# padaukprog.net
KiCad netlist of a schematic drawn in EAGLE
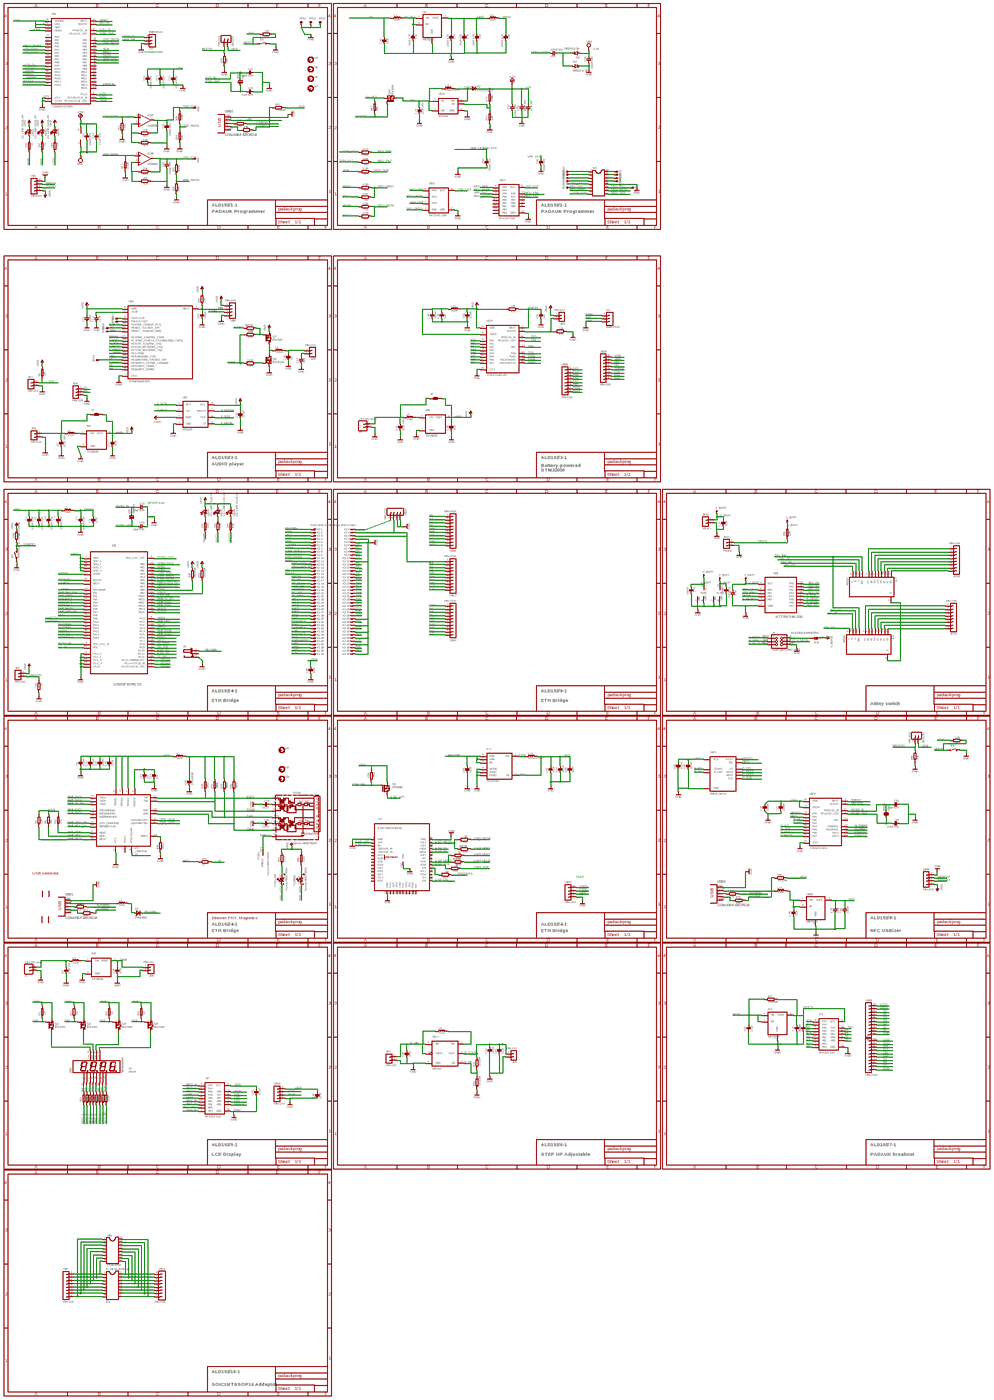
[diagram p0: schematic, sheet 1, overview]
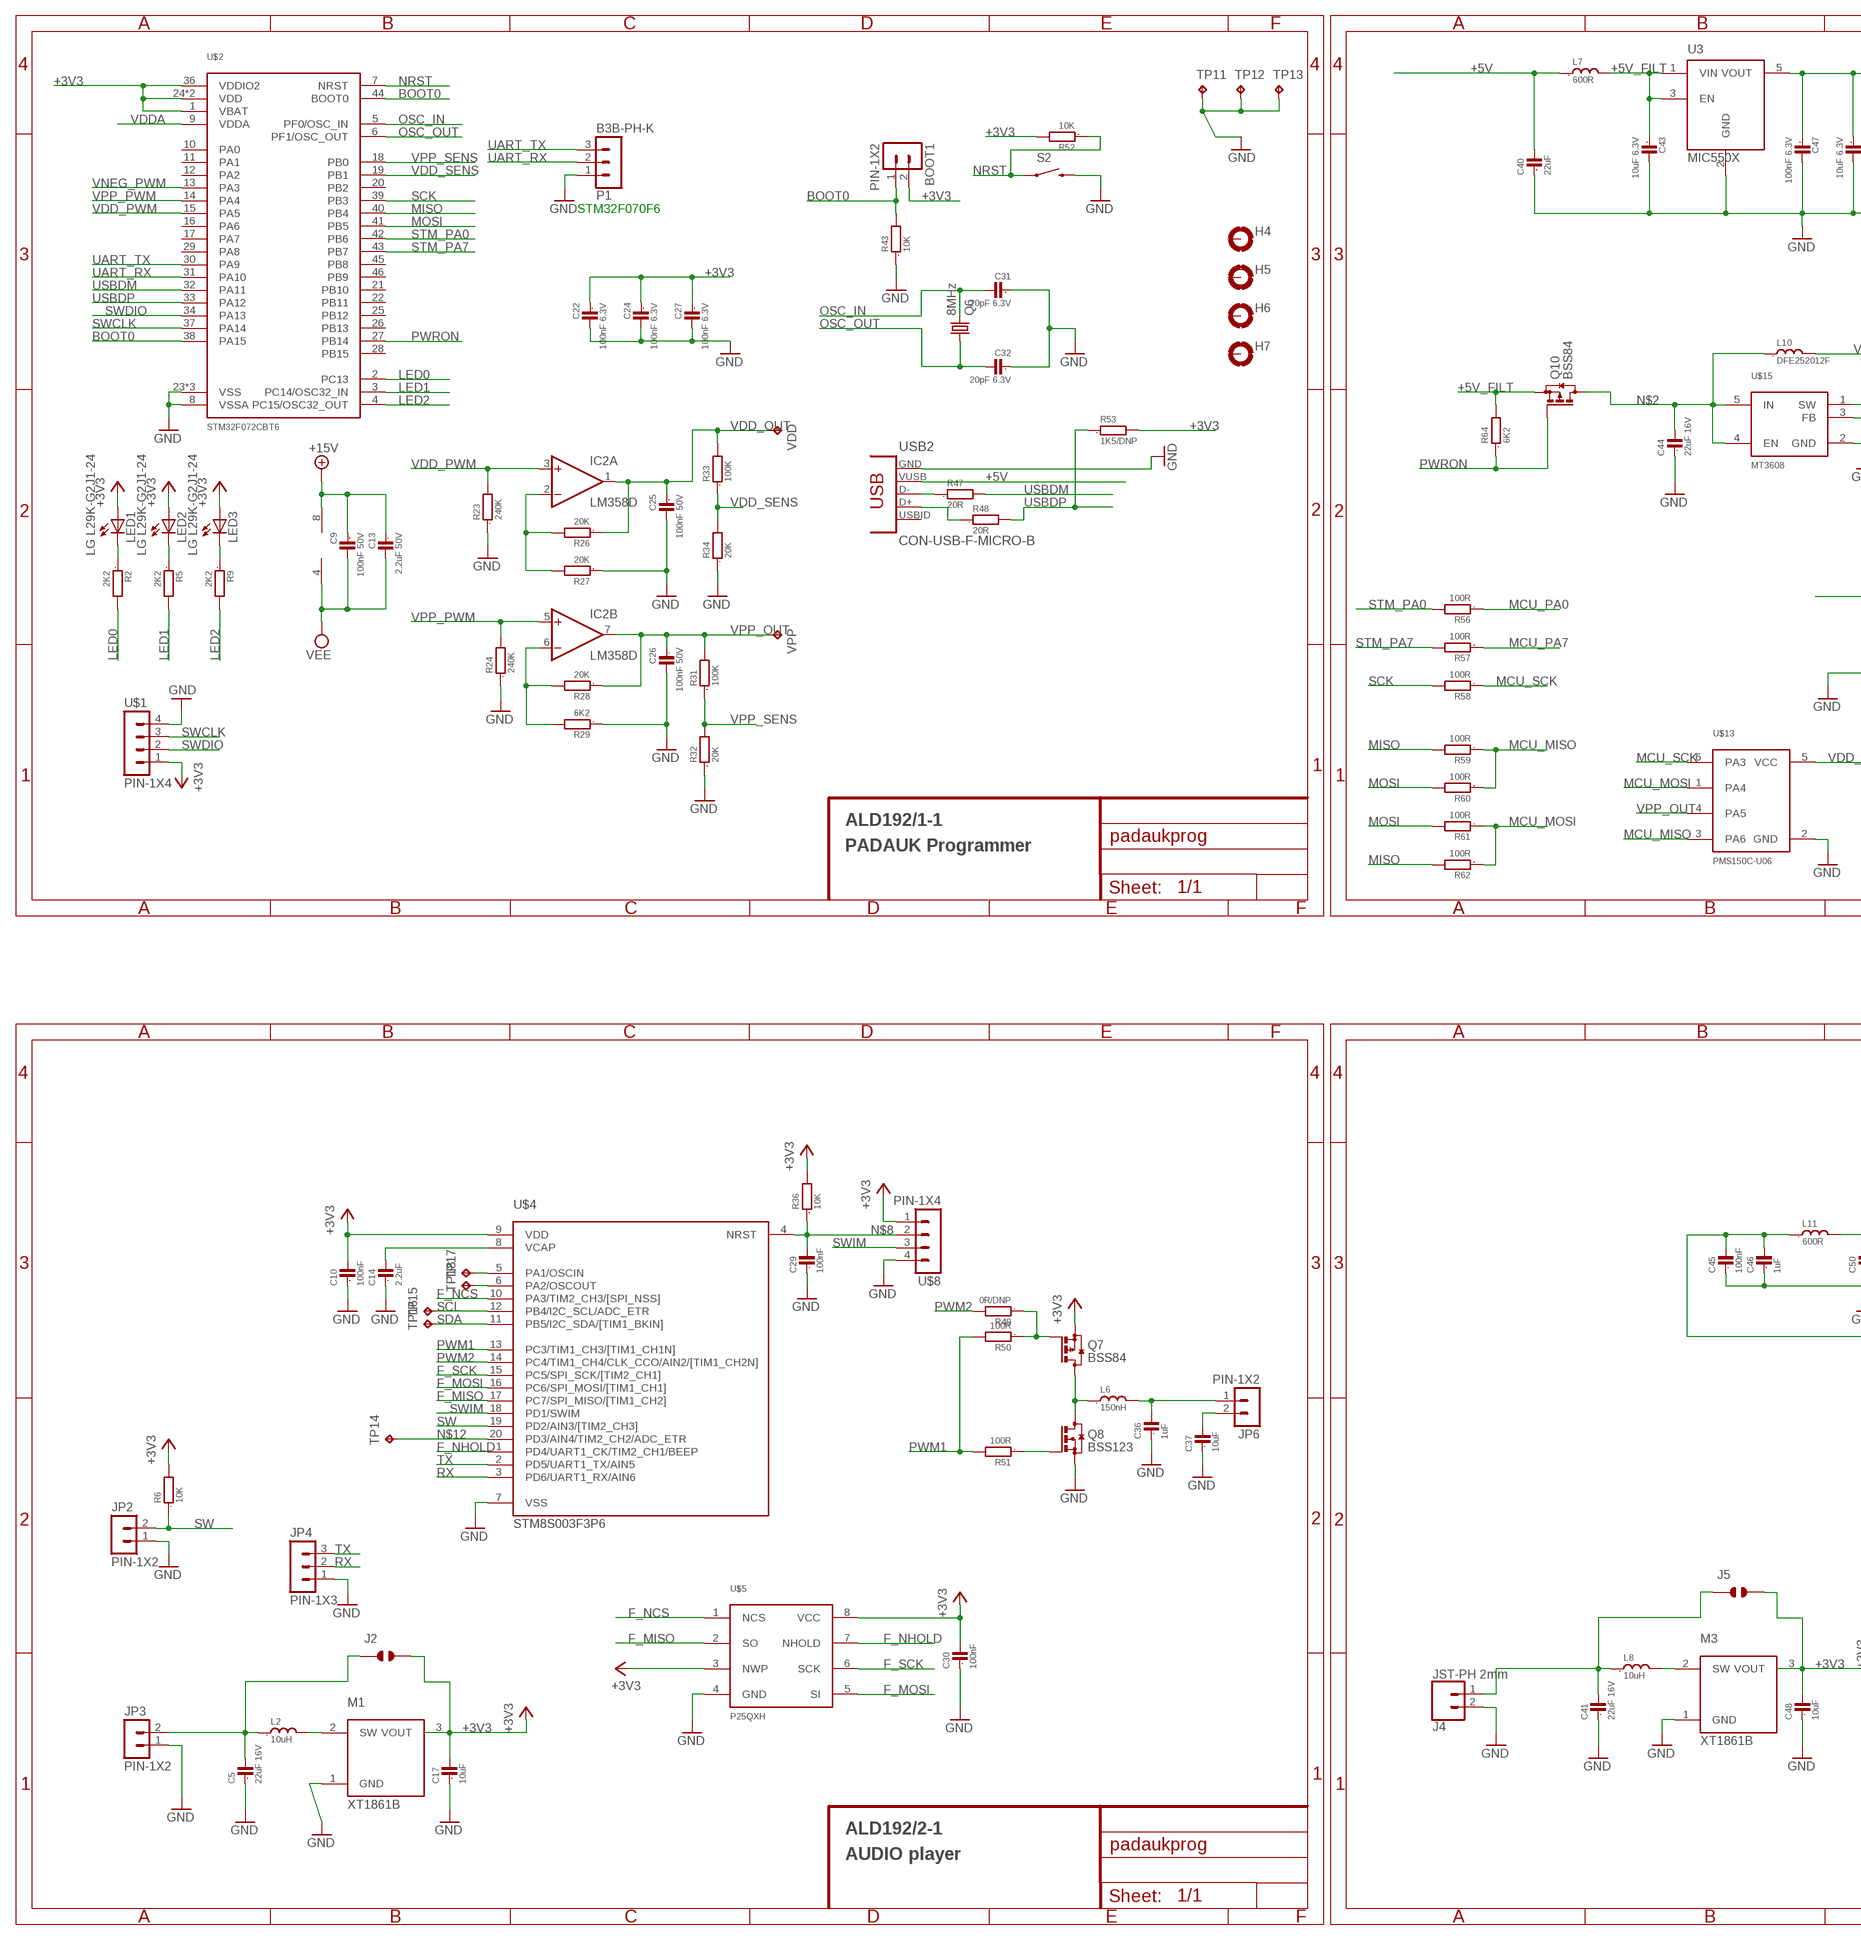
[diagram p1: schematic, sheet 1, part 1 of 7]
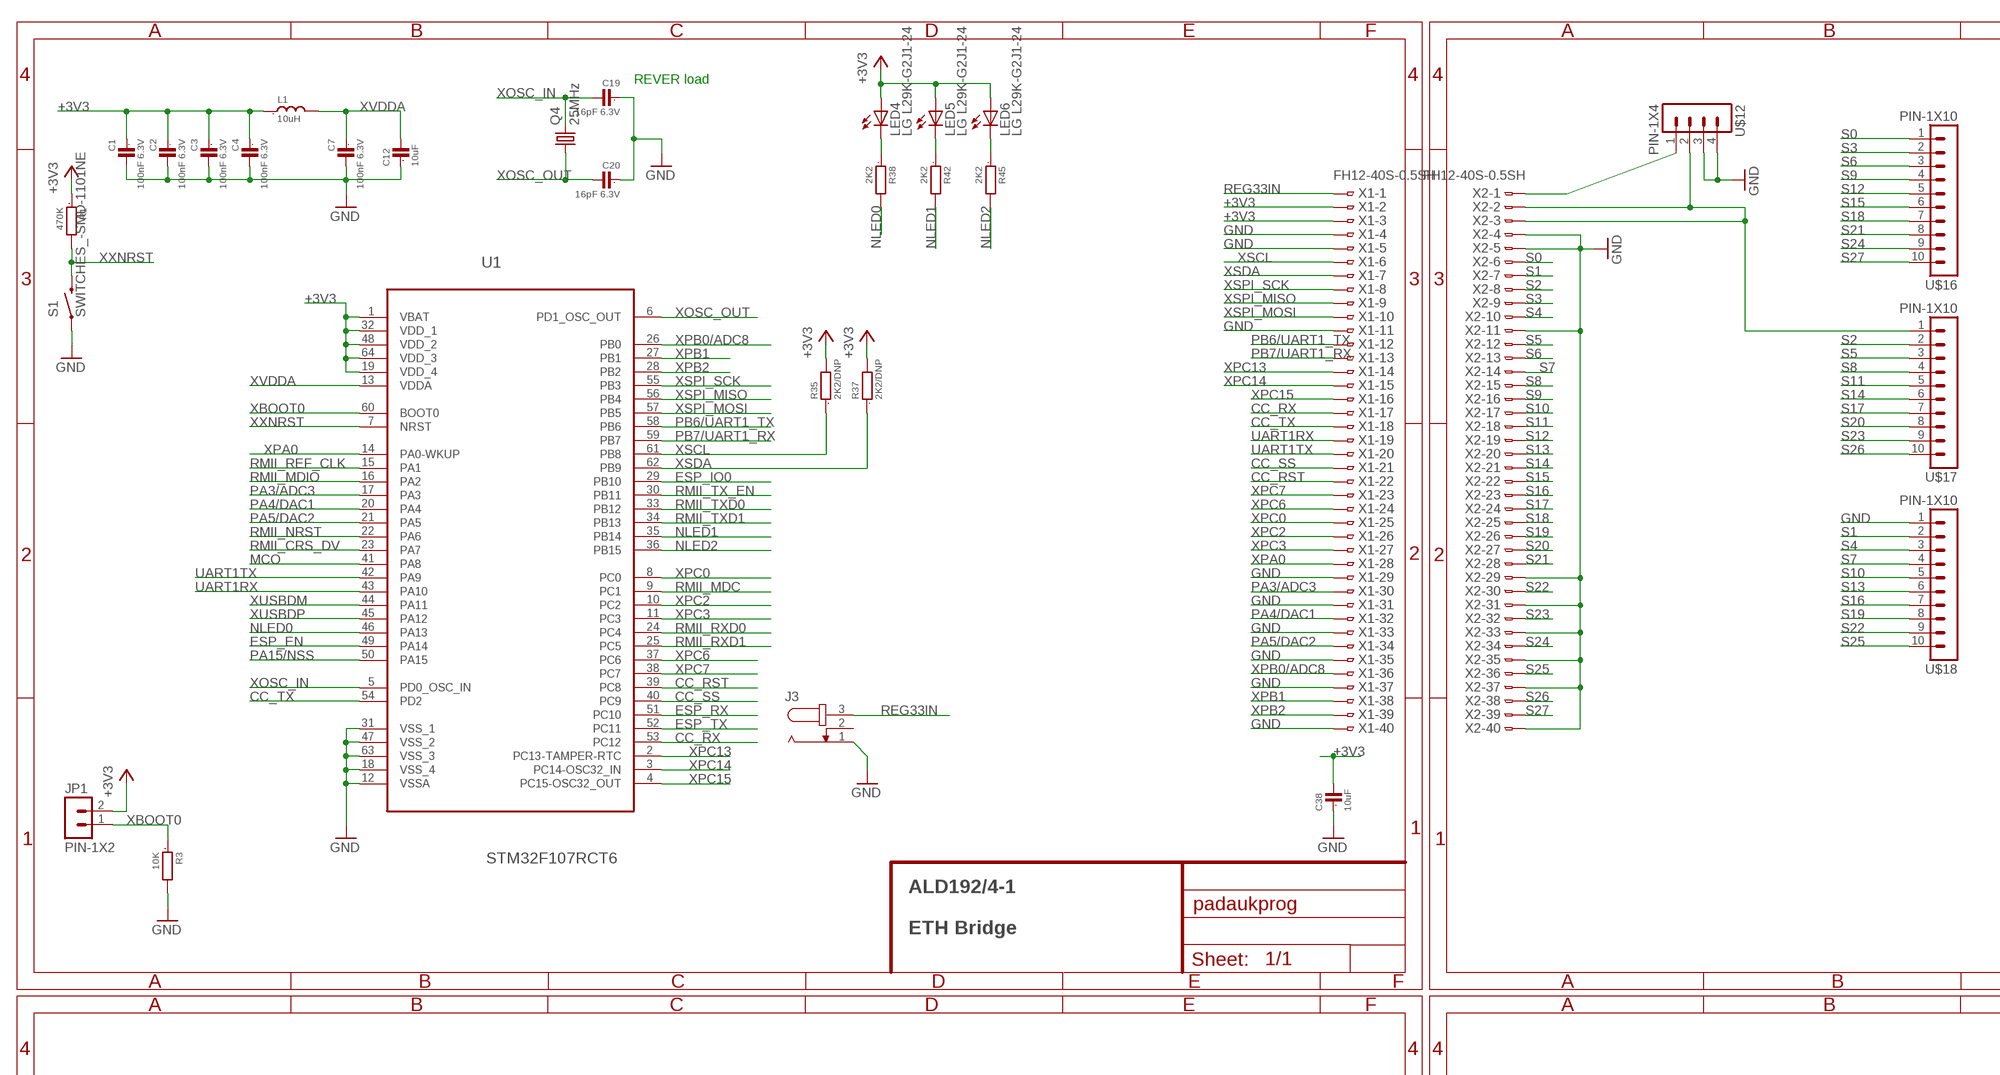
[diagram p2: schematic, sheet 1, part 2 of 7]
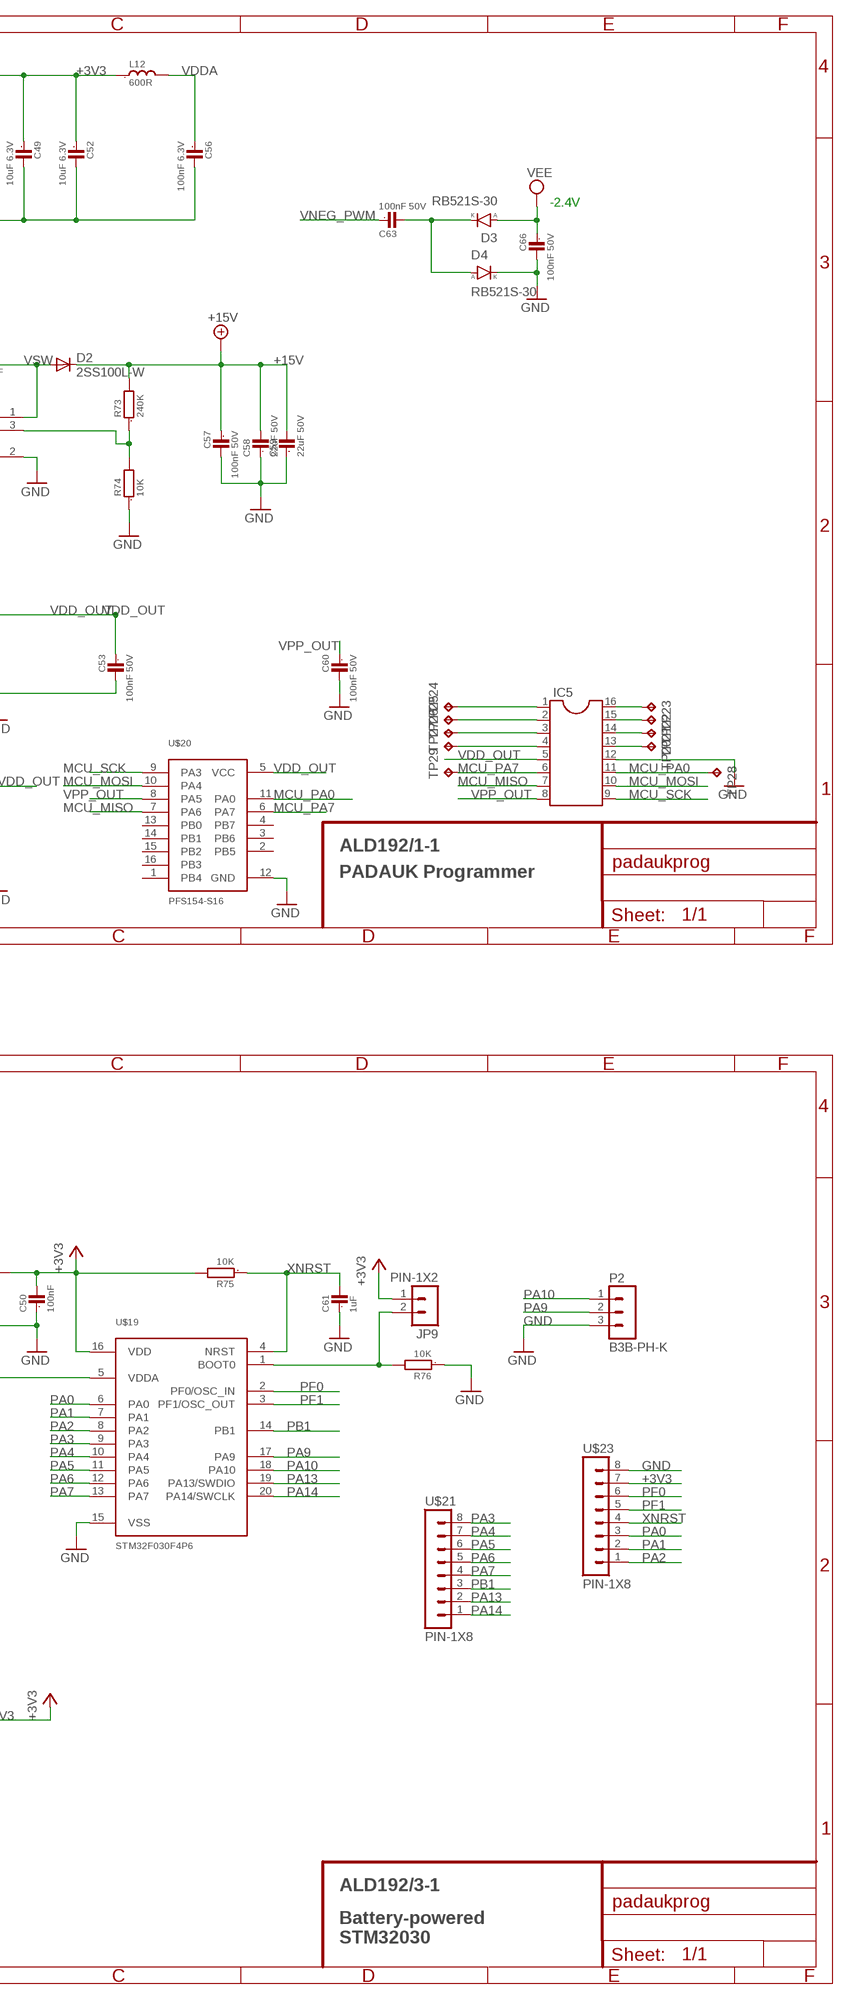
[diagram p3: schematic, sheet 1, part 3 of 7]
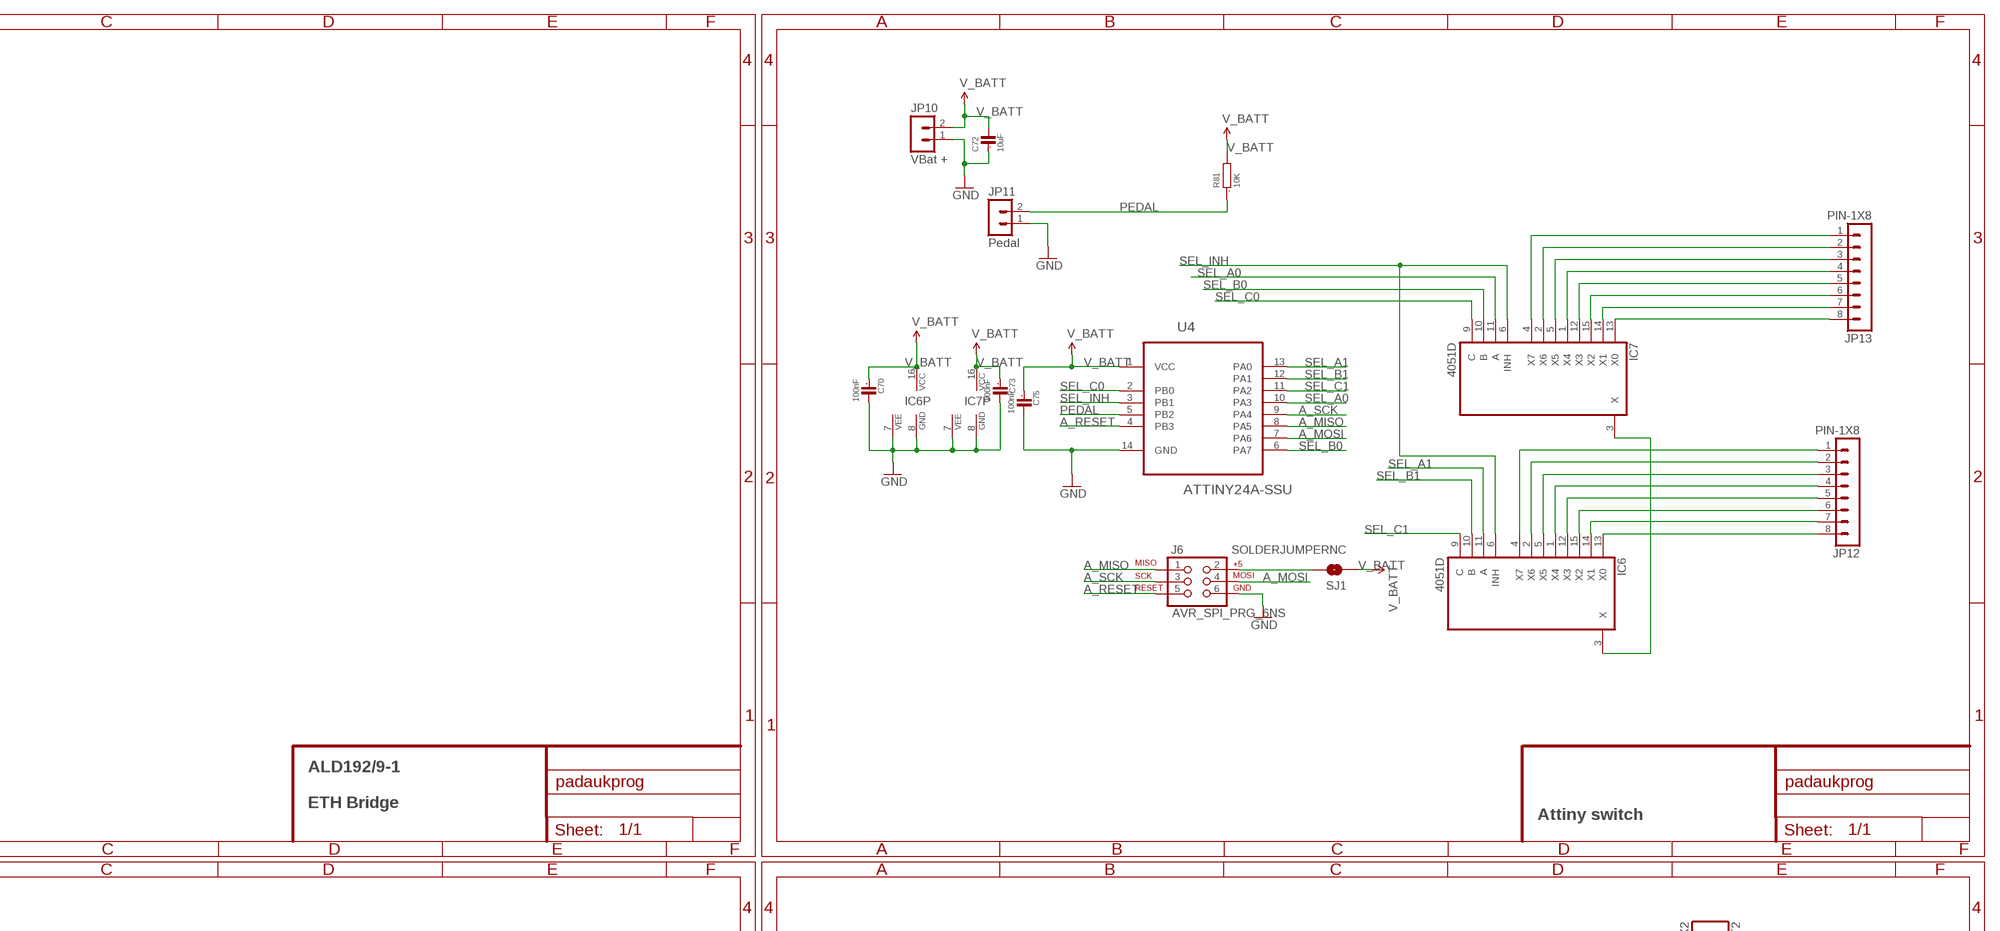
[diagram p4: schematic, sheet 1, part 4 of 7]
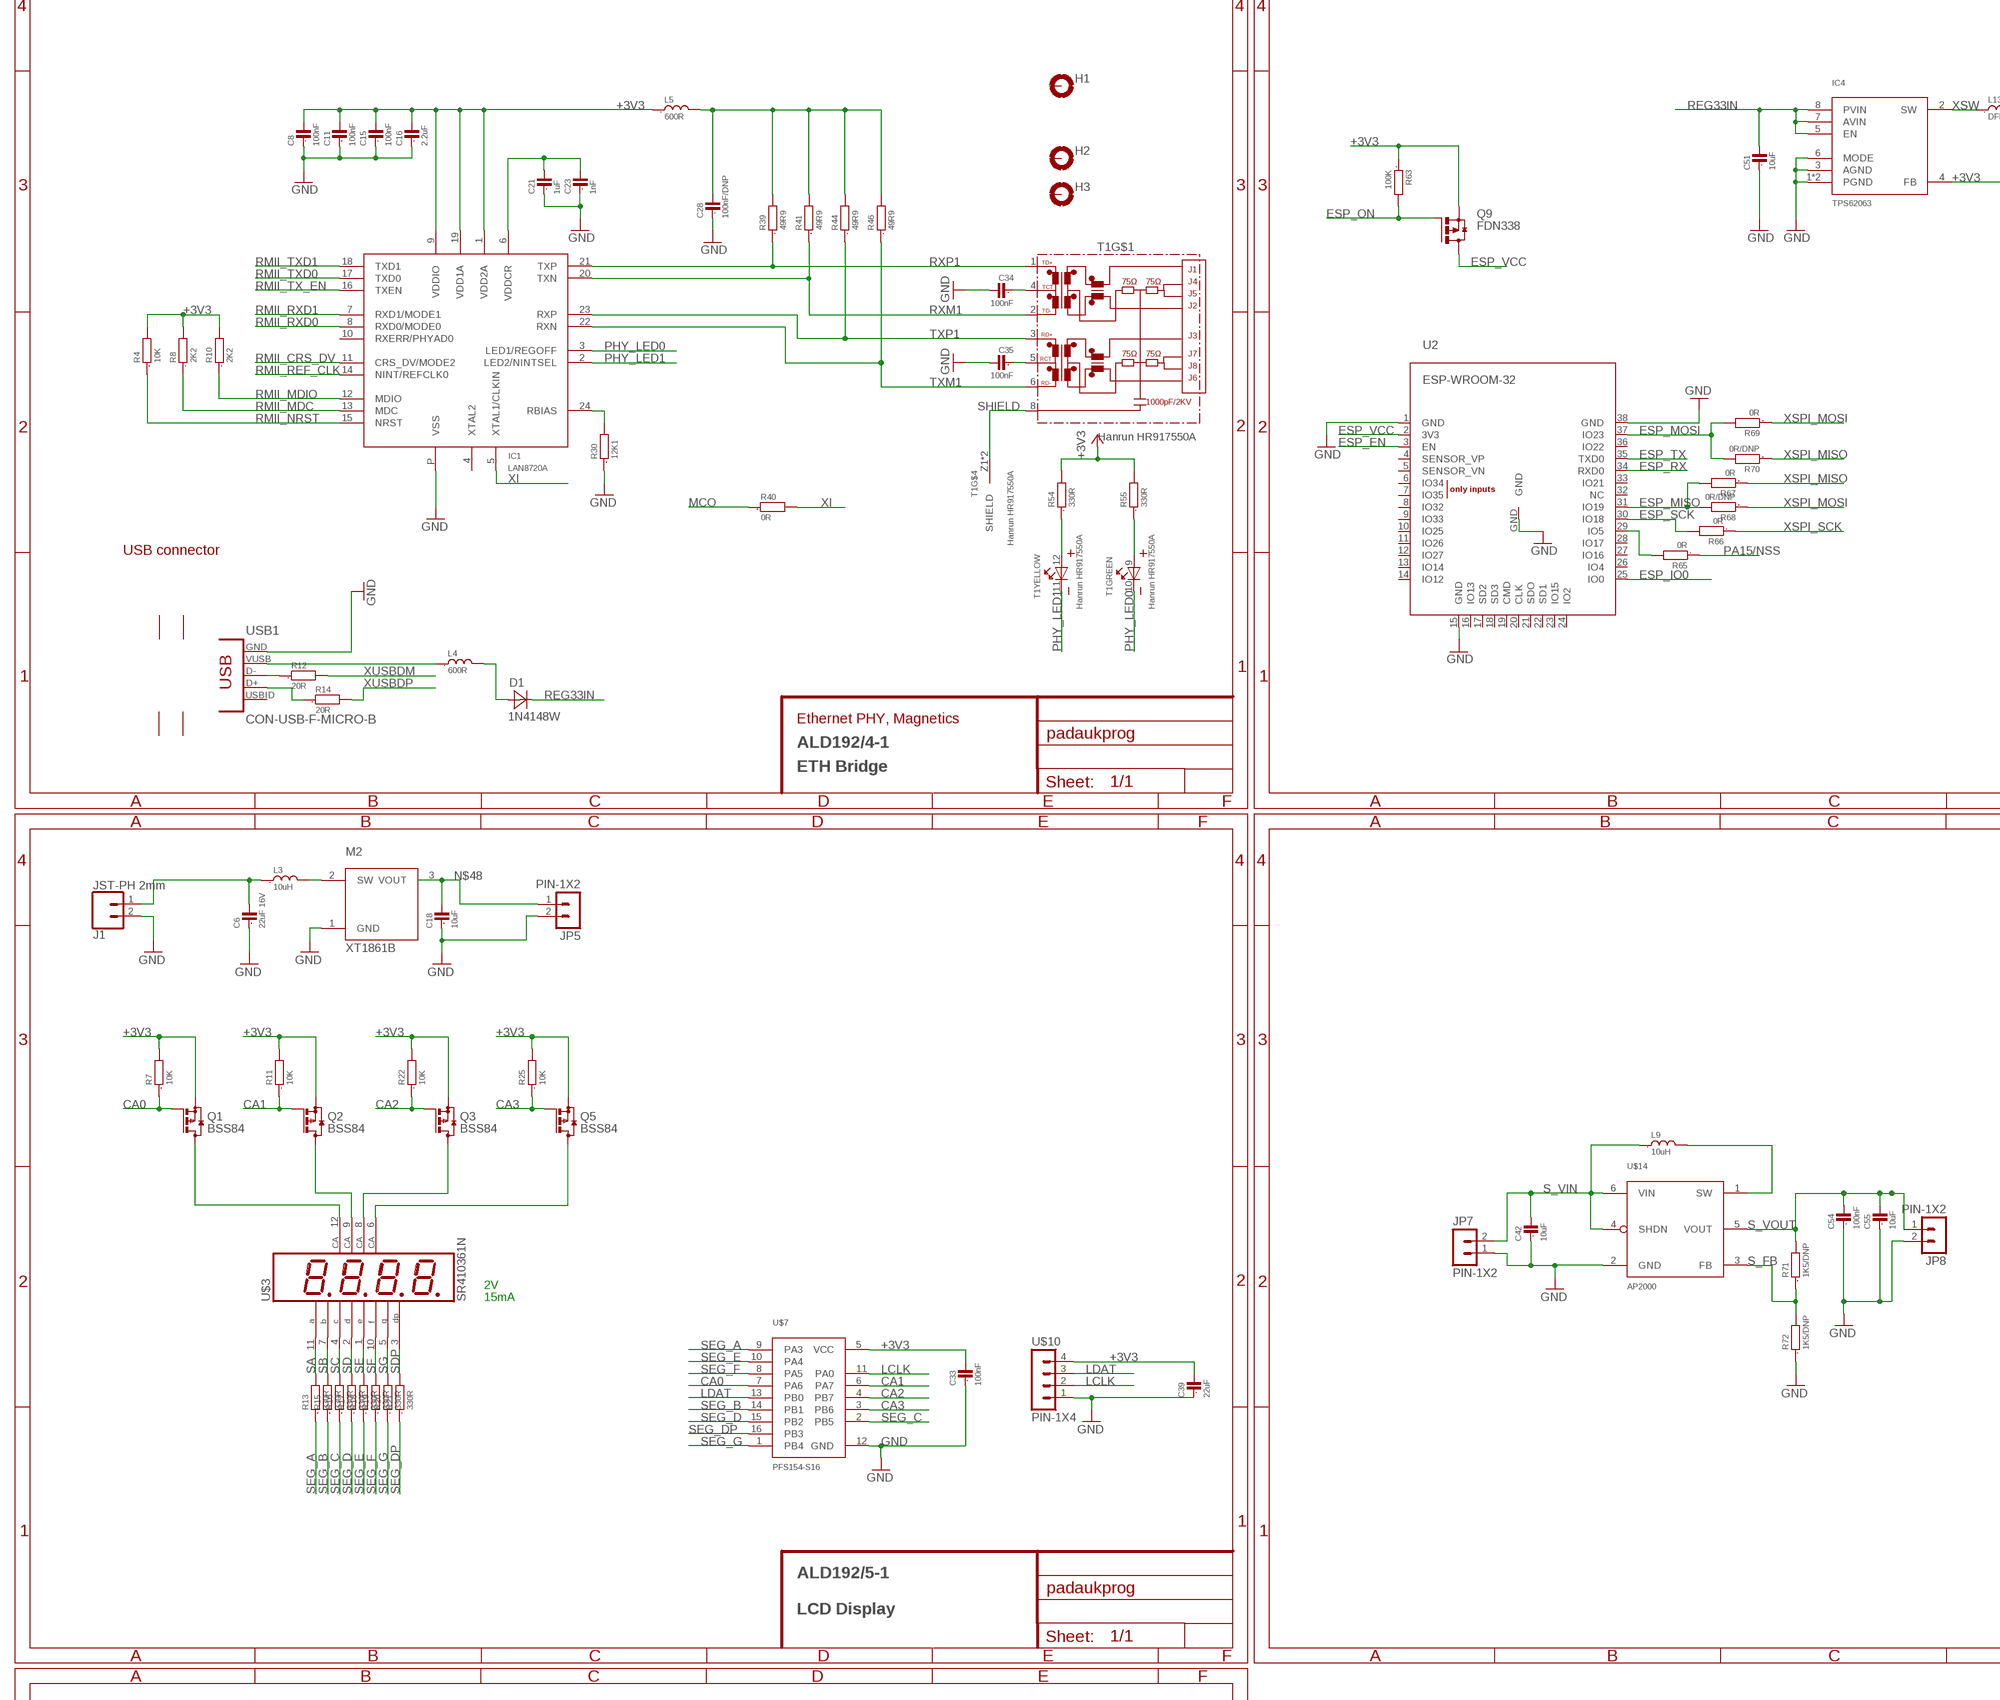
[diagram p5: schematic, sheet 1, part 5 of 7]
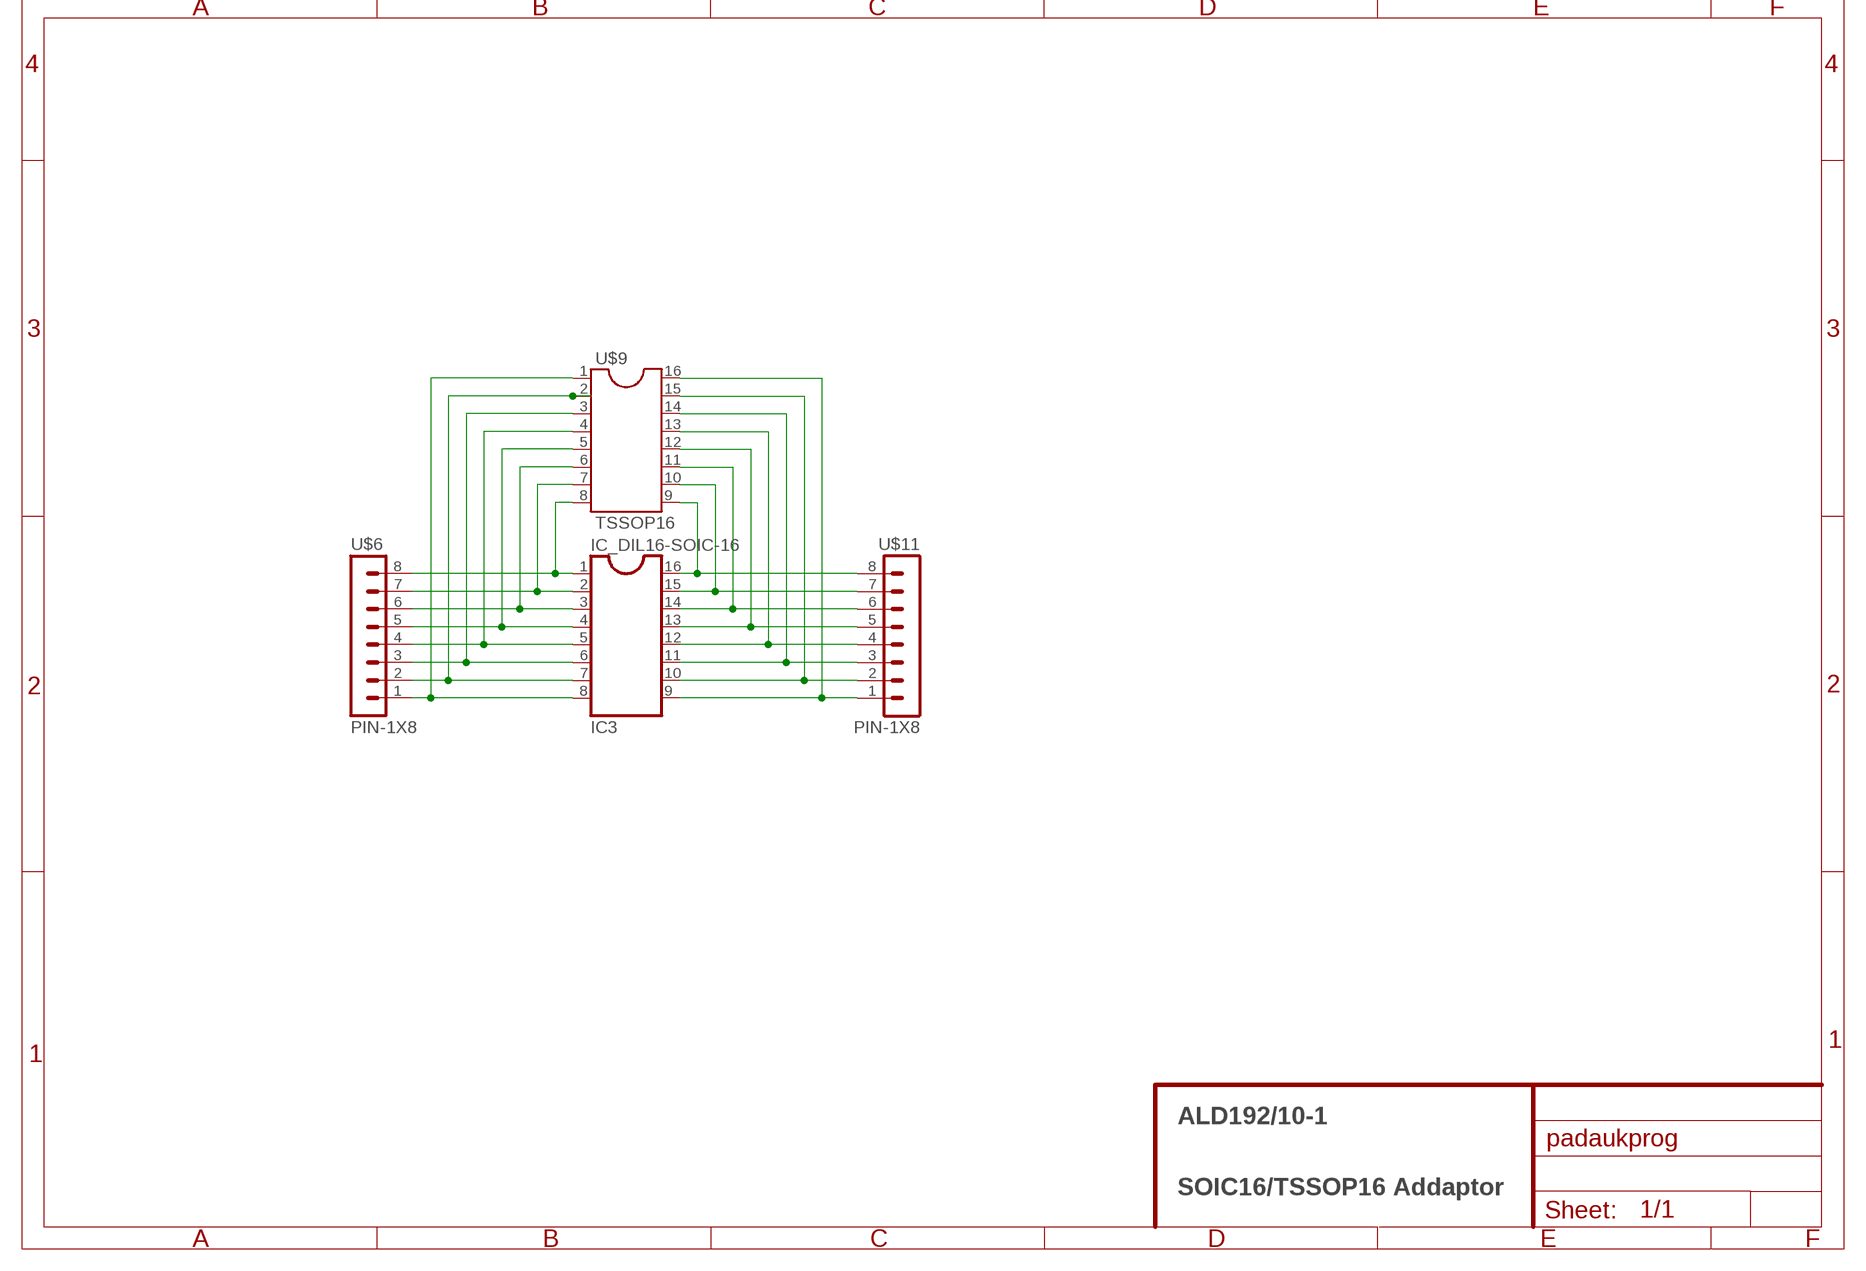
[diagram p6: schematic, sheet 1, part 6 of 7]
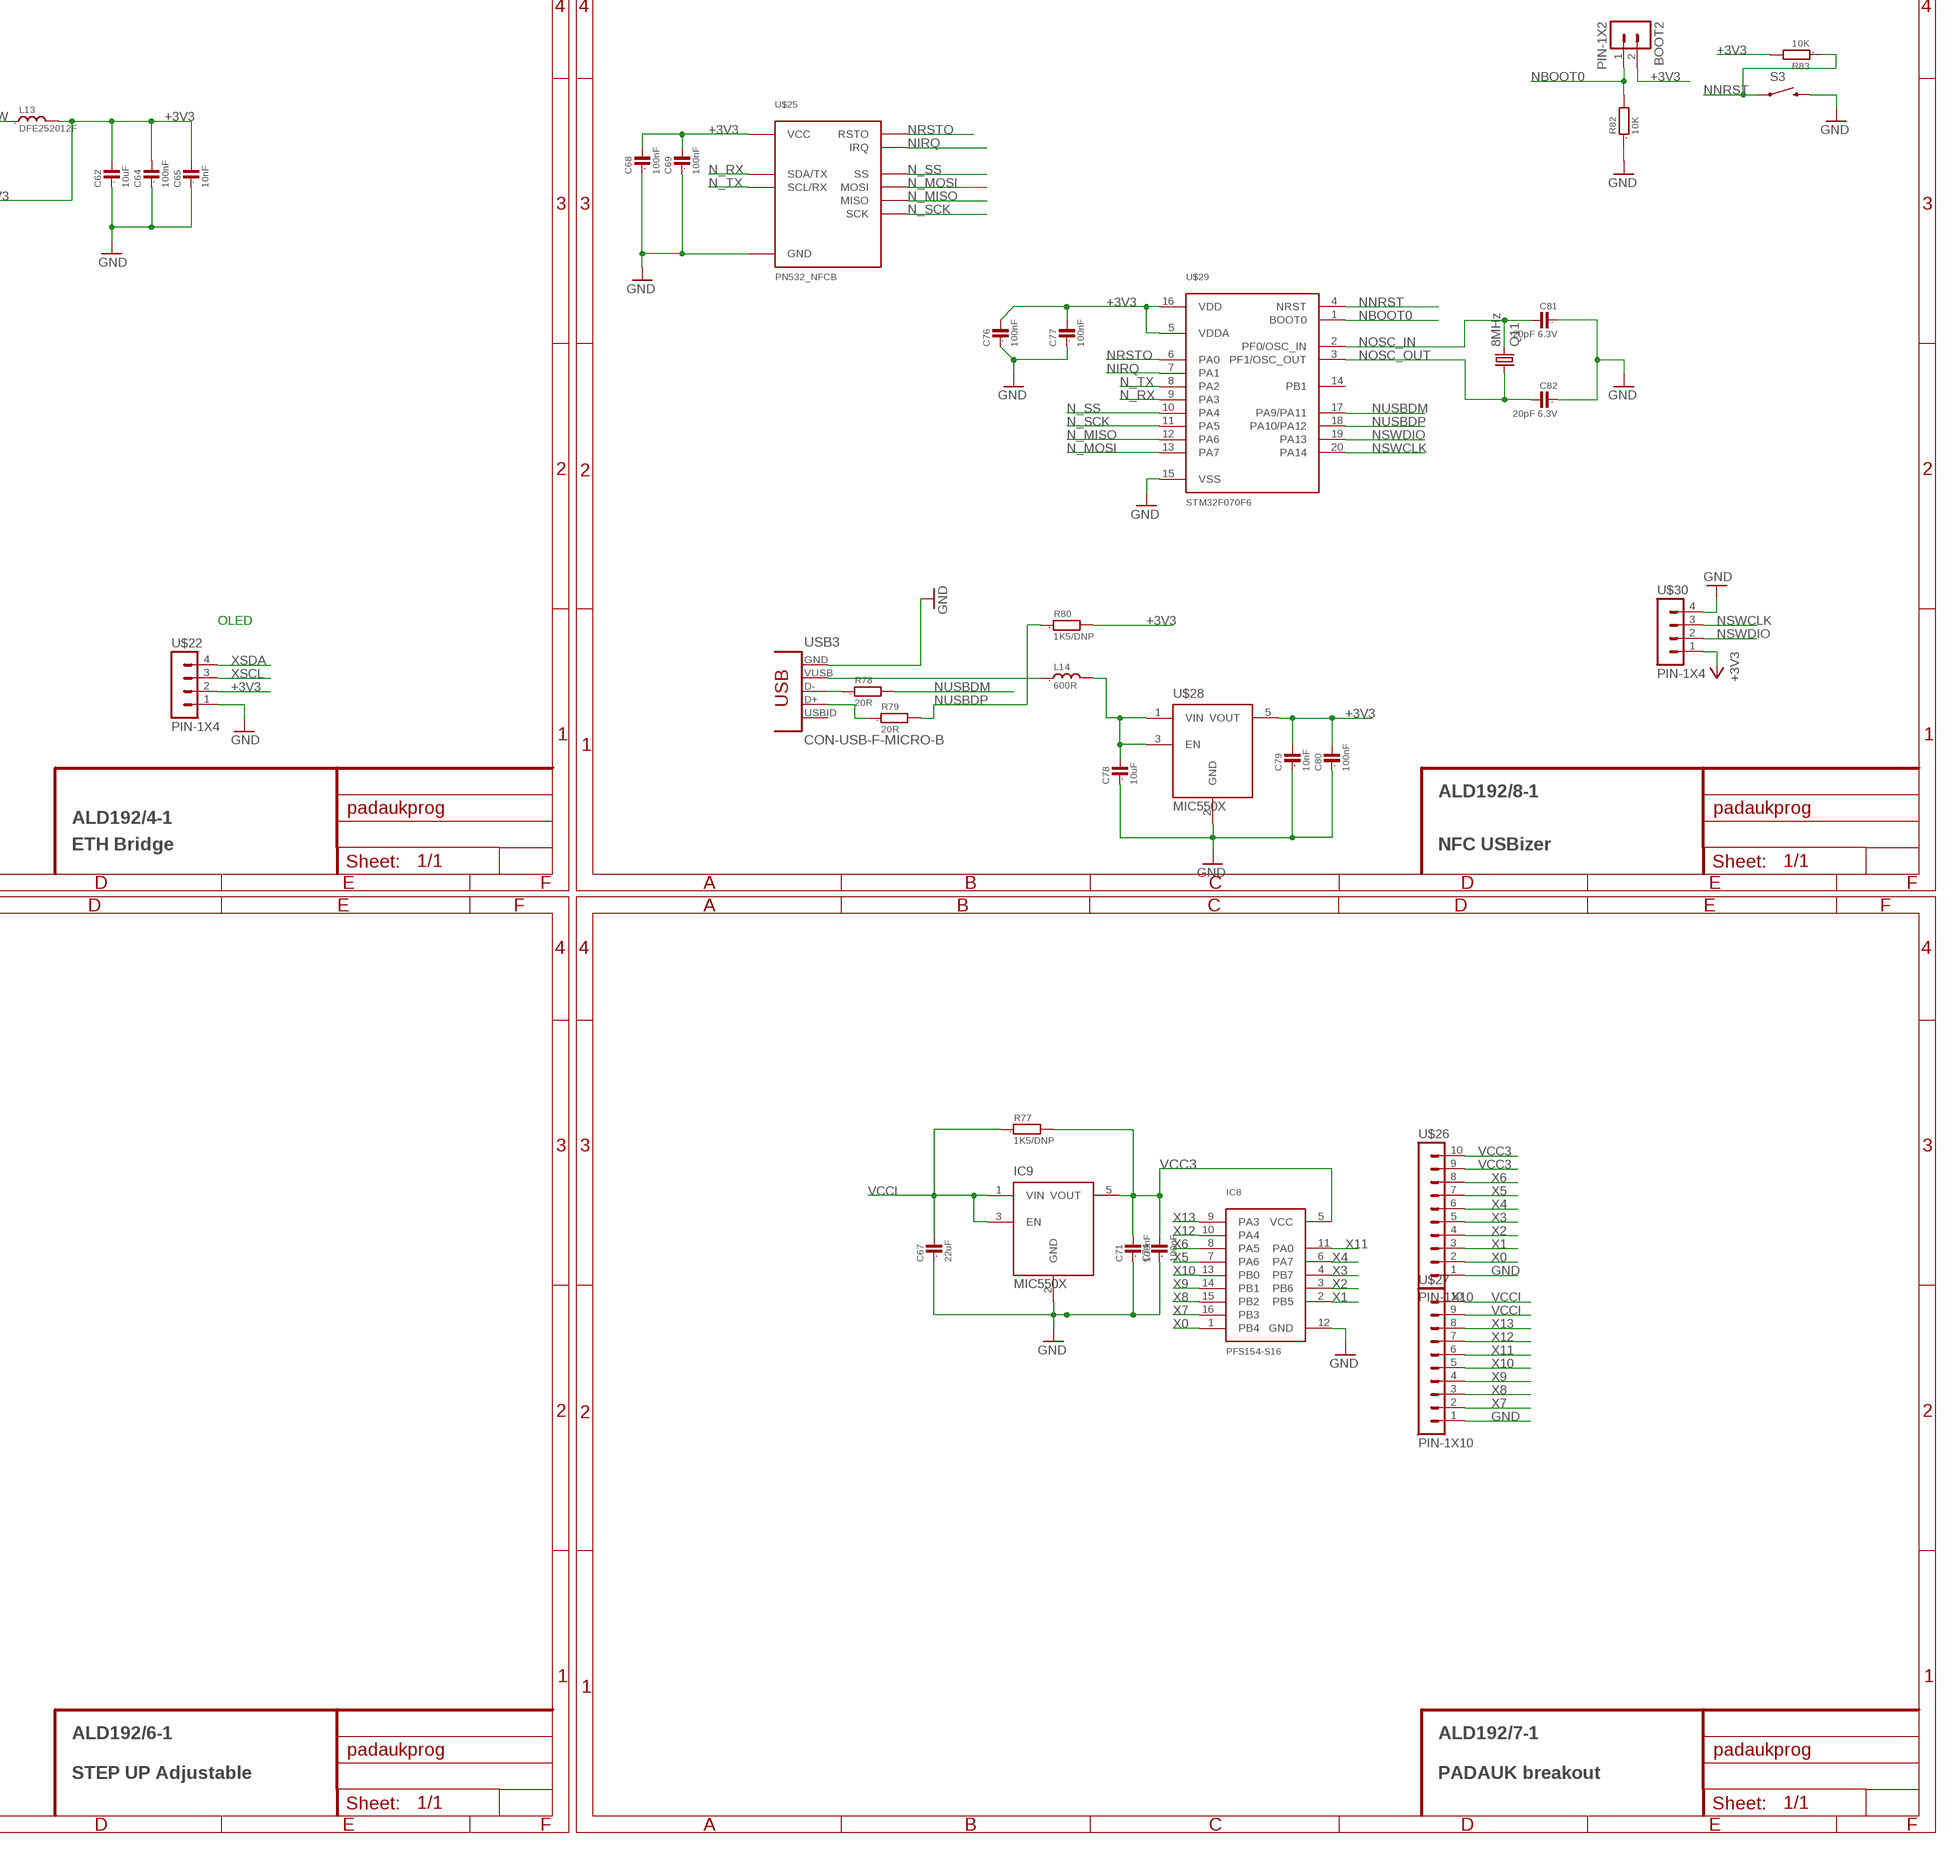
[diagram p7: schematic, sheet 1, part 7 of 7]

(export (version "E")
  (design (tool "Eeschema 10.0.6"))
  (components
    (comp (ref "BOOT1")
      (value "PIN-1X2")
      (footprint "eagle-import:PIN-1X2")
      (libsource (lib "eagle-import") (part "PIN-1X2"))
    )
    (comp (ref "BOOT2")
      (value "PIN-1X2")
      (footprint "eagle-import:PIN-1X2")
      (libsource (lib "eagle-import") (part "PIN-1X2"))
    )
    (comp (ref "C1")
      (value "100nF 6.3V")
      (footprint "eagle-import:0603")
      (libsource (lib "eagle-import") (part "C0603"))
    )
    (comp (ref "C2")
      (value "100nF 6.3V")
      (footprint "eagle-import:0603")
      (libsource (lib "eagle-import") (part "C0603"))
    )
    (comp (ref "C3")
      (value "100nF 6.3V")
      (footprint "eagle-import:0603")
      (libsource (lib "eagle-import") (part "C0603"))
    )
    (comp (ref "C4")
      (value "100nF 6.3V")
      (footprint "eagle-import:0603")
      (libsource (lib "eagle-import") (part "C0603"))
    )
    (comp (ref "C5")
      (value "22uF 16V")
      (footprint "eagle-import:0805")
      (libsource (lib "eagle-import") (part "C0805"))
    )
    (comp (ref "C6")
      (value "22uF 16V")
      (footprint "eagle-import:0805")
      (libsource (lib "eagle-import") (part "C0805"))
    )
    (comp (ref "C7")
      (value "100nF 6.3V")
      (footprint "eagle-import:0603")
      (libsource (lib "eagle-import") (part "C0603"))
    )
    (comp (ref "C8")
      (value "100nF")
      (footprint "eagle-import:0603")
      (libsource (lib "eagle-import") (part "C0603"))
    )
    (comp (ref "C9")
      (value "100nF 50V")
      (footprint "eagle-import:0603")
      (libsource (lib "eagle-import") (part "C0603"))
    )
    (comp (ref "C10")
      (value "100nF")
      (footprint "eagle-import:0603")
      (libsource (lib "eagle-import") (part "C0603"))
    )
    (comp (ref "C11")
      (value "100nF")
      (footprint "eagle-import:0603")
      (libsource (lib "eagle-import") (part "C0603"))
    )
    (comp (ref "C12")
      (value "10uF")
      (footprint "eagle-import:0603")
      (libsource (lib "eagle-import") (part "C0603"))
    )
    (comp (ref "C13")
      (value "2.2uF 50V")
      (footprint "eagle-import:0805")
      (libsource (lib "eagle-import") (part "C0805"))
    )
    (comp (ref "C14")
      (value "2.2uF")
      (footprint "eagle-import:0603")
      (libsource (lib "eagle-import") (part "C0603"))
    )
    (comp (ref "C15")
      (value "100nF")
      (footprint "eagle-import:0603")
      (libsource (lib "eagle-import") (part "C0603"))
    )
    (comp (ref "C16")
      (value "2.2uF")
      (footprint "eagle-import:0805")
      (libsource (lib "eagle-import") (part "C0805"))
    )
    (comp (ref "C17")
      (value "10uF")
      (footprint "eagle-import:0603")
      (libsource (lib "eagle-import") (part "C0603"))
    )
    (comp (ref "C18")
      (value "10uF")
      (footprint "eagle-import:0603")
      (libsource (lib "eagle-import") (part "C0603"))
    )
    (comp (ref "C19")
      (value "16pF 6.3V")
      (footprint "eagle-import:0603")
      (libsource (lib "eagle-import") (part "C0603"))
    )
    (comp (ref "C20")
      (value "16pF 6.3V")
      (footprint "eagle-import:0603")
      (libsource (lib "eagle-import") (part "C0603"))
    )
    (comp (ref "C21")
      (value "1uF")
      (footprint "eagle-import:0603")
      (libsource (lib "eagle-import") (part "C0603"))
    )
    (comp (ref "C22")
      (value "100nF 6.3V")
      (footprint "eagle-import:0603")
      (libsource (lib "eagle-import") (part "C0603"))
    )
    (comp (ref "C23")
      (value "1nF")
      (footprint "eagle-import:0603")
      (libsource (lib "eagle-import") (part "C0603"))
    )
    (comp (ref "C24")
      (value "100nF 6.3V")
      (footprint "eagle-import:0603")
      (libsource (lib "eagle-import") (part "C0603"))
    )
    (comp (ref "C25")
      (value "100nF 50V")
      (footprint "eagle-import:0603")
      (libsource (lib "eagle-import") (part "C0603"))
    )
    (comp (ref "C26")
      (value "100nF 50V")
      (footprint "eagle-import:0603")
      (libsource (lib "eagle-import") (part "C0603"))
    )
    (comp (ref "C27")
      (value "100nF 6.3V")
      (footprint "eagle-import:0603")
      (libsource (lib "eagle-import") (part "C0603"))
    )
    (comp (ref "C28")
      (value "100nF/DNP")
      (footprint "eagle-import:0603")
      (libsource (lib "eagle-import") (part "C0603"))
    )
    (comp (ref "C29")
      (value "100nF")
      (footprint "eagle-import:0603")
      (libsource (lib "eagle-import") (part "C0603"))
    )
    (comp (ref "C30")
      (value "100nF")
      (footprint "eagle-import:0603")
      (libsource (lib "eagle-import") (part "C0603"))
    )
    (comp (ref "C31")
      (value "20pF 6.3V")
      (footprint "eagle-import:0603")
      (libsource (lib "eagle-import") (part "C0603"))
    )
    (comp (ref "C32")
      (value "20pF 6.3V")
      (footprint "eagle-import:0603")
      (libsource (lib "eagle-import") (part "C0603"))
    )
    (comp (ref "C33")
      (value "100nF")
      (footprint "eagle-import:0603")
      (libsource (lib "eagle-import") (part "C0603"))
    )
    (comp (ref "C34")
      (value "100nF")
      (footprint "eagle-import:0603")
      (libsource (lib "eagle-import") (part "C0603"))
    )
    (comp (ref "C35")
      (value "100nF")
      (footprint "eagle-import:0603")
      (libsource (lib "eagle-import") (part "C0603"))
    )
    (comp (ref "C36")
      (value "1uF")
      (footprint "eagle-import:0603")
      (libsource (lib "eagle-import") (part "C0603"))
    )
    (comp (ref "C37")
      (value "10uF")
      (footprint "eagle-import:0805")
      (libsource (lib "eagle-import") (part "C0805"))
    )
    (comp (ref "C38")
      (value "10uF")
      (footprint "eagle-import:0603")
      (libsource (lib "eagle-import") (part "C0603"))
    )
    (comp (ref "C39")
      (value "22uF")
      (footprint "eagle-import:0805")
      (libsource (lib "eagle-import") (part "C0805"))
    )
    (comp (ref "C40")
      (value "22uF")
      (footprint "eagle-import:0805")
      (libsource (lib "eagle-import") (part "C0805"))
    )
    (comp (ref "C41")
      (value "22uF 16V")
      (footprint "eagle-import:0805")
      (libsource (lib "eagle-import") (part "C0805"))
    )
    (comp (ref "C42")
      (value "10uF")
      (footprint "eagle-import:0805")
      (libsource (lib "eagle-import") (part "C0805"))
    )
    (comp (ref "C43")
      (value "10uF 6.3V")
      (footprint "eagle-import:0603")
      (libsource (lib "eagle-import") (part "C0603"))
    )
    (comp (ref "C44")
      (value "22uF 16V")
      (footprint "eagle-import:0805")
      (libsource (lib "eagle-import") (part "C0805"))
    )
    (comp (ref "C45")
      (value "100nF")
      (footprint "eagle-import:0603")
      (libsource (lib "eagle-import") (part "C0603"))
    )
    (comp (ref "C46")
      (value "1uF")
      (footprint "eagle-import:0603")
      (libsource (lib "eagle-import") (part "C0603"))
    )
    (comp (ref "C47")
      (value "100nF 6.3V")
      (footprint "eagle-import:0603")
      (libsource (lib "eagle-import") (part "C0603"))
    )
    (comp (ref "C48")
      (value "10uF")
      (footprint "eagle-import:0603")
      (libsource (lib "eagle-import") (part "C0603"))
    )
    (comp (ref "C49")
      (value "10uF 6.3V")
      (footprint "eagle-import:0603")
      (libsource (lib "eagle-import") (part "C0603"))
    )
    (comp (ref "C50")
      (value "100nF")
      (footprint "eagle-import:0603")
      (libsource (lib "eagle-import") (part "C0603"))
    )
    (comp (ref "C51")
      (value "10uF")
      (footprint "eagle-import:0805")
      (libsource (lib "eagle-import") (part "C0805"))
    )
    (comp (ref "C52")
      (value "10uF 6.3V")
      (footprint "eagle-import:0603")
      (libsource (lib "eagle-import") (part "C0603"))
    )
    (comp (ref "C53")
      (value "100nF 50V")
      (footprint "eagle-import:0603")
      (libsource (lib "eagle-import") (part "C0603"))
    )
    (comp (ref "C54")
      (value "100nF")
      (footprint "eagle-import:0603")
      (libsource (lib "eagle-import") (part "C0603"))
    )
    (comp (ref "C55")
      (value "10uF")
      (footprint "eagle-import:0805")
      (libsource (lib "eagle-import") (part "C0805"))
    )
    (comp (ref "C56")
      (value "100nF 6.3V")
      (footprint "eagle-import:0603")
      (libsource (lib "eagle-import") (part "C0603"))
    )
    (comp (ref "C57")
      (value "100nF 50V")
      (footprint "eagle-import:0603")
      (libsource (lib "eagle-import") (part "C0603"))
    )
    (comp (ref "C58")
      (value "22uF 50V")
      (footprint "eagle-import:0805")
      (libsource (lib "eagle-import") (part "C0805"))
    )
    (comp (ref "C59")
      (value "22uF 50V")
      (footprint "eagle-import:0805")
      (libsource (lib "eagle-import") (part "C0805"))
    )
    (comp (ref "C60")
      (value "100nF 50V")
      (footprint "eagle-import:0603")
      (libsource (lib "eagle-import") (part "C0603"))
    )
    (comp (ref "C61")
      (value "1uF")
      (footprint "eagle-import:0603")
      (libsource (lib "eagle-import") (part "C0603"))
    )
    (comp (ref "C62")
      (value "10uF")
      (footprint "eagle-import:0805")
      (libsource (lib "eagle-import") (part "C0805"))
    )
    (comp (ref "C63")
      (value "100nF 50V")
      (footprint "eagle-import:0603")
      (libsource (lib "eagle-import") (part "C0603"))
    )
    (comp (ref "C64")
      (value "100nF")
      (footprint "eagle-import:0603")
      (libsource (lib "eagle-import") (part "C0603"))
    )
    (comp (ref "C65")
      (value "10nF")
      (footprint "eagle-import:0603")
      (libsource (lib "eagle-import") (part "C0603"))
    )
    (comp (ref "C66")
      (value "100nF 50V")
      (footprint "eagle-import:0603")
      (libsource (lib "eagle-import") (part "C0603"))
    )
    (comp (ref "C67")
      (value "22uF")
      (footprint "eagle-import:0805")
      (libsource (lib "eagle-import") (part "C0805"))
    )
    (comp (ref "C68")
      (value "100nF")
      (footprint "eagle-import:0603")
      (libsource (lib "eagle-import") (part "C0603"))
    )
    (comp (ref "C69")
      (value "100nF")
      (footprint "eagle-import:0603")
      (libsource (lib "eagle-import") (part "C0603"))
    )
    (comp (ref "C70")
      (value "100nF")
      (footprint "eagle-import:0603")
      (libsource (lib "eagle-import") (part "C0603"))
    )
    (comp (ref "C71")
      (value "100nF")
      (footprint "eagle-import:0603")
      (libsource (lib "eagle-import") (part "C0603"))
    )
    (comp (ref "C72")
      (value "10uF")
      (footprint "eagle-import:0805")
      (libsource (lib "eagle-import") (part "C0805"))
    )
    (comp (ref "C73")
      (value "100nF")
      (footprint "eagle-import:0603")
      (libsource (lib "eagle-import") (part "C0603"))
    )
    (comp (ref "C74")
      (value "100nF")
      (footprint "eagle-import:0603")
      (libsource (lib "eagle-import") (part "C0603"))
    )
    (comp (ref "C75")
      (value "100nF")
      (footprint "eagle-import:0603")
      (libsource (lib "eagle-import") (part "C0603"))
    )
    (comp (ref "C76")
      (value "100nF")
      (footprint "eagle-import:0603")
      (libsource (lib "eagle-import") (part "C0603"))
    )
    (comp (ref "C77")
      (value "100nF")
      (footprint "eagle-import:0603")
      (libsource (lib "eagle-import") (part "C0603"))
    )
    (comp (ref "C78")
      (value "10uF")
      (footprint "eagle-import:0805")
      (libsource (lib "eagle-import") (part "C0805"))
    )
    (comp (ref "C79")
      (value "10nF")
      (footprint "eagle-import:0603")
      (libsource (lib "eagle-import") (part "C0603"))
    )
    (comp (ref "C80")
      (value "100nF")
      (footprint "eagle-import:0603")
      (libsource (lib "eagle-import") (part "C0603"))
    )
    (comp (ref "C81")
      (value "20pF 6.3V")
      (footprint "eagle-import:0603")
      (libsource (lib "eagle-import") (part "C0603"))
    )
    (comp (ref "C82")
      (value "20pF 6.3V")
      (footprint "eagle-import:0603")
      (libsource (lib "eagle-import") (part "C0603"))
    )
    (comp (ref "D1")
      (value "1N4148W")
      (footprint "eagle-import:SOD-123")
      (libsource (lib "eagle-import") (part "1N4148W"))
    )
    (comp (ref "D2")
      (value "2SS100L-W")
      (footprint "eagle-import:SOD-123")
      (libsource (lib "eagle-import") (part "DIODE-SOD-123"))
    )
    (comp (ref "D3")
      (value "RB521S-30")
      (footprint "eagle-import:SOD523")
      (libsource (lib "eagle-import") (part "DIODE-SCHOTTKY_SOD523"))
    )
    (comp (ref "D4")
      (value "RB521S-30")
      (footprint "eagle-import:SOD523")
      (libsource (lib "eagle-import") (part "DIODE-SCHOTTKY_SOD523"))
    )
    (comp (ref "H1")
      (value "MOUNT-PAD-ROUND3.2")
      (footprint "eagle-import:3,2-PAD")
      (libsource (lib "eagle-import") (part "MOUNT-PAD-ROUND3.2"))
    )
    (comp (ref "H2")
      (value "MOUNT-PAD-ROUND3.2")
      (footprint "eagle-import:3,2-PAD")
      (libsource (lib "eagle-import") (part "MOUNT-PAD-ROUND3.2"))
    )
    (comp (ref "H3")
      (value "MOUNT-PAD-ROUND3.2")
      (footprint "eagle-import:3,2-PAD")
      (libsource (lib "eagle-import") (part "MOUNT-PAD-ROUND3.2"))
    )
    (comp (ref "H4")
      (value "MOUNT-PAD-ROUND3.2")
      (footprint "eagle-import:3,2-PAD")
      (libsource (lib "eagle-import") (part "MOUNT-PAD-ROUND3.2"))
    )
    (comp (ref "H5")
      (value "MOUNT-PAD-ROUND3.2")
      (footprint "eagle-import:3,2-PAD")
      (libsource (lib "eagle-import") (part "MOUNT-PAD-ROUND3.2"))
    )
    (comp (ref "H6")
      (value "MOUNT-PAD-ROUND3.2")
      (footprint "eagle-import:3,2-PAD")
      (libsource (lib "eagle-import") (part "MOUNT-PAD-ROUND3.2"))
    )
    (comp (ref "H7")
      (value "MOUNT-PAD-ROUND3.2")
      (footprint "eagle-import:3,2-PAD")
      (libsource (lib "eagle-import") (part "MOUNT-PAD-ROUND3.2"))
    )
    (comp (ref "IC1")
      (value "LAN8720A")
      (footprint "eagle-import:QFN24_4MM_X_4MM")
      (libsource (lib "eagle-import") (part "LAN8720A"))
    )
    (comp (ref "IC2")
      (value "LM358D")
      (footprint "eagle-import:SO08")
      (libsource (lib "eagle-import") (part "LM358D"))
    )
    (comp (ref "IC3")
      (value "IC_DIL16-SOIC-16")
      (footprint "eagle-import:SOIC-16")
      (libsource (lib "eagle-import") (part "IC_DIL16-SOIC-16"))
    )
    (comp (ref "IC4")
      (value "TPS62063")
      (footprint "eagle-import:WSON8-2.1X2.1")
      (libsource (lib "eagle-import") (part "TPS62063"))
    )
    (comp (ref "IC5")
      (value "DIL16")
      (footprint "eagle-import:DIL16@1")
      (libsource (lib "eagle-import") (part "DIL16"))
    )
    (comp (ref "IC6")
      (value "4051D")
      (footprint "eagle-import:SO16")
      (libsource (lib "eagle-import") (part "4051D"))
    )
    (comp (ref "IC7")
      (value "4051D")
      (footprint "eagle-import:SO16")
      (libsource (lib "eagle-import") (part "4051D"))
    )
    (comp (ref "IC8")
      (value "PFS154-S16")
      (footprint "eagle-import:SOIC16-N")
      (libsource (lib "eagle-import") (part "PFS154-S16"))
    )
    (comp (ref "IC9")
      (value "MIC550X")
      (footprint "eagle-import:SOT23-5L")
      (libsource (lib "eagle-import") (part "MIC550X"))
    )
    (comp (ref "J1")
      (value "JST-PH 2mm")
      (footprint "eagle-import:JST-2-PTH@1")
      (libsource (lib "eagle-import") (part "CONN_02JST-PTH-2"))
    )
    (comp (ref "J2")
      (value "JUMPER_SOLDER_1X2")
      (footprint "eagle-import:JUMPER_SOLDER_1X2")
      (libsource (lib "eagle-import") (part "JUMPER_SOLDER_1X2"))
    )
    (comp (ref "J3")
      (value "JACK-PLUG")
      (footprint "eagle-import:SPC4078-NOSLOT")
      (libsource (lib "eagle-import") (part "JACK-PLUG"))
    )
    (comp (ref "J4")
      (value "JST-PH 2mm")
      (footprint "eagle-import:JST-2-PTH@1")
      (libsource (lib "eagle-import") (part "CONN_02JST-PTH-2"))
    )
    (comp (ref "J5")
      (value "JUMPER_SOLDER_1X2")
      (footprint "eagle-import:JUMPER_SOLDER_1X2")
      (libsource (lib "eagle-import") (part "JUMPER_SOLDER_1X2"))
    )
    (comp (ref "J6")
      (value "AVR_SPI_PRG_6NS")
      (footprint "eagle-import:2X3-NS")
      (libsource (lib "eagle-import") (part "AVR_SPI_PRG_6NS"))
    )
    (comp (ref "JP1")
      (value "PIN-1X2")
      (footprint "eagle-import:PIN-1X2")
      (libsource (lib "eagle-import") (part "PIN-1X2"))
    )
    (comp (ref "JP2")
      (value "PIN-1X2")
      (footprint "eagle-import:PIN-1X2")
      (libsource (lib "eagle-import") (part "PIN-1X2"))
    )
    (comp (ref "JP3")
      (value "PIN-1X2")
      (footprint "eagle-import:PIN-1X2")
      (libsource (lib "eagle-import") (part "PIN-1X2"))
    )
    (comp (ref "JP4")
      (value "PIN-1X3")
      (footprint "eagle-import:PIN-1X3")
      (libsource (lib "eagle-import") (part "PIN-1X3"))
    )
    (comp (ref "JP5")
      (value "PIN-1X2")
      (footprint "eagle-import:PIN-1X2")
      (libsource (lib "eagle-import") (part "PIN-1X2"))
    )
    (comp (ref "JP6")
      (value "PIN-1X2")
      (footprint "eagle-import:PIN-1X2")
      (libsource (lib "eagle-import") (part "PIN-1X2"))
    )
    (comp (ref "JP7")
      (value "PIN-1X2")
      (footprint "eagle-import:PIN-1X2")
      (libsource (lib "eagle-import") (part "PIN-1X2"))
    )
    (comp (ref "JP8")
      (value "PIN-1X2")
      (footprint "eagle-import:PIN-1X2")
      (libsource (lib "eagle-import") (part "PIN-1X2"))
    )
    (comp (ref "JP9")
      (value "PIN-1X2")
      (footprint "eagle-import:PIN-1X2")
      (libsource (lib "eagle-import") (part "PIN-1X2"))
    )
    (comp (ref "JP10")
      (value "VBat +")
      (footprint "eagle-import:PIN-1X2")
      (libsource (lib "eagle-import") (part "PIN-1X2"))
    )
    (comp (ref "JP11")
      (value "Pedal")
      (footprint "eagle-import:PIN-1X2")
      (libsource (lib "eagle-import") (part "PIN-1X2"))
    )
    (comp (ref "JP12")
      (value "PIN-1X8")
      (footprint "eagle-import:PIN-1X8")
      (libsource (lib "eagle-import") (part "PIN-1X8"))
    )
    (comp (ref "JP13")
      (value "PIN-1X8")
      (footprint "eagle-import:PIN-1X8")
      (libsource (lib "eagle-import") (part "PIN-1X8"))
    )
    (comp (ref "L1")
      (value "10uH")
      (footprint "eagle-import:0805")
      (libsource (lib "eagle-import") (part "L0805"))
    )
    (comp (ref "L2")
      (value "10uH")
      (footprint "eagle-import:0805")
      (libsource (lib "eagle-import") (part "L0805"))
    )
    (comp (ref "L3")
      (value "10uH")
      (footprint "eagle-import:0805")
      (libsource (lib "eagle-import") (part "L0805"))
    )
    (comp (ref "L4")
      (value "600R")
      (footprint "eagle-import:0805")
      (libsource (lib "eagle-import") (part "L0805"))
    )
    (comp (ref "L5")
      (value "600R")
      (footprint "eagle-import:0805")
      (libsource (lib "eagle-import") (part "L0805"))
    )
    (comp (ref "L6")
      (value "150nH")
      (footprint "eagle-import:0805")
      (libsource (lib "eagle-import") (part "L0805"))
    )
    (comp (ref "L7")
      (value "600R")
      (footprint "eagle-import:0805")
      (libsource (lib "eagle-import") (part "L0805"))
    )
    (comp (ref "L8")
      (value "10uH")
      (footprint "eagle-import:0805")
      (libsource (lib "eagle-import") (part "L0805"))
    )
    (comp (ref "L9")
      (value "10uH")
      (footprint "eagle-import:0805")
      (libsource (lib "eagle-import") (part "L0805"))
    )
    (comp (ref "L10")
      (value "DFE252012F")
      (footprint "eagle-import:L2520")
      (libsource (lib "eagle-import") (part "DFE252012F"))
    )
    (comp (ref "L11")
      (value "600R")
      (footprint "eagle-import:0805")
      (libsource (lib "eagle-import") (part "L0805"))
    )
    (comp (ref "L12")
      (value "600R")
      (footprint "eagle-import:0805")
      (libsource (lib "eagle-import") (part "L0805"))
    )
    (comp (ref "L13")
      (value "DFE252012F")
      (footprint "eagle-import:L2520")
      (libsource (lib "eagle-import") (part "DFE252012F"))
    )
    (comp (ref "L14")
      (value "600R")
      (footprint "eagle-import:0805")
      (libsource (lib "eagle-import") (part "L0805"))
    )
    (comp (ref "LED1")
      (value "LG L29K-G2J1-24")
      (footprint "eagle-import:LED-603")
      (libsource (lib "eagle-import") (part "LED-0603"))
    )
    (comp (ref "LED2")
      (value "LG L29K-G2J1-24")
      (footprint "eagle-import:LED-603")
      (libsource (lib "eagle-import") (part "LED-0603"))
    )
    (comp (ref "LED3")
      (value "LG L29K-G2J1-24")
      (footprint "eagle-import:LED-603")
      (libsource (lib "eagle-import") (part "LED-0603"))
    )
    (comp (ref "LED4")
      (value "LG L29K-G2J1-24")
      (footprint "eagle-import:LED-603")
      (libsource (lib "eagle-import") (part "LED-0603"))
    )
    (comp (ref "LED5")
      (value "LG L29K-G2J1-24")
      (footprint "eagle-import:LED-603")
      (libsource (lib "eagle-import") (part "LED-0603"))
    )
    (comp (ref "LED6")
      (value "LG L29K-G2J1-24")
      (footprint "eagle-import:LED-603")
      (libsource (lib "eagle-import") (part "LED-0603"))
    )
    (comp (ref "M1")
      (value "XT1861B")
      (footprint "eagle-import:SOT23")
      (libsource (lib "eagle-import") (part "XT1861B"))
    )
    (comp (ref "M2")
      (value "XT1861B")
      (footprint "eagle-import:SOT23")
      (libsource (lib "eagle-import") (part "XT1861B"))
    )
    (comp (ref "M3")
      (value "XT1861B")
      (footprint "eagle-import:SOT23")
      (libsource (lib "eagle-import") (part "XT1861B"))
    )
    (comp (ref "P1")
      (value "B3B-PH-K")
      (footprint "eagle-import:B3B-PH-K")
      (libsource (lib "eagle-import") (part "B3B-PH-K"))
    )
    (comp (ref "P2")
      (value "B3B-PH-K")
      (footprint "eagle-import:B3B-PH-K")
      (libsource (lib "eagle-import") (part "B3B-PH-K"))
    )
    (comp (ref "Q1")
      (value "BSS84")
      (footprint "eagle-import:SOT23")
      (libsource (lib "eagle-import") (part "BSS84"))
    )
    (comp (ref "Q2")
      (value "BSS84")
      (footprint "eagle-import:SOT23")
      (libsource (lib "eagle-import") (part "BSS84"))
    )
    (comp (ref "Q3")
      (value "BSS84")
      (footprint "eagle-import:SOT23")
      (libsource (lib "eagle-import") (part "BSS84"))
    )
    (comp (ref "Q4")
      (value "25MHz")
      (footprint "eagle-import:HC49U-V")
      (libsource (lib "eagle-import") (part "CRYSTALHC49U-V"))
    )
    (comp (ref "Q5")
      (value "BSS84")
      (footprint "eagle-import:SOT23")
      (libsource (lib "eagle-import") (part "BSS84"))
    )
    (comp (ref "Q6")
      (value "8MHz")
      (footprint "eagle-import:HC49U-V")
      (libsource (lib "eagle-import") (part "CRYSTALHC49U-V"))
    )
    (comp (ref "Q7")
      (value "BSS84")
      (footprint "eagle-import:SOT23")
      (libsource (lib "eagle-import") (part "BSS84"))
    )
    (comp (ref "Q8")
      (value "BSS123")
      (footprint "eagle-import:SOT23")
      (libsource (lib "eagle-import") (part "BSS123"))
    )
    (comp (ref "Q9")
      (value "FDN338")
      (footprint "eagle-import:SUPER-SOT3")
      (libsource (lib "eagle-import") (part "FDN360P"))
    )
    (comp (ref "Q10")
      (value "BSS84")
      (footprint "eagle-import:SOT23")
      (libsource (lib "eagle-import") (part "BSS84"))
    )
    (comp (ref "Q11")
      (value "8MHz")
      (footprint "eagle-import:HC49U-V")
      (libsource (lib "eagle-import") (part "CRYSTALHC49U-V"))
    )
    (comp (ref "R1")
      (value "470K")
      (footprint "eagle-import:0603")
      (libsource (lib "eagle-import") (part "R0603"))
    )
    (comp (ref "R2")
      (value "2K2")
      (footprint "eagle-import:0603")
      (libsource (lib "eagle-import") (part "R0603"))
    )
    (comp (ref "R3")
      (value "10K")
      (footprint "eagle-import:0603")
      (libsource (lib "eagle-import") (part "R0603"))
    )
    (comp (ref "R4")
      (value "10K")
      (footprint "eagle-import:0603")
      (libsource (lib "eagle-import") (part "R0603"))
    )
    (comp (ref "R5")
      (value "2K2")
      (footprint "eagle-import:0603")
      (libsource (lib "eagle-import") (part "R0603"))
    )
    (comp (ref "R6")
      (value "10K")
      (footprint "eagle-import:0603")
      (libsource (lib "eagle-import") (part "R0603"))
    )
    (comp (ref "R7")
      (value "10K")
      (footprint "eagle-import:0603")
      (libsource (lib "eagle-import") (part "R0603"))
    )
    (comp (ref "R8")
      (value "2K2")
      (footprint "eagle-import:0603")
      (libsource (lib "eagle-import") (part "R0603"))
    )
    (comp (ref "R9")
      (value "2K2")
      (footprint "eagle-import:0603")
      (libsource (lib "eagle-import") (part "R0603"))
    )
    (comp (ref "R10")
      (value "2K2")
      (footprint "eagle-import:0603")
      (libsource (lib "eagle-import") (part "R0603"))
    )
    (comp (ref "R11")
      (value "10K")
      (footprint "eagle-import:0603")
      (libsource (lib "eagle-import") (part "R0603"))
    )
    (comp (ref "R12")
      (value "20R")
      (footprint "eagle-import:0603")
      (libsource (lib "eagle-import") (part "R0603"))
    )
    (comp (ref "R13")
      (value "330R")
      (footprint "eagle-import:0603")
      (libsource (lib "eagle-import") (part "R0603"))
    )
    (comp (ref "R14")
      (value "20R")
      (footprint "eagle-import:0603")
      (libsource (lib "eagle-import") (part "R0603"))
    )
    (comp (ref "R15")
      (value "330R")
      (footprint "eagle-import:0603")
      (libsource (lib "eagle-import") (part "R0603"))
    )
    (comp (ref "R16")
      (value "330R")
      (footprint "eagle-import:0603")
      (libsource (lib "eagle-import") (part "R0603"))
    )
    (comp (ref "R17")
      (value "330R")
      (footprint "eagle-import:0603")
      (libsource (lib "eagle-import") (part "R0603"))
    )
    (comp (ref "R18")
      (value "330R")
      (footprint "eagle-import:0603")
      (libsource (lib "eagle-import") (part "R0603"))
    )
    (comp (ref "R19")
      (value "330R")
      (footprint "eagle-import:0603")
      (libsource (lib "eagle-import") (part "R0603"))
    )
    (comp (ref "R20")
      (value "330R")
      (footprint "eagle-import:0603")
      (libsource (lib "eagle-import") (part "R0603"))
    )
    (comp (ref "R21")
      (value "330R")
      (footprint "eagle-import:0603")
      (libsource (lib "eagle-import") (part "R0603"))
    )
    (comp (ref "R22")
      (value "10K")
      (footprint "eagle-import:0603")
      (libsource (lib "eagle-import") (part "R0603"))
    )
    (comp (ref "R23")
      (value "240K")
      (footprint "eagle-import:0603")
      (libsource (lib "eagle-import") (part "R0603"))
    )
    (comp (ref "R24")
      (value "240K")
      (footprint "eagle-import:0603")
      (libsource (lib "eagle-import") (part "R0603"))
    )
    (comp (ref "R25")
      (value "10K")
      (footprint "eagle-import:0603")
      (libsource (lib "eagle-import") (part "R0603"))
    )
    (comp (ref "R26")
      (value "20K")
      (footprint "eagle-import:0603")
      (libsource (lib "eagle-import") (part "R0603"))
    )
    (comp (ref "R27")
      (value "20K")
      (footprint "eagle-import:0603")
      (libsource (lib "eagle-import") (part "R0603"))
    )
    (comp (ref "R28")
      (value "20K")
      (footprint "eagle-import:0603")
      (libsource (lib "eagle-import") (part "R0603"))
    )
    (comp (ref "R29")
      (value "6K2")
      (footprint "eagle-import:0603")
      (libsource (lib "eagle-import") (part "R0603"))
    )
    (comp (ref "R30")
      (value "12K1")
      (footprint "eagle-import:0603")
      (libsource (lib "eagle-import") (part "R0603"))
    )
    (comp (ref "R31")
      (value "100K")
      (footprint "eagle-import:0603")
      (libsource (lib "eagle-import") (part "R0603"))
    )
    (comp (ref "R32")
      (value "20K")
      (footprint "eagle-import:0603")
      (libsource (lib "eagle-import") (part "R0603"))
    )
    (comp (ref "R33")
      (value "100K")
      (footprint "eagle-import:0603")
      (libsource (lib "eagle-import") (part "R0603"))
    )
    (comp (ref "R34")
      (value "20K")
      (footprint "eagle-import:0603")
      (libsource (lib "eagle-import") (part "R0603"))
    )
    (comp (ref "R35")
      (value "2K2/DNP")
      (footprint "eagle-import:0603")
      (libsource (lib "eagle-import") (part "R0603"))
    )
    (comp (ref "R36")
      (value "10K")
      (footprint "eagle-import:0603")
      (libsource (lib "eagle-import") (part "R0603"))
    )
    (comp (ref "R37")
      (value "2K2/DNP")
      (footprint "eagle-import:0603")
      (libsource (lib "eagle-import") (part "R0603"))
    )
    (comp (ref "R38")
      (value "2K2")
      (footprint "eagle-import:0603")
      (libsource (lib "eagle-import") (part "R0603"))
    )
    (comp (ref "R39")
      (value "49R9")
      (footprint "eagle-import:0603")
      (libsource (lib "eagle-import") (part "R0603"))
    )
    (comp (ref "R40")
      (value "0R")
      (footprint "eagle-import:0603")
      (libsource (lib "eagle-import") (part "R0603"))
    )
    (comp (ref "R41")
      (value "49R9")
      (footprint "eagle-import:0603")
      (libsource (lib "eagle-import") (part "R0603"))
    )
    (comp (ref "R42")
      (value "2K2")
      (footprint "eagle-import:0603")
      (libsource (lib "eagle-import") (part "R0603"))
    )
    (comp (ref "R43")
      (value "10K")
      (footprint "eagle-import:0603")
      (libsource (lib "eagle-import") (part "R0603"))
    )
    (comp (ref "R44")
      (value "49R9")
      (footprint "eagle-import:0603")
      (libsource (lib "eagle-import") (part "R0603"))
    )
    (comp (ref "R45")
      (value "2K2")
      (footprint "eagle-import:0603")
      (libsource (lib "eagle-import") (part "R0603"))
    )
    (comp (ref "R46")
      (value "49R9")
      (footprint "eagle-import:0603")
      (libsource (lib "eagle-import") (part "R0603"))
    )
    (comp (ref "R47")
      (value "20R")
      (footprint "eagle-import:0603")
      (libsource (lib "eagle-import") (part "R0603"))
    )
    (comp (ref "R48")
      (value "20R")
      (footprint "eagle-import:0603")
      (libsource (lib "eagle-import") (part "R0603"))
    )
    (comp (ref "R49")
      (value "0R/DNP")
      (footprint "eagle-import:0603")
      (libsource (lib "eagle-import") (part "R0603"))
    )
    (comp (ref "R50")
      (value "100R")
      (footprint "eagle-import:0603")
      (libsource (lib "eagle-import") (part "R0603"))
    )
    (comp (ref "R51")
      (value "100R")
      (footprint "eagle-import:0603")
      (libsource (lib "eagle-import") (part "R0603"))
    )
    (comp (ref "R52")
      (value "10K")
      (footprint "eagle-import:0603")
      (libsource (lib "eagle-import") (part "R0603"))
    )
    (comp (ref "R53")
      (value "1K5/DNP")
      (footprint "eagle-import:0603")
      (libsource (lib "eagle-import") (part "R0603"))
    )
    (comp (ref "R54")
      (value "330R")
      (footprint "eagle-import:0603")
      (libsource (lib "eagle-import") (part "R0603"))
    )
    (comp (ref "R55")
      (value "330R")
      (footprint "eagle-import:0603")
      (libsource (lib "eagle-import") (part "R0603"))
    )
    (comp (ref "R56")
      (value "100R")
      (footprint "eagle-import:0603")
      (libsource (lib "eagle-import") (part "R0603"))
    )
    (comp (ref "R57")
      (value "100R")
      (footprint "eagle-import:0603")
      (libsource (lib "eagle-import") (part "R0603"))
    )
    (comp (ref "R58")
      (value "100R")
      (footprint "eagle-import:0603")
      (libsource (lib "eagle-import") (part "R0603"))
    )
    (comp (ref "R59")
      (value "100R")
      (footprint "eagle-import:0603")
      (libsource (lib "eagle-import") (part "R0603"))
    )
    (comp (ref "R60")
      (value "100R")
      (footprint "eagle-import:0603")
      (libsource (lib "eagle-import") (part "R0603"))
    )
    (comp (ref "R61")
      (value "100R")
      (footprint "eagle-import:0603")
      (libsource (lib "eagle-import") (part "R0603"))
    )
    (comp (ref "R62")
      (value "100R")
      (footprint "eagle-import:0603")
      (libsource (lib "eagle-import") (part "R0603"))
    )
    (comp (ref "R63")
      (value "100K")
      (footprint "eagle-import:0603")
      (libsource (lib "eagle-import") (part "R0603"))
    )
    (comp (ref "R64")
      (value "6K2")
      (footprint "eagle-import:0603")
      (libsource (lib "eagle-import") (part "R0603"))
    )
    (comp (ref "R65")
      (value "0R")
      (footprint "eagle-import:0603")
      (libsource (lib "eagle-import") (part "R0603"))
    )
    (comp (ref "R66")
      (value "0R")
      (footprint "eagle-import:0603")
      (libsource (lib "eagle-import") (part "R0603"))
    )
    (comp (ref "R67")
      (value "0R")
      (footprint "eagle-import:0603")
      (libsource (lib "eagle-import") (part "R0603"))
    )
    (comp (ref "R68")
      (value "0R/DNP")
      (footprint "eagle-import:0603")
      (libsource (lib "eagle-import") (part "R0603"))
    )
    (comp (ref "R69")
      (value "0R")
      (footprint "eagle-import:0603")
      (libsource (lib "eagle-import") (part "R0603"))
    )
    (comp (ref "R70")
      (value "0R/DNP")
      (footprint "eagle-import:0603")
      (libsource (lib "eagle-import") (part "R0603"))
    )
    (comp (ref "R71")
      (value "1K5/DNP")
      (footprint "eagle-import:0603")
      (libsource (lib "eagle-import") (part "R0603"))
    )
    (comp (ref "R72")
      (value "1K5/DNP")
      (footprint "eagle-import:0603")
      (libsource (lib "eagle-import") (part "R0603"))
    )
    (comp (ref "R73")
      (value "240K")
      (footprint "eagle-import:0603")
      (libsource (lib "eagle-import") (part "R0603"))
    )
    (comp (ref "R74")
      (value "10K")
      (footprint "eagle-import:0603")
      (libsource (lib "eagle-import") (part "R0603"))
    )
    (comp (ref "R75")
      (value "10K")
      (footprint "eagle-import:0603")
      (libsource (lib "eagle-import") (part "R0603"))
    )
    (comp (ref "R76")
      (value "10K")
      (footprint "eagle-import:0603")
      (libsource (lib "eagle-import") (part "R0603"))
    )
    (comp (ref "R77")
      (value "1K5/DNP")
      (footprint "eagle-import:0603")
      (libsource (lib "eagle-import") (part "R0603"))
    )
    (comp (ref "R78")
      (value "20R")
      (footprint "eagle-import:0603")
      (libsource (lib "eagle-import") (part "R0603"))
    )
    (comp (ref "R79")
      (value "20R")
      (footprint "eagle-import:0603")
      (libsource (lib "eagle-import") (part "R0603"))
    )
    (comp (ref "R80")
      (value "1K5/DNP")
      (footprint "eagle-import:0603")
      (libsource (lib "eagle-import") (part "R0603"))
    )
    (comp (ref "R81")
      (value "10K")
      (footprint "eagle-import:0603")
      (libsource (lib "eagle-import") (part "R0603"))
    )
    (comp (ref "R82")
      (value "10K")
      (footprint "eagle-import:0603")
      (libsource (lib "eagle-import") (part "R0603"))
    )
    (comp (ref "R83")
      (value "10K")
      (footprint "eagle-import:0603")
      (libsource (lib "eagle-import") (part "R0603"))
    )
    (comp (ref "S1")
      (value "SWITCHES_-SMD-1101NE")
      (footprint "eagle-import:TACTILE-SWITCH-1101NE")
      (libsource (lib "eagle-import") (part "SWITCHES_-SMD-1101NE"))
    )
    (comp (ref "S2")
      (value "SWITCHES_-SMD-1101NE")
      (footprint "eagle-import:TACTILE-SWITCH-1101NE")
      (libsource (lib "eagle-import") (part "SWITCHES_-SMD-1101NE"))
    )
    (comp (ref "S3")
      (value "SWITCHES_-SMD-1101NE")
      (footprint "eagle-import:TACTILE-SWITCH-1101NE")
      (libsource (lib "eagle-import") (part "SWITCHES_-SMD-1101NE"))
    )
    (comp (ref "SJ1")
      (value "SOLDERJUMPERNC")
      (footprint "eagle-import:SJ_2S_SMALL")
      (libsource (lib "eagle-import") (part "SOLDERJUMPERNC"))
    )
    (comp (ref "T1")
      (value "Hanrun HR917550A")
      (footprint "eagle-import:HR13550A")
      (libsource (lib "eagle-import") (part "HR913550A"))
    )
    (comp (ref "TP11")
      (value "TPPAD1-13")
      (footprint "eagle-import:P1-13")
      (libsource (lib "eagle-import") (part "TPPAD1-13"))
    )
    (comp (ref "TP12")
      (value "TPPAD1-13")
      (footprint "eagle-import:P1-13")
      (libsource (lib "eagle-import") (part "TPPAD1-13"))
    )
    (comp (ref "TP13")
      (value "TPPAD1-13")
      (footprint "eagle-import:P1-13")
      (libsource (lib "eagle-import") (part "TPPAD1-13"))
    )
    (comp (ref "TP14")
      (value "TPTP07SQ")
      (footprint "eagle-import:TP07SQ")
      (libsource (lib "eagle-import") (part "TPTP07SQ"))
    )
    (comp (ref "TP15")
      (value "TPTP07SQ")
      (footprint "eagle-import:TP07SQ")
      (libsource (lib "eagle-import") (part "TPTP07SQ"))
    )
    (comp (ref "TP16")
      (value "TPTP07SQ")
      (footprint "eagle-import:TP07SQ")
      (libsource (lib "eagle-import") (part "TPTP07SQ"))
    )
    (comp (ref "TP17")
      (value "TPTP07SQ")
      (footprint "eagle-import:TP07SQ")
      (libsource (lib "eagle-import") (part "TPTP07SQ"))
    )
    (comp (ref "TP18")
      (value "TPTP07SQ")
      (footprint "eagle-import:TP07SQ")
      (libsource (lib "eagle-import") (part "TPTP07SQ"))
    )
    (comp (ref "TP20")
      (value "TPTP12SQ")
      (footprint "eagle-import:TP12SQ")
      (libsource (lib "eagle-import") (part "TPTP12SQ"))
    )
    (comp (ref "TP21")
      (value "TPTP12SQ")
      (footprint "eagle-import:TP12SQ")
      (libsource (lib "eagle-import") (part "TPTP12SQ"))
    )
    (comp (ref "TP22")
      (value "TPTP12SQ")
      (footprint "eagle-import:TP12SQ")
      (libsource (lib "eagle-import") (part "TPTP12SQ"))
    )
    (comp (ref "TP23")
      (value "TPTP12SQ")
      (footprint "eagle-import:TP12SQ")
      (libsource (lib "eagle-import") (part "TPTP12SQ"))
    )
    (comp (ref "TP24")
      (value "TPTP12SQ")
      (footprint "eagle-import:TP12SQ")
      (libsource (lib "eagle-import") (part "TPTP12SQ"))
    )
    (comp (ref "TP25")
      (value "TPTP12SQ")
      (footprint "eagle-import:TP12SQ")
      (libsource (lib "eagle-import") (part "TPTP12SQ"))
    )
    (comp (ref "TP26")
      (value "TPTP12SQ")
      (footprint "eagle-import:TP12SQ")
      (libsource (lib "eagle-import") (part "TPTP12SQ"))
    )
    (comp (ref "TP27")
      (value "TPTP12SQ")
      (footprint "eagle-import:TP12SQ")
      (libsource (lib "eagle-import") (part "TPTP12SQ"))
    )
    (comp (ref "TP28")
      (value "TPTP12SQ")
      (footprint "eagle-import:TP12SQ")
      (libsource (lib "eagle-import") (part "TPTP12SQ"))
    )
    (comp (ref "TP29")
      (value "TPTP12SQ")
      (footprint "eagle-import:TP12SQ")
      (libsource (lib "eagle-import") (part "TPTP12SQ"))
    )
    (comp (ref "U$1")
      (value "PIN-1X4")
      (footprint "eagle-import:PIN-1X4")
      (libsource (lib "eagle-import") (part "PIN-1X4"))
    )
    (comp (ref "U$2")
      (value "STM32F072CBT6")
      (footprint "eagle-import:LQFP48")
      (libsource (lib "eagle-import") (part "STM32F072CBT6"))
    )
    (comp (ref "U$3")
      (value "SR410361N")
      (footprint "eagle-import:LCD_7SEG_4DIGIT")
      (libsource (lib "eagle-import") (part "SR410361N"))
    )
    (comp (ref "U$4")
      (value "STM8S003F3P6")
      (footprint "eagle-import:TSSOP20")
      (libsource (lib "eagle-import") (part "STM8S003F3P6"))
    )
    (comp (ref "U$5")
      (value "P25QXH")
      (footprint "eagle-import:SOIC8")
      (libsource (lib "eagle-import") (part "P25QXH"))
    )
    (comp (ref "U$6")
      (value "PIN-1X8")
      (footprint "eagle-import:PIN-1X8")
      (libsource (lib "eagle-import") (part "PIN-1X8"))
    )
    (comp (ref "U$7")
      (value "PFS154-S16")
      (footprint "eagle-import:SOIC16-N")
      (libsource (lib "eagle-import") (part "PFS154-S16"))
    )
    (comp (ref "U$8")
      (value "PIN-1X4")
      (footprint "eagle-import:PIN-1X4")
      (libsource (lib "eagle-import") (part "PIN-1X4"))
    )
    (comp (ref "U$9")
      (value "TSSOP16")
      (footprint "eagle-import:TSSOP16")
      (libsource (lib "eagle-import") (part "TSSOP16"))
    )
    (comp (ref "U$10")
      (value "PIN-1X4")
      (footprint "eagle-import:PIN-1X4")
      (libsource (lib "eagle-import") (part "PIN-1X4"))
    )
    (comp (ref "U$11")
      (value "PIN-1X8")
      (footprint "eagle-import:PIN-1X8")
      (libsource (lib "eagle-import") (part "PIN-1X8"))
    )
    (comp (ref "U$12")
      (value "PIN-1X4")
      (footprint "eagle-import:PIN-1X4")
      (libsource (lib "eagle-import") (part "PIN-1X4"))
    )
    (comp (ref "U$13")
      (value "PMS150C-U06")
      (footprint "eagle-import:SOT23-6")
      (libsource (lib "eagle-import") (part "PMS150C-U06"))
    )
    (comp (ref "U$14")
      (value "AP2000")
      (footprint "eagle-import:SOT23-6")
      (libsource (lib "eagle-import") (part "AP2000"))
    )
    (comp (ref "U$15")
      (value "MT3608")
      (footprint "eagle-import:SOT23-6")
      (libsource (lib "eagle-import") (part "MT3608"))
    )
    (comp (ref "U$16")
      (value "PIN-1X10")
      (footprint "eagle-import:PIN-1X10")
      (libsource (lib "eagle-import") (part "PIN-1X10"))
    )
    (comp (ref "U$17")
      (value "PIN-1X10")
      (footprint "eagle-import:PIN-1X10")
      (libsource (lib "eagle-import") (part "PIN-1X10"))
    )
    (comp (ref "U$18")
      (value "PIN-1X10")
      (footprint "eagle-import:PIN-1X10")
      (libsource (lib "eagle-import") (part "PIN-1X10"))
    )
    (comp (ref "U$19")
      (value "STM32F030F4P6")
      (footprint "eagle-import:TSSOP20")
      (libsource (lib "eagle-import") (part "STM32F030F4P6"))
    )
    (comp (ref "U$20")
      (value "PFS154-S16")
      (footprint "eagle-import:SOIC16-N")
      (libsource (lib "eagle-import") (part "PFS154-S16"))
    )
    (comp (ref "U$21")
      (value "PIN-1X8")
      (footprint "eagle-import:PIN-1X8")
      (libsource (lib "eagle-import") (part "PIN-1X8"))
    )
    (comp (ref "U$22")
      (value "PIN-1X4")
      (footprint "eagle-import:PIN-1X4")
      (libsource (lib "eagle-import") (part "PIN-1X4"))
    )
    (comp (ref "U$23")
      (value "PIN-1X8")
      (footprint "eagle-import:PIN-1X8")
      (libsource (lib "eagle-import") (part "PIN-1X8"))
    )
    (comp (ref "U$25")
      (value "PN532_NFCB")
      (footprint "eagle-import:HW-147-NFC-NOHOLES")
      (libsource (lib "eagle-import") (part "PN532_NFCB"))
    )
    (comp (ref "U$26")
      (value "PIN-1X10")
      (footprint "eagle-import:PIN-1X10")
      (libsource (lib "eagle-import") (part "PIN-1X10"))
    )
    (comp (ref "U$27")
      (value "PIN-1X10")
      (footprint "eagle-import:PIN-1X10")
      (libsource (lib "eagle-import") (part "PIN-1X10"))
    )
    (comp (ref "U$28")
      (value "MIC550X")
      (footprint "eagle-import:SOT23-5L")
      (libsource (lib "eagle-import") (part "MIC550X"))
    )
    (comp (ref "U$29")
      (value "STM32F070F6")
      (footprint "eagle-import:TSSOP20")
      (libsource (lib "eagle-import") (part "STM32F070F6"))
    )
    (comp (ref "U$30")
      (value "PIN-1X4")
      (footprint "eagle-import:PIN-1X4")
      (libsource (lib "eagle-import") (part "PIN-1X4"))
    )
    (comp (ref "U1")
      (value "STM32F107RCT6")
      (footprint "eagle-import:QFP50P1200X1200X160-64N")
      (libsource (lib "eagle-import") (part "STM32F107RCT6"))
    )
    (comp (ref "U2")
      (value "ESP-WROOM-32")
      (footprint "eagle-import:ESP-WROOM-32")
      (libsource (lib "eagle-import") (part "ESP-WROOM-32"))
    )
    (comp (ref "U3")
      (value "MIC550X")
      (footprint "eagle-import:SOT23-5L")
      (libsource (lib "eagle-import") (part "MIC550X"))
    )
    (comp (ref "U4")
      (value "ATTINY24A-SSU")
      (footprint "eagle-import:SOIC127P600X175-14N")
      (libsource (lib "eagle-import") (part "ATTINY24A-SSU"))
    )
    (comp (ref "USB1")
      (value "CON-USB-F-MICRO-B")
      (footprint "eagle-import:CONN_USB_MICRO-B")
      (libsource (lib "eagle-import") (part "CON-USB-F-MICRO-B"))
    )
    (comp (ref "USB2")
      (value "CON-USB-F-MICRO-B")
      (footprint "eagle-import:CONN_USB_MICRO-B")
      (libsource (lib "eagle-import") (part "CON-USB-F-MICRO-B"))
    )
    (comp (ref "USB3")
      (value "CON-USB-F-MICRO-B")
      (footprint "eagle-import:CONN_USB_MICRO-B")
      (libsource (lib "eagle-import") (part "CON-USB-F-MICRO-B"))
    )
    (comp (ref "VDD")
      (value "TPTP10R")
      (footprint "eagle-import:TP10R")
      (libsource (lib "eagle-import") (part "TPTP10R"))
    )
    (comp (ref "VPP")
      (value "TPTP10R")
      (footprint "eagle-import:TP10R")
      (libsource (lib "eagle-import") (part "TPTP10R"))
    )
    (comp (ref "X1")
      (value "FH12-40S-0.5SH")
      (footprint "eagle-import:FH12-40S-0.5SH")
      (fields (field (name "MPN") "FH12-40S-0.5SH(55)"))
      (libsource (lib "eagle-import") (part "FH12-40S-0.5SH"))
    )
    (comp (ref "X2")
      (value "FH12-40S-0.5SH")
      (footprint "eagle-import:FH12-40S-0.5SH")
      (fields (field (name "MPN") "FH12-40S-0.5SH(55)"))
      (libsource (lib "eagle-import") (part "FH12-40S-0.5SH"))
    )
  )
  (nets
    (net (code "1") (name "+3V3") (class "Default")
      (node (ref "BOOT1") (pin "2") (pinfunction "2_2") (pintype "passive"))
      (node (ref "BOOT2") (pin "2") (pinfunction "2_2") (pintype "passive"))
      (node (ref "C1") (pin "1") (pinfunction "1_1") (pintype "passive"))
      (node (ref "C10") (pin "2") (pinfunction "2_2") (pintype "passive"))
      (node (ref "C11") (pin "2") (pinfunction "2_2") (pintype "passive"))
      (node (ref "C15") (pin "2") (pinfunction "2_2") (pintype "passive"))
      (node (ref "C16") (pin "2") (pinfunction "2_2") (pintype "passive"))
      (node (ref "C17") (pin "2") (pinfunction "2_2") (pintype "passive"))
      (node (ref "C2") (pin "1") (pinfunction "1_1") (pintype "passive"))
      (node (ref "C22") (pin "1") (pinfunction "1_1") (pintype "passive"))
      (node (ref "C24") (pin "1") (pinfunction "1_1") (pintype "passive"))
      (node (ref "C27") (pin "1") (pinfunction "1_1") (pintype "passive"))
      (node (ref "C3") (pin "1") (pinfunction "1_1") (pintype "passive"))
      (node (ref "C30") (pin "2") (pinfunction "2_2") (pintype "passive"))
      (node (ref "C33") (pin "2") (pinfunction "2_2") (pintype "passive"))
      (node (ref "C38") (pin "2") (pinfunction "2_2") (pintype "passive"))
      (node (ref "C39") (pin "2") (pinfunction "2_2") (pintype "passive"))
      (node (ref "C4") (pin "1") (pinfunction "1_1") (pintype "passive"))
      (node (ref "C47") (pin "1") (pinfunction "1_1") (pintype "passive"))
      (node (ref "C48") (pin "2") (pinfunction "2_2") (pintype "passive"))
      (node (ref "C49") (pin "1") (pinfunction "1_1") (pintype "passive"))
      (node (ref "C50") (pin "2") (pinfunction "2_2") (pintype "passive"))
      (node (ref "C52") (pin "1") (pinfunction "1_1") (pintype "passive"))
      (node (ref "C62") (pin "2") (pinfunction "2_2") (pintype "passive"))
      (node (ref "C64") (pin "2") (pinfunction "2_2") (pintype "passive"))
      (node (ref "C65") (pin "2") (pinfunction "2_2") (pintype "passive"))
      (node (ref "C68") (pin "2") (pinfunction "2_2") (pintype "passive"))
      (node (ref "C69") (pin "2") (pinfunction "2_2") (pintype "passive"))
      (node (ref "C76") (pin "2") (pinfunction "2_2") (pintype "passive"))
      (node (ref "C77") (pin "2") (pinfunction "2_2") (pintype "passive"))
      (node (ref "C79") (pin "2") (pinfunction "2_2") (pintype "passive"))
      (node (ref "C8") (pin "2") (pinfunction "2_2") (pintype "passive"))
      (node (ref "C80") (pin "2") (pinfunction "2_2") (pintype "passive"))
      (node (ref "IC1") (pin "1") (pinfunction "VDD2A_1") (pintype "bidirectional"))
      (node (ref "IC1") (pin "19") (pinfunction "VDD1A_19") (pintype "bidirectional"))
      (node (ref "IC1") (pin "9") (pinfunction "VDDIO_9") (pintype "bidirectional"))
      (node (ref "IC4") (pin "4") (pinfunction "FB_4") (pintype "power_in"))
      (node (ref "J2") (pin "2") (pinfunction "2_2") (pintype "passive"))
      (node (ref "J5") (pin "2") (pinfunction "2_2") (pintype "passive"))
      (node (ref "JP1") (pin "2") (pinfunction "2_2") (pintype "passive"))
      (node (ref "JP9") (pin "1") (pinfunction "1_1") (pintype "passive"))
      (node (ref "L1") (pin "1") (pinfunction "1_1") (pintype "passive"))
      (node (ref "L11") (pin "2") (pinfunction "2_2") (pintype "passive"))
      (node (ref "L12") (pin "1") (pinfunction "1_1") (pintype "passive"))
      (node (ref "L13") (pin "P$2") (pinfunction "2_P$2") (pintype "passive"))
      (node (ref "L5") (pin "1") (pinfunction "1_1") (pintype "passive"))
      (node (ref "LED1") (pin "A") (pinfunction "A_A") (pintype "passive"))
      (node (ref "LED2") (pin "A") (pinfunction "A_A") (pintype "passive"))
      (node (ref "LED3") (pin "A") (pinfunction "A_A") (pintype "passive"))
      (node (ref "LED4") (pin "A") (pinfunction "A_A") (pintype "passive"))
      (node (ref "LED5") (pin "A") (pinfunction "A_A") (pintype "passive"))
      (node (ref "LED6") (pin "A") (pinfunction "A_A") (pintype "passive"))
      (node (ref "M1") (pin "3") (pinfunction "VOUT_3") (pintype "passive"))
      (node (ref "M3") (pin "3") (pinfunction "VOUT_3") (pintype "passive"))
      (node (ref "Q1") (pin "2") (pinfunction "S_2") (pintype "passive"))
      (node (ref "Q2") (pin "2") (pinfunction "S_2") (pintype "passive"))
      (node (ref "Q3") (pin "2") (pinfunction "S_2") (pintype "passive"))
      (node (ref "Q5") (pin "2") (pinfunction "S_2") (pintype "passive"))
      (node (ref "Q7") (pin "2") (pinfunction "S_2") (pintype "passive"))
      (node (ref "Q9") (pin "2") (pinfunction "S_2") (pintype "passive"))
      (node (ref "R1") (pin "1") (pinfunction "1_1") (pintype "passive"))
      (node (ref "R10") (pin "2") (pinfunction "2_2") (pintype "passive"))
      (node (ref "R11") (pin "2") (pinfunction "2_2") (pintype "passive"))
      (node (ref "R22") (pin "2") (pinfunction "2_2") (pintype "passive"))
      (node (ref "R25") (pin "2") (pinfunction "2_2") (pintype "passive"))
      (node (ref "R35") (pin "2") (pinfunction "2_2") (pintype "passive"))
      (node (ref "R36") (pin "2") (pinfunction "2_2") (pintype "passive"))
      (node (ref "R37") (pin "2") (pinfunction "2_2") (pintype "passive"))
      (node (ref "R4") (pin "2") (pinfunction "2_2") (pintype "passive"))
      (node (ref "R52") (pin "2") (pinfunction "2_2") (pintype "passive"))
      (node (ref "R53") (pin "2") (pinfunction "2_2") (pintype "passive"))
      (node (ref "R54") (pin "2") (pinfunction "2_2") (pintype "passive"))
      (node (ref "R55") (pin "2") (pinfunction "2_2") (pintype "passive"))
      (node (ref "R6") (pin "2") (pinfunction "2_2") (pintype "passive"))
      (node (ref "R63") (pin "1") (pinfunction "1_1") (pintype "passive"))
      (node (ref "R7") (pin "2") (pinfunction "2_2") (pintype "passive"))
      (node (ref "R75") (pin "2") (pinfunction "2_2") (pintype "passive"))
      (node (ref "R8") (pin "2") (pinfunction "2_2") (pintype "passive"))
      (node (ref "R80") (pin "2") (pinfunction "2_2") (pintype "passive"))
      (node (ref "R83") (pin "2") (pinfunction "2_2") (pintype "passive"))
      (node (ref "U$1") (pin "1") (pinfunction "1_1") (pintype "passive"))
      (node (ref "U$10") (pin "4") (pinfunction "4_4") (pintype "passive"))
      (node (ref "U$19") (pin "16") (pinfunction "VDD_16") (pintype "power_in"))
      (node (ref "U$2") (pin "1") (pinfunction "VBAT_1") (pintype "power_in"))
      (node (ref "U$2") (pin "24") (pinfunction "VDD_24") (pintype "power_in"))
      (node (ref "U$2") (pin "36") (pinfunction "VDDIO2_36") (pintype "power_in"))
      (node (ref "U$2") (pin "48") (pinfunction "VDD_48") (pintype "power_in"))
      (node (ref "U$22") (pin "2") (pinfunction "2_2") (pintype "passive"))
      (node (ref "U$23") (pin "7") (pinfunction "7_7") (pintype "passive"))
      (node (ref "U$25") (pin "VCC") (pinfunction "VCC_VCC") (pintype "power_in"))
      (node (ref "U$25") (pin "VCC1") (pinfunction "VCC_VCC1") (pintype "power_in"))
      (node (ref "U$28") (pin "5") (pinfunction "VOUT_5") (pintype "power_in"))
      (node (ref "U$29") (pin "16") (pinfunction "VDD_16") (pintype "power_in"))
      (node (ref "U$29") (pin "5") (pinfunction "VDDA_5") (pintype "power_in"))
      (node (ref "U$30") (pin "1") (pinfunction "1_1") (pintype "passive"))
      (node (ref "U$4") (pin "9") (pinfunction "VDD_9") (pintype "power_in"))
      (node (ref "U$5") (pin "3") (pinfunction "NWP_3") (pintype "bidirectional"))
      (node (ref "U$5") (pin "8") (pinfunction "VCC_8") (pintype "power_in"))
      (node (ref "U$7") (pin "5") (pinfunction "VCC_5") (pintype "power_in"))
      (node (ref "U$8") (pin "1") (pinfunction "1_1") (pintype "passive"))
      (node (ref "U1") (pin "1") (pinfunction "VBAT_1") (pintype "power_in"))
      (node (ref "U1") (pin "19") (pinfunction "VDD_4_19") (pintype "power_in"))
      (node (ref "U1") (pin "32") (pinfunction "VDD_1_32") (pintype "power_in"))
      (node (ref "U1") (pin "48") (pinfunction "VDD_2_48") (pintype "power_in"))
      (node (ref "U1") (pin "64") (pinfunction "VDD_3_64") (pintype "power_in"))
      (node (ref "U3") (pin "5") (pinfunction "VOUT_5") (pintype "power_in"))
      (node (ref "X1") (pin "2") (pinfunction "1_2") (pintype "passive"))
      (node (ref "X1") (pin "3") (pinfunction "1_3") (pintype "passive"))
    )
    (net (code "2") (name "+15V") (class "Default")
      (node (ref "C13") (pin "1") (pinfunction "1_1") (pintype "passive"))
      (node (ref "C57") (pin "1") (pinfunction "1_1") (pintype "passive"))
      (node (ref "C58") (pin "2") (pinfunction "2_2") (pintype "passive"))
      (node (ref "C59") (pin "2") (pinfunction "2_2") (pintype "passive"))
      (node (ref "C9") (pin "1") (pinfunction "1_1") (pintype "passive"))
      (node (ref "D2") (pin "C") (pinfunction "C_C") (pintype "passive"))
      (node (ref "IC2") (pin "8") (pinfunction "V+_8") (pintype "power_in"))
      (node (ref "R73") (pin "2") (pinfunction "2_2") (pintype "passive"))
    )
    (net (code "3") (name "/+5V") (class "Default")
      (node (ref "C40") (pin "2") (pinfunction "2_2") (pintype "passive"))
      (node (ref "L7") (pin "1") (pinfunction "1_1") (pintype "passive"))
      (node (ref "USB2") (pin "P1") (pinfunction "VUSB_P1") (pintype "bidirectional"))
    )
    (net (code "4") (name "/+5V_FILT") (class "Default")
      (node (ref "C43") (pin "1") (pinfunction "1_1") (pintype "passive"))
      (node (ref "L7") (pin "2") (pinfunction "2_2") (pintype "passive"))
      (node (ref "Q10") (pin "2") (pinfunction "S_2") (pintype "passive"))
      (node (ref "R64") (pin "2") (pinfunction "2_2") (pintype "passive"))
      (node (ref "U3") (pin "1") (pinfunction "VIN_1") (pintype "power_in"))
      (node (ref "U3") (pin "3") (pinfunction "EN_3") (pintype "input"))
    )
    (net (code "5") (name "/A_MISO") (class "Default")
      (node (ref "J6") (pin "1") (pinfunction "1_1") (pintype "passive"))
      (node (ref "U4") (pin "8") (pinfunction "PA5_8") (pintype "bidirectional"))
    )
    (net (code "6") (name "/A_MOSI") (class "Default")
      (node (ref "J6") (pin "4") (pinfunction "4_4") (pintype "passive"))
      (node (ref "U4") (pin "7") (pinfunction "PA6_7") (pintype "bidirectional"))
    )
    (net (code "7") (name "/A_RESET") (class "Default")
      (node (ref "J6") (pin "5") (pinfunction "5_5") (pintype "passive"))
      (node (ref "U4") (pin "4") (pinfunction "PB3_4") (pintype "bidirectional"))
    )
    (net (code "8") (name "/A_SCK") (class "Default")
      (node (ref "J6") (pin "3") (pinfunction "3_3") (pintype "passive"))
      (node (ref "U4") (pin "9") (pinfunction "PA4_9") (pintype "bidirectional"))
    )
    (net (code "9") (name "/BOOT0") (class "Default")
      (node (ref "BOOT1") (pin "1") (pinfunction "1_1") (pintype "passive"))
      (node (ref "R43") (pin "2") (pinfunction "2_2") (pintype "passive"))
      (node (ref "U$2") (pin "38") (pinfunction "PA15_38") (pintype "bidirectional"))
      (node (ref "U$2") (pin "44") (pinfunction "BOOT0_44") (pintype "input"))
    )
    (net (code "10") (name "/CA0") (class "Default")
      (node (ref "Q1") (pin "1") (pinfunction "G_1") (pintype "passive"))
      (node (ref "R7") (pin "1") (pinfunction "1_1") (pintype "passive"))
      (node (ref "U$7") (pin "7") (pinfunction "PA6_7") (pintype "passive"))
    )
    (net (code "11") (name "/CA1") (class "Default")
      (node (ref "Q2") (pin "1") (pinfunction "G_1") (pintype "passive"))
      (node (ref "R11") (pin "1") (pinfunction "1_1") (pintype "passive"))
      (node (ref "U$7") (pin "6") (pinfunction "PA7_6") (pintype "passive"))
    )
    (net (code "12") (name "/CA2") (class "Default")
      (node (ref "Q3") (pin "1") (pinfunction "G_1") (pintype "passive"))
      (node (ref "R22") (pin "1") (pinfunction "1_1") (pintype "passive"))
      (node (ref "U$7") (pin "4") (pinfunction "PB7_4") (pintype "passive"))
    )
    (net (code "13") (name "/CA3") (class "Default")
      (node (ref "Q5") (pin "1") (pinfunction "G_1") (pintype "passive"))
      (node (ref "R25") (pin "1") (pinfunction "1_1") (pintype "passive"))
      (node (ref "U$7") (pin "3") (pinfunction "PB6_3") (pintype "passive"))
    )
    (net (code "14") (name "/CC_RST") (class "Default")
      (node (ref "U1") (pin "39") (pinfunction "PC8_39") (pintype "bidirectional"))
      (node (ref "X1") (pin "22") (pinfunction "1_22") (pintype "passive"))
    )
    (net (code "15") (name "/CC_RX") (class "Default")
      (node (ref "U1") (pin "53") (pinfunction "PC12_53") (pintype "bidirectional"))
      (node (ref "X1") (pin "17") (pinfunction "1_17") (pintype "passive"))
    )
    (net (code "16") (name "/CC_SS") (class "Default")
      (node (ref "U1") (pin "40") (pinfunction "PC9_40") (pintype "bidirectional"))
      (node (ref "X1") (pin "21") (pinfunction "1_21") (pintype "passive"))
    )
    (net (code "17") (name "/CC_TX") (class "Default")
      (node (ref "U1") (pin "54") (pinfunction "PD2_54") (pintype "bidirectional"))
      (node (ref "X1") (pin "18") (pinfunction "1_18") (pintype "passive"))
    )
    (net (code "18") (name "/ESP_EN") (class "Default")
      (node (ref "U1") (pin "49") (pinfunction "PA14_49") (pintype "bidirectional"))
      (node (ref "U2") (pin "3") (pinfunction "EN_3") (pintype "bidirectional"))
    )
    (net (code "19") (name "/ESP_IO0") (class "Default")
      (node (ref "U1") (pin "29") (pinfunction "PB10_29") (pintype "bidirectional"))
      (node (ref "U2") (pin "25") (pinfunction "IO0_25") (pintype "bidirectional"))
    )
    (net (code "20") (name "/ESP_MISO") (class "Default")
      (node (ref "R67") (pin "2") (pinfunction "2_2") (pintype "passive"))
      (node (ref "R68") (pin "2") (pinfunction "2_2") (pintype "passive"))
      (node (ref "U2") (pin "31") (pinfunction "IO19_31") (pintype "bidirectional"))
    )
    (net (code "21") (name "/ESP_MOSI") (class "Default")
      (node (ref "R69") (pin "2") (pinfunction "2_2") (pintype "passive"))
      (node (ref "R70") (pin "2") (pinfunction "2_2") (pintype "passive"))
      (node (ref "U2") (pin "37") (pinfunction "IO23_37") (pintype "bidirectional"))
    )
    (net (code "22") (name "/ESP_ON") (class "Default")
      (node (ref "Q9") (pin "1") (pinfunction "G_1") (pintype "passive"))
      (node (ref "R63") (pin "2") (pinfunction "2_2") (pintype "passive"))
    )
    (net (code "23") (name "/ESP_RX") (class "Default")
      (node (ref "U1") (pin "51") (pinfunction "PC10_51") (pintype "bidirectional"))
      (node (ref "U2") (pin "34") (pinfunction "RXD0_34") (pintype "bidirectional"))
    )
    (net (code "24") (name "/ESP_SCK") (class "Default")
      (node (ref "R66") (pin "2") (pinfunction "2_2") (pintype "passive"))
      (node (ref "U2") (pin "30") (pinfunction "IO18_30") (pintype "bidirectional"))
    )
    (net (code "25") (name "/ESP_TX") (class "Default")
      (node (ref "U1") (pin "52") (pinfunction "PC11_52") (pintype "bidirectional"))
      (node (ref "U2") (pin "35") (pinfunction "TXD0_35") (pintype "bidirectional"))
    )
    (net (code "26") (name "/ESP_VCC") (class "Default")
      (node (ref "Q9") (pin "3") (pinfunction "D_3") (pintype "passive"))
      (node (ref "U2") (pin "2") (pinfunction "3V3_2") (pintype "bidirectional"))
    )
    (net (code "27") (name "/F_MISO") (class "Default")
      (node (ref "U$4") (pin "17") (pinfunction "PC7/SPI_MISO/[TIM1_CH2]_17") (pintype "bidirectional"))
      (node (ref "U$5") (pin "2") (pinfunction "SO_2") (pintype "bidirectional"))
    )
    (net (code "28") (name "/F_MOSI") (class "Default")
      (node (ref "U$4") (pin "16") (pinfunction "PC6/SPI_MOSI/[TIM1_CH1]_16") (pintype "bidirectional"))
      (node (ref "U$5") (pin "5") (pinfunction "SI_5") (pintype "bidirectional"))
    )
    (net (code "29") (name "/F_NCS") (class "Default")
      (node (ref "U$4") (pin "10") (pinfunction "PA3/TIM2_CH3/[SPI_NSS]_10") (pintype "bidirectional"))
      (node (ref "U$5") (pin "1") (pinfunction "NCS_1") (pintype "input"))
    )
    (net (code "30") (name "/F_NHOLD") (class "Default")
      (node (ref "U$4") (pin "1") (pinfunction "PD4/UART1_CK/TIM2_CH1/BEEP_1") (pintype "bidirectional"))
      (node (ref "U$5") (pin "7") (pinfunction "NHOLD_7") (pintype "bidirectional"))
    )
    (net (code "31") (name "/F_SCK") (class "Default")
      (node (ref "U$4") (pin "15") (pinfunction "PC5/SPI_SCK/[TIM2_CH1]_15") (pintype "bidirectional"))
      (node (ref "U$5") (pin "6") (pinfunction "SCK_6") (pintype "input"))
    )
    (net (code "32") (name "/LCLK") (class "Default")
      (node (ref "U$10") (pin "2") (pinfunction "2_2") (pintype "passive"))
      (node (ref "U$7") (pin "11") (pinfunction "PA0_11") (pintype "passive"))
    )
    (net (code "33") (name "/LDAT") (class "Default")
      (node (ref "U$10") (pin "3") (pinfunction "3_3") (pintype "passive"))
      (node (ref "U$7") (pin "13") (pinfunction "PB0_13") (pintype "passive"))
    )
    (net (code "34") (name "/LED0") (class "Default")
      (node (ref "R2") (pin "2") (pinfunction "2_2") (pintype "passive"))
      (node (ref "U$2") (pin "2") (pinfunction "PC13_2") (pintype "bidirectional"))
    )
    (net (code "35") (name "/LED1") (class "Default")
      (node (ref "R5") (pin "2") (pinfunction "2_2") (pintype "passive"))
      (node (ref "U$2") (pin "3") (pinfunction "PC14/OSC32_IN_3") (pintype "bidirectional"))
    )
    (net (code "36") (name "/LED2") (class "Default")
      (node (ref "R9") (pin "2") (pinfunction "2_2") (pintype "passive"))
      (node (ref "U$2") (pin "4") (pinfunction "PC15/OSC32_OUT_4") (pintype "bidirectional"))
    )
    (net (code "37") (name "/MCO") (class "Default")
      (node (ref "R40") (pin "1") (pinfunction "1_1") (pintype "passive"))
      (node (ref "U1") (pin "41") (pinfunction "PA8_41") (pintype "bidirectional"))
    )
    (net (code "38") (name "/MCU_MISO") (class "Default")
      (node (ref "IC5") (pin "7") (pinfunction "7_7") (pintype "passive"))
      (node (ref "R59") (pin "1") (pinfunction "1_1") (pintype "passive"))
      (node (ref "R60") (pin "1") (pinfunction "1_1") (pintype "passive"))
      (node (ref "U$13") (pin "3") (pinfunction "PA6_3") (pintype "passive"))
      (node (ref "U$20") (pin "7") (pinfunction "PA6_7") (pintype "passive"))
    )
    (net (code "39") (name "/MCU_MOSI") (class "Default")
      (node (ref "IC5") (pin "10") (pinfunction "10_10") (pintype "passive"))
      (node (ref "R61") (pin "1") (pinfunction "1_1") (pintype "passive"))
      (node (ref "R62") (pin "1") (pinfunction "1_1") (pintype "passive"))
      (node (ref "U$13") (pin "1") (pinfunction "PA4_1") (pintype "passive"))
      (node (ref "U$20") (pin "10") (pinfunction "PA4_10") (pintype "passive"))
    )
    (net (code "40") (name "/MCU_PA0") (class "Default")
      (node (ref "IC5") (pin "11") (pinfunction "11_11") (pintype "passive"))
      (node (ref "R56") (pin "1") (pinfunction "1_1") (pintype "passive"))
      (node (ref "TP28") (pin "TP") (pinfunction "TP_TP") (pintype "input"))
      (node (ref "U$20") (pin "11") (pinfunction "PA0_11") (pintype "passive"))
    )
    (net (code "41") (name "/MCU_PA7") (class "Default")
      (node (ref "IC5") (pin "6") (pinfunction "6_6") (pintype "passive"))
      (node (ref "R57") (pin "1") (pinfunction "1_1") (pintype "passive"))
      (node (ref "TP29") (pin "TP") (pinfunction "TP_TP") (pintype "input"))
      (node (ref "U$20") (pin "6") (pinfunction "PA7_6") (pintype "passive"))
    )
    (net (code "42") (name "/MCU_SCK") (class "Default")
      (node (ref "IC5") (pin "9") (pinfunction "9_9") (pintype "passive"))
      (node (ref "R58") (pin "1") (pinfunction "1_1") (pintype "passive"))
      (node (ref "U$13") (pin "6") (pinfunction "PA3_6") (pintype "passive"))
      (node (ref "U$20") (pin "9") (pinfunction "PA3_9") (pintype "passive"))
    )
    (net (code "43") (name "/MISO") (class "Default")
      (node (ref "R59") (pin "2") (pinfunction "2_2") (pintype "passive"))
      (node (ref "R62") (pin "2") (pinfunction "2_2") (pintype "passive"))
      (node (ref "U$2") (pin "40") (pinfunction "PB4_40") (pintype "bidirectional"))
    )
    (net (code "44") (name "/MOSI") (class "Default")
      (node (ref "R60") (pin "2") (pinfunction "2_2") (pintype "passive"))
      (node (ref "R61") (pin "2") (pinfunction "2_2") (pintype "passive"))
      (node (ref "U$2") (pin "41") (pinfunction "PB5_41") (pintype "bidirectional"))
    )
    (net (code "45") (name "/N$2") (class "Default")
      (node (ref "C44") (pin "2") (pinfunction "2_2") (pintype "passive"))
      (node (ref "L10") (pin "P$1") (pinfunction "1_P$1") (pintype "passive"))
      (node (ref "Q10") (pin "3") (pinfunction "D_3") (pintype "passive"))
      (node (ref "U$15") (pin "4") (pinfunction "EN_4") (pintype "input"))
      (node (ref "U$15") (pin "5") (pinfunction "IN_5") (pintype "power_in"))
    )
    (net (code "46") (name "/N$8") (class "Default")
      (node (ref "C29") (pin "2") (pinfunction "2_2") (pintype "passive"))
      (node (ref "R36") (pin "1") (pinfunction "1_1") (pintype "passive"))
      (node (ref "U$4") (pin "4") (pinfunction "NRST_4") (pintype "input"))
      (node (ref "U$8") (pin "2") (pinfunction "2_2") (pintype "passive"))
    )
    (net (code "47") (name "/N$12") (class "Default")
      (node (ref "TP14") (pin "TP") (pinfunction "TP_TP") (pintype "input"))
      (node (ref "U$4") (pin "20") (pinfunction "PD3/AIN4/TIM2_CH2/ADC_ETR_20") (pintype "bidirectional"))
    )
    (net (code "48") (name "/N$48") (class "Default")
      (node (ref "C18") (pin "2") (pinfunction "2_2") (pintype "passive"))
      (node (ref "JP5") (pin "1") (pinfunction "1_1") (pintype "passive"))
      (node (ref "M2") (pin "3") (pinfunction "VOUT_3") (pintype "passive"))
    )
    (net (code "49") (name "/NBOOT0") (class "Default")
      (node (ref "BOOT2") (pin "1") (pinfunction "1_1") (pintype "passive"))
      (node (ref "R82") (pin "2") (pinfunction "2_2") (pintype "passive"))
      (node (ref "U$29") (pin "1") (pinfunction "BOOT0_1") (pintype "input"))
    )
    (net (code "50") (name "/NIRQ") (class "Default")
      (node (ref "U$25") (pin "IRQ") (pinfunction "IRQ_IRQ") (pintype "bidirectional"))
      (node (ref "U$29") (pin "7") (pinfunction "PA1_7") (pintype "bidirectional"))
    )
    (net (code "51") (name "/NLED0") (class "Default")
      (node (ref "R38") (pin "2") (pinfunction "2_2") (pintype "passive"))
      (node (ref "U1") (pin "46") (pinfunction "PA13_46") (pintype "bidirectional"))
    )
    (net (code "52") (name "/NLED1") (class "Default")
      (node (ref "R42") (pin "2") (pinfunction "2_2") (pintype "passive"))
      (node (ref "U1") (pin "35") (pinfunction "PB14_35") (pintype "bidirectional"))
    )
    (net (code "53") (name "/NLED2") (class "Default")
      (node (ref "R45") (pin "2") (pinfunction "2_2") (pintype "passive"))
      (node (ref "U1") (pin "36") (pinfunction "PB15_36") (pintype "bidirectional"))
    )
    (net (code "54") (name "/NNRST") (class "Default")
      (node (ref "R83") (pin "1") (pinfunction "1_1") (pintype "passive"))
      (node (ref "S3") (pin "P$1") (pinfunction "1_P$1") (pintype "passive"))
      (node (ref "U$29") (pin "4") (pinfunction "NRST_4") (pintype "input"))
    )
    (net (code "55") (name "/NOSC_IN") (class "Default")
      (node (ref "C81") (pin "2") (pinfunction "2_2") (pintype "passive"))
      (node (ref "Q11") (pin "2") (pinfunction "2_2") (pintype "passive"))
      (node (ref "U$29") (pin "2") (pinfunction "PF0/OSC_IN_2") (pintype "bidirectional"))
    )
    (net (code "56") (name "/NOSC_OUT") (class "Default")
      (node (ref "C82") (pin "2") (pinfunction "2_2") (pintype "passive"))
      (node (ref "Q11") (pin "1") (pinfunction "1_1") (pintype "passive"))
      (node (ref "U$29") (pin "3") (pinfunction "PF1/OSC_OUT_3") (pintype "bidirectional"))
    )
    (net (code "57") (name "/NRST") (class "Default")
      (node (ref "R52") (pin "1") (pinfunction "1_1") (pintype "passive"))
      (node (ref "S2") (pin "P$1") (pinfunction "1_P$1") (pintype "passive"))
      (node (ref "U$2") (pin "7") (pinfunction "NRST_7") (pintype "input"))
    )
    (net (code "58") (name "/NRSTO") (class "Default")
      (node (ref "U$25") (pin "RSTO") (pinfunction "RSTO_RSTO") (pintype "bidirectional"))
      (node (ref "U$29") (pin "6") (pinfunction "PA0_6") (pintype "bidirectional"))
    )
    (net (code "59") (name "/NSWCLK") (class "Default")
      (node (ref "U$29") (pin "20") (pinfunction "PA14_20") (pintype "bidirectional"))
      (node (ref "U$30") (pin "3") (pinfunction "3_3") (pintype "passive"))
    )
    (net (code "60") (name "/NSWDIO") (class "Default")
      (node (ref "U$29") (pin "19") (pinfunction "PA13_19") (pintype "bidirectional"))
      (node (ref "U$30") (pin "2") (pinfunction "2_2") (pintype "passive"))
    )
    (net (code "61") (name "/NUSBDM") (class "Default")
      (node (ref "R78") (pin "2") (pinfunction "2_2") (pintype "passive"))
      (node (ref "U$29") (pin "17") (pinfunction "PA9/PA11_17") (pintype "bidirectional"))
    )
    (net (code "62") (name "/NUSBDP") (class "Default")
      (node (ref "R79") (pin "2") (pinfunction "2_2") (pintype "passive"))
      (node (ref "R80") (pin "1") (pinfunction "1_1") (pintype "passive"))
      (node (ref "U$29") (pin "18") (pinfunction "PA10/PA12_18") (pintype "bidirectional"))
    )
    (net (code "63") (name "/N_MISO") (class "Default")
      (node (ref "U$25") (pin "MISO") (pinfunction "MISO_MISO") (pintype "bidirectional"))
      (node (ref "U$29") (pin "12") (pinfunction "PA6_12") (pintype "bidirectional"))
    )
    (net (code "64") (name "/N_MOSI") (class "Default")
      (node (ref "U$25") (pin "MOSI") (pinfunction "MOSI_MOSI") (pintype "bidirectional"))
      (node (ref "U$29") (pin "13") (pinfunction "PA7_13") (pintype "bidirectional"))
    )
    (net (code "65") (name "/N_RX") (class "Default")
      (node (ref "U$25") (pin "SDA/TX") (pinfunction "SDA/TX_SDA/TX") (pintype "bidirectional"))
      (node (ref "U$29") (pin "9") (pinfunction "PA3_9") (pintype "bidirectional"))
    )
    (net (code "66") (name "/N_SCK") (class "Default")
      (node (ref "U$25") (pin "SCK") (pinfunction "SCK_SCK") (pintype "bidirectional"))
      (node (ref "U$29") (pin "11") (pinfunction "PA5_11") (pintype "bidirectional"))
    )
    (net (code "67") (name "/N_SS") (class "Default")
      (node (ref "U$25") (pin "SS") (pinfunction "SS_SS") (pintype "bidirectional"))
      (node (ref "U$29") (pin "10") (pinfunction "PA4_10") (pintype "bidirectional"))
    )
    (net (code "68") (name "/N_TX") (class "Default")
      (node (ref "U$25") (pin "SCL/RX") (pinfunction "SCL/RX_SCL/RX") (pintype "bidirectional"))
      (node (ref "U$29") (pin "8") (pinfunction "PA2_8") (pintype "bidirectional"))
    )
    (net (code "69") (name "/OSC_IN") (class "Default")
      (node (ref "C31") (pin "2") (pinfunction "2_2") (pintype "passive"))
      (node (ref "Q6") (pin "2") (pinfunction "2_2") (pintype "passive"))
      (node (ref "U$2") (pin "5") (pinfunction "PF0/OSC_IN_5") (pintype "bidirectional"))
    )
    (net (code "70") (name "/OSC_OUT") (class "Default")
      (node (ref "C32") (pin "2") (pinfunction "2_2") (pintype "passive"))
      (node (ref "Q6") (pin "1") (pinfunction "1_1") (pintype "passive"))
      (node (ref "U$2") (pin "6") (pinfunction "PF1/OSC_OUT_6") (pintype "bidirectional"))
    )
    (net (code "71") (name "/PA0") (class "Default")
      (node (ref "U$19") (pin "6") (pinfunction "PA0_6") (pintype "bidirectional"))
      (node (ref "U$23") (pin "3") (pinfunction "3_3") (pintype "passive"))
    )
    (net (code "72") (name "/PA1") (class "Default")
      (node (ref "U$19") (pin "7") (pinfunction "PA1_7") (pintype "bidirectional"))
      (node (ref "U$23") (pin "2") (pinfunction "2_2") (pintype "passive"))
    )
    (net (code "73") (name "/PA2") (class "Default")
      (node (ref "U$19") (pin "8") (pinfunction "PA2_8") (pintype "bidirectional"))
      (node (ref "U$23") (pin "1") (pinfunction "1_1") (pintype "passive"))
    )
    (net (code "74") (name "/PA3") (class "Default")
      (node (ref "U$19") (pin "9") (pinfunction "PA3_9") (pintype "bidirectional"))
      (node (ref "U$21") (pin "8") (pinfunction "8_8") (pintype "passive"))
    )
    (net (code "75") (name "/PA3{slash}ADC3") (class "Default")
      (node (ref "U1") (pin "17") (pinfunction "PA3_17") (pintype "bidirectional"))
      (node (ref "X1") (pin "30") (pinfunction "1_30") (pintype "passive"))
    )
    (net (code "76") (name "/PA4") (class "Default")
      (node (ref "U$19") (pin "10") (pinfunction "PA4_10") (pintype "bidirectional"))
      (node (ref "U$21") (pin "7") (pinfunction "7_7") (pintype "passive"))
    )
    (net (code "77") (name "/PA4{slash}DAC1") (class "Default")
      (node (ref "U1") (pin "20") (pinfunction "PA4_20") (pintype "bidirectional"))
      (node (ref "X1") (pin "32") (pinfunction "1_32") (pintype "passive"))
    )
    (net (code "78") (name "/PA5") (class "Default")
      (node (ref "U$19") (pin "11") (pinfunction "PA5_11") (pintype "bidirectional"))
      (node (ref "U$21") (pin "6") (pinfunction "6_6") (pintype "passive"))
    )
    (net (code "79") (name "/PA5{slash}DAC2") (class "Default")
      (node (ref "U1") (pin "21") (pinfunction "PA5_21") (pintype "bidirectional"))
      (node (ref "X1") (pin "34") (pinfunction "1_34") (pintype "passive"))
    )
    (net (code "80") (name "/PA6") (class "Default")
      (node (ref "U$19") (pin "12") (pinfunction "PA6_12") (pintype "bidirectional"))
      (node (ref "U$21") (pin "5") (pinfunction "5_5") (pintype "passive"))
    )
    (net (code "81") (name "/PA7") (class "Default")
      (node (ref "U$19") (pin "13") (pinfunction "PA7_13") (pintype "bidirectional"))
      (node (ref "U$21") (pin "4") (pinfunction "4_4") (pintype "passive"))
    )
    (net (code "82") (name "/PA9") (class "Default")
      (node (ref "P2") (pin "2") (pinfunction "2_2") (pintype "passive"))
      (node (ref "U$19") (pin "17") (pinfunction "PA9_17") (pintype "bidirectional"))
    )
    (net (code "83") (name "/PA10") (class "Default")
      (node (ref "P2") (pin "1") (pinfunction "1_1") (pintype "passive"))
      (node (ref "U$19") (pin "18") (pinfunction "PA10_18") (pintype "bidirectional"))
    )
    (net (code "84") (name "/PA13") (class "Default")
      (node (ref "U$19") (pin "19") (pinfunction "PA13/SWDIO_19") (pintype "bidirectional"))
      (node (ref "U$21") (pin "2") (pinfunction "2_2") (pintype "passive"))
    )
    (net (code "85") (name "/PA14") (class "Default")
      (node (ref "U$19") (pin "20") (pinfunction "PA14/SWCLK_20") (pintype "bidirectional"))
      (node (ref "U$21") (pin "1") (pinfunction "1_1") (pintype "passive"))
    )
    (net (code "86") (name "/PA15{slash}NSS") (class "Default")
      (node (ref "R65") (pin "1") (pinfunction "1_1") (pintype "passive"))
      (node (ref "U1") (pin "50") (pinfunction "PA15_50") (pintype "bidirectional"))
    )
    (net (code "87") (name "/PB1") (class "Default")
      (node (ref "U$19") (pin "14") (pinfunction "PB1_14") (pintype "bidirectional"))
      (node (ref "U$21") (pin "3") (pinfunction "3_3") (pintype "passive"))
    )
    (net (code "88") (name "/PB6{slash}UART1_TX") (class "Default")
      (node (ref "U1") (pin "58") (pinfunction "PB6_58") (pintype "bidirectional"))
      (node (ref "X1") (pin "12") (pinfunction "1_12") (pintype "passive"))
    )
    (net (code "89") (name "/PB7{slash}UART1_RX") (class "Default")
      (node (ref "U1") (pin "59") (pinfunction "PB7_59") (pintype "bidirectional"))
      (node (ref "X1") (pin "13") (pinfunction "1_13") (pintype "passive"))
    )
    (net (code "90") (name "/PEDAL") (class "Default")
      (node (ref "JP11") (pin "2") (pinfunction "2_2") (pintype "passive"))
      (node (ref "R81") (pin "1") (pinfunction "1_1") (pintype "passive"))
      (node (ref "U4") (pin "5") (pinfunction "PB2_5") (pintype "bidirectional"))
    )
    (net (code "91") (name "/PF0") (class "Default")
      (node (ref "U$19") (pin "2") (pinfunction "PF0/OSC_IN_2") (pintype "bidirectional"))
      (node (ref "U$23") (pin "6") (pinfunction "6_6") (pintype "passive"))
    )
    (net (code "92") (name "/PF1") (class "Default")
      (node (ref "U$19") (pin "3") (pinfunction "PF1/OSC_OUT_3") (pintype "bidirectional"))
      (node (ref "U$23") (pin "5") (pinfunction "5_5") (pintype "passive"))
    )
    (net (code "93") (name "/PHY_LED0") (class "Default")
      (node (ref "IC1") (pin "3") (pinfunction "LED1/REGOFF_3") (pintype "bidirectional"))
      (node (ref "T1") (pin "10") (pinfunction "K_10") (pintype "passive"))
    )
    (net (code "94") (name "/PHY_LED1") (class "Default")
      (node (ref "IC1") (pin "2") (pinfunction "LED2/NINTSEL_2") (pintype "bidirectional"))
      (node (ref "T1") (pin "11") (pinfunction "K_11") (pintype "passive"))
    )
    (net (code "95") (name "/PWM1") (class "Default")
      (node (ref "R50") (pin "2") (pinfunction "2_2") (pintype "passive"))
      (node (ref "R51") (pin "2") (pinfunction "2_2") (pintype "passive"))
      (node (ref "U$4") (pin "13") (pinfunction "PC3/TIM1_CH3/[TIM1_CH1N]_13") (pintype "bidirectional"))
    )
    (net (code "96") (name "/PWM2") (class "Default")
      (node (ref "R49") (pin "2") (pinfunction "2_2") (pintype "passive"))
      (node (ref "U$4") (pin "14") (pinfunction "PC4/TIM1_CH4/CLK_CCO/AIN2/[TIM1_CH2N]_14") (pintype "bidirectional"))
    )
    (net (code "97") (name "/PWRON") (class "Default")
      (node (ref "Q10") (pin "1") (pinfunction "G_1") (pintype "passive"))
      (node (ref "R64") (pin "1") (pinfunction "1_1") (pintype "passive"))
      (node (ref "U$2") (pin "27") (pinfunction "PB14_27") (pintype "bidirectional"))
    )
    (net (code "98") (name "/REG33IN") (class "Default")
      (node (ref "C51") (pin "2") (pinfunction "2_2") (pintype "passive"))
      (node (ref "D1") (pin "1") (pinfunction "C_1") (pintype "passive"))
      (node (ref "IC4") (pin "5") (pinfunction "EN_5") (pintype "bidirectional"))
      (node (ref "IC4") (pin "7") (pinfunction "AVIN_7") (pintype "power_in"))
      (node (ref "IC4") (pin "8") (pinfunction "PVIN_8") (pintype "power_in"))
      (node (ref "J3") (pin "3") (pinfunction "3_3") (pintype "passive"))
      (node (ref "X1") (pin "1") (pinfunction "1_1") (pintype "passive"))
    )
    (net (code "99") (name "/RMII_CRS_DV") (class "Default")
      (node (ref "IC1") (pin "11") (pinfunction "CRS_DV/MODE2_11") (pintype "bidirectional"))
      (node (ref "U1") (pin "23") (pinfunction "PA7_23") (pintype "bidirectional"))
    )
    (net (code "100") (name "/RMII_MDC") (class "Default")
      (node (ref "IC1") (pin "13") (pinfunction "MDC_13") (pintype "bidirectional"))
      (node (ref "R8") (pin "1") (pinfunction "1_1") (pintype "passive"))
      (node (ref "U1") (pin "9") (pinfunction "PC1_9") (pintype "bidirectional"))
    )
    (net (code "101") (name "/RMII_MDIO") (class "Default")
      (node (ref "IC1") (pin "12") (pinfunction "MDIO_12") (pintype "bidirectional"))
      (node (ref "R10") (pin "1") (pinfunction "1_1") (pintype "passive"))
      (node (ref "U1") (pin "16") (pinfunction "PA2_16") (pintype "bidirectional"))
    )
    (net (code "102") (name "/RMII_NRST") (class "Default")
      (node (ref "IC1") (pin "15") (pinfunction "NRST_15") (pintype "bidirectional"))
      (node (ref "R4") (pin "1") (pinfunction "1_1") (pintype "passive"))
      (node (ref "U1") (pin "22") (pinfunction "PA6_22") (pintype "bidirectional"))
    )
    (net (code "103") (name "/RMII_REF_CLK") (class "Default")
      (node (ref "IC1") (pin "14") (pinfunction "NINT/REFCLK0_14") (pintype "bidirectional"))
      (node (ref "U1") (pin "15") (pinfunction "PA1_15") (pintype "bidirectional"))
    )
    (net (code "104") (name "/RMII_RXD0") (class "Default")
      (node (ref "IC1") (pin "8") (pinfunction "RXD0/MODE0_8") (pintype "bidirectional"))
      (node (ref "U1") (pin "24") (pinfunction "PC4_24") (pintype "bidirectional"))
    )
    (net (code "105") (name "/RMII_RXD1") (class "Default")
      (node (ref "IC1") (pin "7") (pinfunction "RXD1/MODE1_7") (pintype "bidirectional"))
      (node (ref "U1") (pin "25") (pinfunction "PC5_25") (pintype "bidirectional"))
    )
    (net (code "106") (name "/RMII_TXD0") (class "Default")
      (node (ref "IC1") (pin "17") (pinfunction "TXD0_17") (pintype "bidirectional"))
      (node (ref "U1") (pin "33") (pinfunction "PB12_33") (pintype "bidirectional"))
    )
    (net (code "107") (name "/RMII_TXD1") (class "Default")
      (node (ref "IC1") (pin "18") (pinfunction "TXD1_18") (pintype "bidirectional"))
      (node (ref "U1") (pin "34") (pinfunction "PB13_34") (pintype "bidirectional"))
    )
    (net (code "108") (name "/RMII_TX_EN") (class "Default")
      (node (ref "IC1") (pin "16") (pinfunction "TXEN_16") (pintype "bidirectional"))
      (node (ref "U1") (pin "30") (pinfunction "PB11_30") (pintype "bidirectional"))
    )
    (net (code "109") (name "/RX") (class "Default")
      (node (ref "JP4") (pin "2") (pinfunction "2_2") (pintype "passive"))
      (node (ref "U$4") (pin "3") (pinfunction "PD6/UART1_RX/AIN6_3") (pintype "bidirectional"))
    )
    (net (code "110") (name "/RXM1") (class "Default")
      (node (ref "IC1") (pin "20") (pinfunction "TXN_20") (pintype "bidirectional"))
      (node (ref "R41") (pin "1") (pinfunction "1_1") (pintype "passive"))
      (node (ref "T1") (pin "2") (pinfunction "2_2") (pintype "bidirectional"))
    )
    (net (code "111") (name "/RXP1") (class "Default")
      (node (ref "IC1") (pin "21") (pinfunction "TXP_21") (pintype "bidirectional"))
      (node (ref "R39") (pin "1") (pinfunction "1_1") (pintype "passive"))
      (node (ref "T1") (pin "1") (pinfunction "1_1") (pintype "bidirectional"))
    )
    (net (code "112") (name "/S0") (class "Default")
      (node (ref "U$16") (pin "1") (pinfunction "1_1") (pintype "passive"))
      (node (ref "X2") (pin "6") (pinfunction "1_6") (pintype "passive"))
    )
    (net (code "113") (name "/S1") (class "Default")
      (node (ref "U$18") (pin "2") (pinfunction "2_2") (pintype "passive"))
      (node (ref "X2") (pin "7") (pinfunction "1_7") (pintype "passive"))
    )
    (net (code "114") (name "/S2") (class "Default")
      (node (ref "U$17") (pin "2") (pinfunction "2_2") (pintype "passive"))
      (node (ref "X2") (pin "8") (pinfunction "1_8") (pintype "passive"))
    )
    (net (code "115") (name "/S3") (class "Default")
      (node (ref "U$16") (pin "2") (pinfunction "2_2") (pintype "passive"))
      (node (ref "X2") (pin "9") (pinfunction "1_9") (pintype "passive"))
    )
    (net (code "116") (name "/S4") (class "Default")
      (node (ref "U$18") (pin "3") (pinfunction "3_3") (pintype "passive"))
      (node (ref "X2") (pin "10") (pinfunction "1_10") (pintype "passive"))
    )
    (net (code "117") (name "/S5") (class "Default")
      (node (ref "U$17") (pin "3") (pinfunction "3_3") (pintype "passive"))
      (node (ref "X2") (pin "12") (pinfunction "1_12") (pintype "passive"))
    )
    (net (code "118") (name "/S6") (class "Default")
      (node (ref "U$16") (pin "3") (pinfunction "3_3") (pintype "passive"))
      (node (ref "X2") (pin "13") (pinfunction "1_13") (pintype "passive"))
    )
    (net (code "119") (name "/S7") (class "Default")
      (node (ref "U$18") (pin "4") (pinfunction "4_4") (pintype "passive"))
      (node (ref "X2") (pin "14") (pinfunction "1_14") (pintype "passive"))
    )
    (net (code "120") (name "/S8") (class "Default")
      (node (ref "U$17") (pin "4") (pinfunction "4_4") (pintype "passive"))
      (node (ref "X2") (pin "15") (pinfunction "1_15") (pintype "passive"))
    )
    (net (code "121") (name "/S9") (class "Default")
      (node (ref "U$16") (pin "4") (pinfunction "4_4") (pintype "passive"))
      (node (ref "X2") (pin "16") (pinfunction "1_16") (pintype "passive"))
    )
    (net (code "122") (name "/S10") (class "Default")
      (node (ref "U$18") (pin "5") (pinfunction "5_5") (pintype "passive"))
      (node (ref "X2") (pin "17") (pinfunction "1_17") (pintype "passive"))
    )
    (net (code "123") (name "/S11") (class "Default")
      (node (ref "U$17") (pin "5") (pinfunction "5_5") (pintype "passive"))
      (node (ref "X2") (pin "18") (pinfunction "1_18") (pintype "passive"))
    )
    (net (code "124") (name "/S12") (class "Default")
      (node (ref "U$16") (pin "5") (pinfunction "5_5") (pintype "passive"))
      (node (ref "X2") (pin "19") (pinfunction "1_19") (pintype "passive"))
    )
    (net (code "125") (name "/S13") (class "Default")
      (node (ref "U$18") (pin "6") (pinfunction "6_6") (pintype "passive"))
      (node (ref "X2") (pin "20") (pinfunction "1_20") (pintype "passive"))
    )
    (net (code "126") (name "/S14") (class "Default")
      (node (ref "U$17") (pin "6") (pinfunction "6_6") (pintype "passive"))
      (node (ref "X2") (pin "21") (pinfunction "1_21") (pintype "passive"))
    )
    (net (code "127") (name "/S15") (class "Default")
      (node (ref "U$16") (pin "6") (pinfunction "6_6") (pintype "passive"))
      (node (ref "X2") (pin "22") (pinfunction "1_22") (pintype "passive"))
    )
    (net (code "128") (name "/S16") (class "Default")
      (node (ref "U$18") (pin "7") (pinfunction "7_7") (pintype "passive"))
      (node (ref "X2") (pin "23") (pinfunction "1_23") (pintype "passive"))
    )
    (net (code "129") (name "/S17") (class "Default")
      (node (ref "U$17") (pin "7") (pinfunction "7_7") (pintype "passive"))
      (node (ref "X2") (pin "24") (pinfunction "1_24") (pintype "passive"))
    )
    (net (code "130") (name "/S18") (class "Default")
      (node (ref "U$16") (pin "7") (pinfunction "7_7") (pintype "passive"))
      (node (ref "X2") (pin "25") (pinfunction "1_25") (pintype "passive"))
    )
    (net (code "131") (name "/S19") (class "Default")
      (node (ref "U$18") (pin "8") (pinfunction "8_8") (pintype "passive"))
      (node (ref "X2") (pin "26") (pinfunction "1_26") (pintype "passive"))
    )
    (net (code "132") (name "/S20") (class "Default")
      (node (ref "U$17") (pin "8") (pinfunction "8_8") (pintype "passive"))
      (node (ref "X2") (pin "27") (pinfunction "1_27") (pintype "passive"))
    )
    (net (code "133") (name "/S21") (class "Default")
      (node (ref "U$16") (pin "8") (pinfunction "8_8") (pintype "passive"))
      (node (ref "X2") (pin "28") (pinfunction "1_28") (pintype "passive"))
    )
    (net (code "134") (name "/S22") (class "Default")
      (node (ref "U$18") (pin "9") (pinfunction "9_9") (pintype "passive"))
      (node (ref "X2") (pin "30") (pinfunction "1_30") (pintype "passive"))
    )
    (net (code "135") (name "/S23") (class "Default")
      (node (ref "U$17") (pin "9") (pinfunction "9_9") (pintype "passive"))
      (node (ref "X2") (pin "32") (pinfunction "1_32") (pintype "passive"))
    )
    (net (code "136") (name "/S24") (class "Default")
      (node (ref "U$16") (pin "9") (pinfunction "9_9") (pintype "passive"))
      (node (ref "X2") (pin "34") (pinfunction "1_34") (pintype "passive"))
    )
    (net (code "137") (name "/S25") (class "Default")
      (node (ref "U$18") (pin "10") (pinfunction "10_10") (pintype "passive"))
      (node (ref "X2") (pin "36") (pinfunction "1_36") (pintype "passive"))
    )
    (net (code "138") (name "/S26") (class "Default")
      (node (ref "U$17") (pin "10") (pinfunction "10_10") (pintype "passive"))
      (node (ref "X2") (pin "38") (pinfunction "1_38") (pintype "passive"))
    )
    (net (code "139") (name "/S27") (class "Default")
      (node (ref "U$16") (pin "10") (pinfunction "10_10") (pintype "passive"))
      (node (ref "X2") (pin "39") (pinfunction "1_39") (pintype "passive"))
    )
    (net (code "140") (name "/SA") (class "Default")
      (node (ref "R13") (pin "2") (pinfunction "2_2") (pintype "passive"))
      (node (ref "U$3") (pin "11") (pinfunction "A_11") (pintype "passive"))
    )
    (net (code "141") (name "/SB") (class "Default")
      (node (ref "R15") (pin "2") (pinfunction "2_2") (pintype "passive"))
      (node (ref "U$3") (pin "7") (pinfunction "B_7") (pintype "passive"))
    )
    (net (code "142") (name "/SC") (class "Default")
      (node (ref "R16") (pin "2") (pinfunction "2_2") (pintype "passive"))
      (node (ref "U$3") (pin "4") (pinfunction "C_4") (pintype "passive"))
    )
    (net (code "143") (name "/SCK") (class "Default")
      (node (ref "R58") (pin "2") (pinfunction "2_2") (pintype "passive"))
      (node (ref "U$2") (pin "39") (pinfunction "PB3_39") (pintype "bidirectional"))
    )
    (net (code "144") (name "/SCL") (class "Default")
      (node (ref "TP15") (pin "TP") (pinfunction "TP_TP") (pintype "input"))
      (node (ref "U$4") (pin "12") (pinfunction "PB4/I2C_SCL/ADC_ETR_12") (pintype "open_collector"))
    )
    (net (code "145") (name "/SD") (class "Default")
      (node (ref "R17") (pin "2") (pinfunction "2_2") (pintype "passive"))
      (node (ref "U$3") (pin "2") (pinfunction "D_2") (pintype "passive"))
    )
    (net (code "146") (name "/SDA") (class "Default")
      (node (ref "TP16") (pin "TP") (pinfunction "TP_TP") (pintype "input"))
      (node (ref "U$4") (pin "11") (pinfunction "PB5/I2C_SDA/[TIM1_BKIN]_11") (pintype "open_collector"))
    )
    (net (code "147") (name "/SDP") (class "Default")
      (node (ref "R21") (pin "2") (pinfunction "2_2") (pintype "passive"))
      (node (ref "U$3") (pin "3") (pinfunction "DP_3") (pintype "passive"))
    )
    (net (code "148") (name "/SE") (class "Default")
      (node (ref "R18") (pin "2") (pinfunction "2_2") (pintype "passive"))
      (node (ref "U$3") (pin "1") (pinfunction "E_1") (pintype "passive"))
    )
    (net (code "149") (name "/SEG_A") (class "Default")
      (node (ref "R13") (pin "1") (pinfunction "1_1") (pintype "passive"))
      (node (ref "U$7") (pin "9") (pinfunction "PA3_9") (pintype "passive"))
    )
    (net (code "150") (name "/SEG_B") (class "Default")
      (node (ref "R15") (pin "1") (pinfunction "1_1") (pintype "passive"))
      (node (ref "U$7") (pin "14") (pinfunction "PB1_14") (pintype "passive"))
    )
    (net (code "151") (name "/SEG_C") (class "Default")
      (node (ref "R16") (pin "1") (pinfunction "1_1") (pintype "passive"))
      (node (ref "U$7") (pin "2") (pinfunction "PB5_2") (pintype "passive"))
    )
    (net (code "152") (name "/SEG_D") (class "Default")
      (node (ref "R17") (pin "1") (pinfunction "1_1") (pintype "passive"))
      (node (ref "U$7") (pin "15") (pinfunction "PB2_15") (pintype "passive"))
    )
    (net (code "153") (name "/SEG_DP") (class "Default")
      (node (ref "R21") (pin "1") (pinfunction "1_1") (pintype "passive"))
      (node (ref "U$7") (pin "16") (pinfunction "PB3_16") (pintype "passive"))
    )
    (net (code "154") (name "/SEG_E") (class "Default")
      (node (ref "R18") (pin "1") (pinfunction "1_1") (pintype "passive"))
      (node (ref "U$7") (pin "10") (pinfunction "PA4_10") (pintype "passive"))
    )
    (net (code "155") (name "/SEG_F") (class "Default")
      (node (ref "R19") (pin "1") (pinfunction "1_1") (pintype "passive"))
      (node (ref "U$7") (pin "8") (pinfunction "PA5_8") (pintype "passive"))
    )
    (net (code "156") (name "/SEG_G") (class "Default")
      (node (ref "R20") (pin "1") (pinfunction "1_1") (pintype "passive"))
      (node (ref "U$7") (pin "1") (pinfunction "PB4_1") (pintype "passive"))
    )
    (net (code "157") (name "/SEL_A0") (class "Default")
      (node (ref "IC7") (pin "11") (pinfunction "A_11") (pintype "input"))
      (node (ref "U4") (pin "10") (pinfunction "PA3_10") (pintype "bidirectional"))
    )
    (net (code "158") (name "/SEL_A1") (class "Default")
      (node (ref "IC6") (pin "11") (pinfunction "A_11") (pintype "input"))
      (node (ref "U4") (pin "13") (pinfunction "PA0_13") (pintype "bidirectional"))
    )
    (net (code "159") (name "/SEL_B0") (class "Default")
      (node (ref "IC7") (pin "10") (pinfunction "B_10") (pintype "input"))
      (node (ref "U4") (pin "6") (pinfunction "PA7_6") (pintype "bidirectional"))
    )
    (net (code "160") (name "/SEL_B1") (class "Default")
      (node (ref "IC6") (pin "10") (pinfunction "B_10") (pintype "input"))
      (node (ref "U4") (pin "12") (pinfunction "PA1_12") (pintype "bidirectional"))
    )
    (net (code "161") (name "/SEL_C0") (class "Default")
      (node (ref "IC7") (pin "9") (pinfunction "C_9") (pintype "input"))
      (node (ref "U4") (pin "2") (pinfunction "PB0_2") (pintype "bidirectional"))
    )
    (net (code "162") (name "/SEL_C1") (class "Default")
      (node (ref "IC6") (pin "9") (pinfunction "C_9") (pintype "input"))
      (node (ref "U4") (pin "11") (pinfunction "PA2_11") (pintype "bidirectional"))
    )
    (net (code "163") (name "/SEL_INH") (class "Default")
      (node (ref "IC6") (pin "6") (pinfunction "INH_6") (pintype "input"))
      (node (ref "IC7") (pin "6") (pinfunction "INH_6") (pintype "input"))
      (node (ref "U4") (pin "3") (pinfunction "PB1_3") (pintype "bidirectional"))
    )
    (net (code "164") (name "/SF") (class "Default")
      (node (ref "R19") (pin "2") (pinfunction "2_2") (pintype "passive"))
      (node (ref "U$3") (pin "10") (pinfunction "F_10") (pintype "passive"))
    )
    (net (code "165") (name "/SG") (class "Default")
      (node (ref "R20") (pin "2") (pinfunction "2_2") (pintype "passive"))
      (node (ref "U$3") (pin "5") (pinfunction "G_5") (pintype "passive"))
    )
    (net (code "166") (name "/SHIELD") (class "Default")
      (node (ref "T1") (pin "8") (pinfunction "8_8") (pintype "bidirectional"))
      (node (ref "T1") (pin "Z1") (pinfunction "SHIELD_Z1") (pintype "passive"))
      (node (ref "T1") (pin "Z2") (pinfunction "SHIELD_Z2") (pintype "passive"))
    )
    (net (code "167") (name "/STM_PA0") (class "Default")
      (node (ref "R56") (pin "2") (pinfunction "2_2") (pintype "passive"))
      (node (ref "U$2") (pin "42") (pinfunction "PB6_42") (pintype "bidirectional"))
    )
    (net (code "168") (name "/STM_PA7") (class "Default")
      (node (ref "R57") (pin "2") (pinfunction "2_2") (pintype "passive"))
      (node (ref "U$2") (pin "43") (pinfunction "PB7_43") (pintype "bidirectional"))
    )
    (net (code "169") (name "/SW") (class "Default")
      (node (ref "JP2") (pin "2") (pinfunction "2_2") (pintype "passive"))
      (node (ref "R6") (pin "1") (pinfunction "1_1") (pintype "passive"))
      (node (ref "U$4") (pin "19") (pinfunction "PD2/AIN3/[TIM2_CH3]_19") (pintype "bidirectional"))
    )
    (net (code "170") (name "/SWCLK") (class "Default")
      (node (ref "U$1") (pin "3") (pinfunction "3_3") (pintype "passive"))
      (node (ref "U$2") (pin "37") (pinfunction "PA14_37") (pintype "bidirectional"))
    )
    (net (code "171") (name "/SWDIO") (class "Default")
      (node (ref "U$1") (pin "2") (pinfunction "2_2") (pintype "passive"))
      (node (ref "U$2") (pin "34") (pinfunction "PA13_34") (pintype "bidirectional"))
    )
    (net (code "172") (name "/SWIM") (class "Default")
      (node (ref "U$4") (pin "18") (pinfunction "PD1/SWIM_18") (pintype "bidirectional"))
      (node (ref "U$8") (pin "3") (pinfunction "3_3") (pintype "passive"))
    )
    (net (code "173") (name "/S_FB") (class "Default")
      (node (ref "R71") (pin "1") (pinfunction "1_1") (pintype "passive"))
      (node (ref "R72") (pin "2") (pinfunction "2_2") (pintype "passive"))
      (node (ref "U$14") (pin "3") (pinfunction "FB_3") (pintype "passive"))
    )
    (net (code "174") (name "/S_VIN") (class "Default")
      (node (ref "C42") (pin "2") (pinfunction "2_2") (pintype "passive"))
      (node (ref "JP7") (pin "2") (pinfunction "2_2") (pintype "passive"))
      (node (ref "L9") (pin "1") (pinfunction "1_1") (pintype "passive"))
      (node (ref "U$14") (pin "4") (pinfunction "SHDN_4") (pintype "input"))
      (node (ref "U$14") (pin "6") (pinfunction "VIN_6") (pintype "power_in"))
    )
    (net (code "175") (name "/S_VOUT") (class "Default")
      (node (ref "C54") (pin "2") (pinfunction "2_2") (pintype "passive"))
      (node (ref "C55") (pin "2") (pinfunction "2_2") (pintype "passive"))
      (node (ref "JP8") (pin "1") (pinfunction "1_1") (pintype "passive"))
      (node (ref "R71") (pin "2") (pinfunction "2_2") (pintype "passive"))
      (node (ref "U$14") (pin "5") (pinfunction "VOUT_5") (pintype "passive"))
    )
    (net (code "176") (name "/TX") (class "Default")
      (node (ref "JP4") (pin "3") (pinfunction "3_3") (pintype "passive"))
      (node (ref "U$4") (pin "2") (pinfunction "PD5/UART1_TX/AIN5_2") (pintype "bidirectional"))
    )
    (net (code "177") (name "/TXM1") (class "Default")
      (node (ref "IC1") (pin "22") (pinfunction "RXN_22") (pintype "bidirectional"))
      (node (ref "R46") (pin "1") (pinfunction "1_1") (pintype "passive"))
      (node (ref "T1") (pin "6") (pinfunction "6_6") (pintype "bidirectional"))
    )
    (net (code "178") (name "/TXP1") (class "Default")
      (node (ref "IC1") (pin "23") (pinfunction "RXP_23") (pintype "bidirectional"))
      (node (ref "R44") (pin "1") (pinfunction "1_1") (pintype "passive"))
      (node (ref "T1") (pin "3") (pinfunction "3_3") (pintype "bidirectional"))
    )
    (net (code "179") (name "/UART1RX") (class "Default")
      (node (ref "U1") (pin "43") (pinfunction "PA10_43") (pintype "bidirectional"))
      (node (ref "X1") (pin "19") (pinfunction "1_19") (pintype "passive"))
    )
    (net (code "180") (name "/UART1TX") (class "Default")
      (node (ref "U1") (pin "42") (pinfunction "PA9_42") (pintype "bidirectional"))
      (node (ref "X1") (pin "20") (pinfunction "1_20") (pintype "passive"))
    )
    (net (code "181") (name "/UART_RX") (class "Default")
      (node (ref "P1") (pin "2") (pinfunction "2_2") (pintype "passive"))
      (node (ref "U$2") (pin "31") (pinfunction "PA10_31") (pintype "bidirectional"))
    )
    (net (code "182") (name "/UART_TX") (class "Default")
      (node (ref "P1") (pin "3") (pinfunction "3_3") (pintype "passive"))
      (node (ref "U$2") (pin "30") (pinfunction "PA9_30") (pintype "bidirectional"))
    )
    (net (code "183") (name "/USBDM") (class "Default")
      (node (ref "R47") (pin "2") (pinfunction "2_2") (pintype "passive"))
      (node (ref "U$2") (pin "32") (pinfunction "PA11_32") (pintype "bidirectional"))
    )
    (net (code "184") (name "/USBDP") (class "Default")
      (node (ref "R48") (pin "2") (pinfunction "2_2") (pintype "passive"))
      (node (ref "R53") (pin "1") (pinfunction "1_1") (pintype "passive"))
      (node (ref "U$2") (pin "33") (pinfunction "PA12_33") (pintype "bidirectional"))
    )
    (net (code "185") (name "/VCC3") (class "Default")
      (node (ref "C71") (pin "2") (pinfunction "2_2") (pintype "passive"))
      (node (ref "C74") (pin "2") (pinfunction "2_2") (pintype "passive"))
      (node (ref "IC8") (pin "5") (pinfunction "VCC_5") (pintype "power_in"))
      (node (ref "IC9") (pin "5") (pinfunction "VOUT_5") (pintype "power_in"))
      (node (ref "R77") (pin "2") (pinfunction "2_2") (pintype "passive"))
      (node (ref "U$26") (pin "10") (pinfunction "10_10") (pintype "passive"))
      (node (ref "U$26") (pin "9") (pinfunction "9_9") (pintype "passive"))
    )
    (net (code "186") (name "/VCCI") (class "Default")
      (node (ref "C67") (pin "2") (pinfunction "2_2") (pintype "passive"))
      (node (ref "IC9") (pin "1") (pinfunction "VIN_1") (pintype "power_in"))
      (node (ref "IC9") (pin "3") (pinfunction "EN_3") (pintype "input"))
      (node (ref "R77") (pin "1") (pinfunction "1_1") (pintype "passive"))
      (node (ref "U$27") (pin "10") (pinfunction "10_10") (pintype "passive"))
      (node (ref "U$27") (pin "9") (pinfunction "9_9") (pintype "passive"))
    )
    (net (code "187") (name "/VDDA") (class "Default")
      (node (ref "C56") (pin "1") (pinfunction "1_1") (pintype "passive"))
      (node (ref "L12") (pin "2") (pinfunction "2_2") (pintype "passive"))
      (node (ref "U$2") (pin "9") (pinfunction "VDDA_9") (pintype "power_in"))
    )
    (net (code "188") (name "/VDD_OUT") (class "Default")
      (node (ref "C25") (pin "1") (pinfunction "1_1") (pintype "passive"))
      (node (ref "C53") (pin "1") (pinfunction "1_1") (pintype "passive"))
      (node (ref "IC2") (pin "1") (pinfunction "OUT_1") (pintype "output"))
      (node (ref "IC5") (pin "5") (pinfunction "5_5") (pintype "passive"))
      (node (ref "R26") (pin "1") (pinfunction "1_1") (pintype "passive"))
      (node (ref "R33") (pin "2") (pinfunction "2_2") (pintype "passive"))
      (node (ref "U$13") (pin "5") (pinfunction "VCC_5") (pintype "power_in"))
      (node (ref "U$20") (pin "5") (pinfunction "VCC_5") (pintype "power_in"))
      (node (ref "VDD") (pin "TP") (pinfunction "TP_TP") (pintype "input"))
    )
    (net (code "189") (name "/VDD_PWM") (class "Default")
      (node (ref "IC2") (pin "3") (pinfunction "+IN_3") (pintype "input"))
      (node (ref "R23") (pin "2") (pinfunction "2_2") (pintype "passive"))
      (node (ref "U$2") (pin "15") (pinfunction "PA5_15") (pintype "bidirectional"))
    )
    (net (code "190") (name "/VDD_SENS") (class "Default")
      (node (ref "R33") (pin "1") (pinfunction "1_1") (pintype "passive"))
      (node (ref "R34") (pin "2") (pinfunction "2_2") (pintype "passive"))
      (node (ref "U$2") (pin "19") (pinfunction "PB1_19") (pintype "bidirectional"))
    )
    (net (code "191") (name "/VNEG_PWM") (class "Default")
      (node (ref "C63") (pin "1") (pinfunction "1_1") (pintype "passive"))
      (node (ref "U$2") (pin "13") (pinfunction "PA3_13") (pintype "bidirectional"))
    )
    (net (code "192") (name "/VPP_OUT") (class "Default")
      (node (ref "C26") (pin "1") (pinfunction "1_1") (pintype "passive"))
      (node (ref "C60") (pin "1") (pinfunction "1_1") (pintype "passive"))
      (node (ref "IC2") (pin "7") (pinfunction "OUT_7") (pintype "output"))
      (node (ref "IC5") (pin "8") (pinfunction "8_8") (pintype "passive"))
      (node (ref "R28") (pin "1") (pinfunction "1_1") (pintype "passive"))
      (node (ref "R31") (pin "2") (pinfunction "2_2") (pintype "passive"))
      (node (ref "U$13") (pin "4") (pinfunction "PA5_4") (pintype "passive"))
      (node (ref "U$20") (pin "8") (pinfunction "PA5_8") (pintype "passive"))
      (node (ref "VPP") (pin "TP") (pinfunction "TP_TP") (pintype "input"))
    )
    (net (code "193") (name "/VPP_PWM") (class "Default")
      (node (ref "IC2") (pin "5") (pinfunction "+IN_5") (pintype "input"))
      (node (ref "R24") (pin "2") (pinfunction "2_2") (pintype "passive"))
      (node (ref "U$2") (pin "14") (pinfunction "PA4_14") (pintype "bidirectional"))
    )
    (net (code "194") (name "/VPP_SENS") (class "Default")
      (node (ref "R31") (pin "1") (pinfunction "1_1") (pintype "passive"))
      (node (ref "R32") (pin "2") (pinfunction "2_2") (pintype "passive"))
      (node (ref "U$2") (pin "18") (pinfunction "PB0_18") (pintype "bidirectional"))
    )
    (net (code "195") (name "/VSW") (class "Default")
      (node (ref "D2") (pin "A") (pinfunction "A_A") (pintype "passive"))
      (node (ref "L10") (pin "P$2") (pinfunction "2_P$2") (pintype "passive"))
      (node (ref "U$15") (pin "1") (pinfunction "SW_1") (pintype "passive"))
    )
    (net (code "196") (name "/X0") (class "Default")
      (node (ref "IC8") (pin "1") (pinfunction "PB4_1") (pintype "passive"))
      (node (ref "U$26") (pin "2") (pinfunction "2_2") (pintype "passive"))
    )
    (net (code "197") (name "/X1") (class "Default")
      (node (ref "IC8") (pin "2") (pinfunction "PB5_2") (pintype "passive"))
      (node (ref "U$26") (pin "3") (pinfunction "3_3") (pintype "passive"))
    )
    (net (code "198") (name "/X2") (class "Default")
      (node (ref "IC8") (pin "3") (pinfunction "PB6_3") (pintype "passive"))
      (node (ref "U$26") (pin "4") (pinfunction "4_4") (pintype "passive"))
    )
    (net (code "199") (name "/X3") (class "Default")
      (node (ref "IC8") (pin "4") (pinfunction "PB7_4") (pintype "passive"))
      (node (ref "U$26") (pin "5") (pinfunction "5_5") (pintype "passive"))
    )
    (net (code "200") (name "/X4") (class "Default")
      (node (ref "IC8") (pin "6") (pinfunction "PA7_6") (pintype "passive"))
      (node (ref "U$26") (pin "6") (pinfunction "6_6") (pintype "passive"))
    )
    (net (code "201") (name "/X5") (class "Default")
      (node (ref "IC8") (pin "7") (pinfunction "PA6_7") (pintype "passive"))
      (node (ref "U$26") (pin "7") (pinfunction "7_7") (pintype "passive"))
    )
    (net (code "202") (name "/X6") (class "Default")
      (node (ref "IC8") (pin "8") (pinfunction "PA5_8") (pintype "passive"))
      (node (ref "U$26") (pin "8") (pinfunction "8_8") (pintype "passive"))
    )
    (net (code "203") (name "/X7") (class "Default")
      (node (ref "IC8") (pin "16") (pinfunction "PB3_16") (pintype "passive"))
      (node (ref "U$27") (pin "2") (pinfunction "2_2") (pintype "passive"))
    )
    (net (code "204") (name "/X8") (class "Default")
      (node (ref "IC8") (pin "15") (pinfunction "PB2_15") (pintype "passive"))
      (node (ref "U$27") (pin "3") (pinfunction "3_3") (pintype "passive"))
    )
    (net (code "205") (name "/X9") (class "Default")
      (node (ref "IC8") (pin "14") (pinfunction "PB1_14") (pintype "passive"))
      (node (ref "U$27") (pin "4") (pinfunction "4_4") (pintype "passive"))
    )
    (net (code "206") (name "/X10") (class "Default")
      (node (ref "IC8") (pin "13") (pinfunction "PB0_13") (pintype "passive"))
      (node (ref "U$27") (pin "5") (pinfunction "5_5") (pintype "passive"))
    )
    (net (code "207") (name "/X11") (class "Default")
      (node (ref "IC8") (pin "11") (pinfunction "PA0_11") (pintype "passive"))
      (node (ref "U$27") (pin "6") (pinfunction "6_6") (pintype "passive"))
    )
    (net (code "208") (name "/X12") (class "Default")
      (node (ref "IC8") (pin "10") (pinfunction "PA4_10") (pintype "passive"))
      (node (ref "U$27") (pin "7") (pinfunction "7_7") (pintype "passive"))
    )
    (net (code "209") (name "/X13") (class "Default")
      (node (ref "IC8") (pin "9") (pinfunction "PA3_9") (pintype "passive"))
      (node (ref "U$27") (pin "8") (pinfunction "8_8") (pintype "passive"))
    )
    (net (code "210") (name "/XBOOT0") (class "Default")
      (node (ref "JP1") (pin "1") (pinfunction "1_1") (pintype "passive"))
      (node (ref "R3") (pin "1") (pinfunction "1_1") (pintype "passive"))
      (node (ref "U1") (pin "60") (pinfunction "BOOT0_60") (pintype "input"))
    )
    (net (code "211") (name "/XI") (class "Default")
      (node (ref "IC1") (pin "5") (pinfunction "XTAL1/CLKIN_5") (pintype "bidirectional"))
      (node (ref "R40") (pin "2") (pinfunction "2_2") (pintype "passive"))
    )
    (net (code "212") (name "/XNRST") (class "Default")
      (node (ref "C61") (pin "2") (pinfunction "2_2") (pintype "passive"))
      (node (ref "R75") (pin "1") (pinfunction "1_1") (pintype "passive"))
      (node (ref "U$19") (pin "4") (pinfunction "NRST_4") (pintype "input"))
      (node (ref "U$23") (pin "4") (pinfunction "4_4") (pintype "passive"))
    )
    (net (code "213") (name "/XOSC_IN") (class "Default")
      (node (ref "C19") (pin "2") (pinfunction "2_2") (pintype "passive"))
      (node (ref "Q4") (pin "2") (pinfunction "2_2") (pintype "passive"))
      (node (ref "U1") (pin "5") (pinfunction "PD0_OSC_IN_5") (pintype "bidirectional"))
    )
    (net (code "214") (name "/XOSC_OUT") (class "Default")
      (node (ref "C20") (pin "2") (pinfunction "2_2") (pintype "passive"))
      (node (ref "Q4") (pin "1") (pinfunction "1_1") (pintype "passive"))
      (node (ref "U1") (pin "6") (pinfunction "PD1_OSC_OUT_6") (pintype "bidirectional"))
    )
    (net (code "215") (name "/XPA0") (class "Default")
      (node (ref "U1") (pin "14") (pinfunction "PA0-WKUP_14") (pintype "bidirectional"))
      (node (ref "X1") (pin "28") (pinfunction "1_28") (pintype "passive"))
    )
    (net (code "216") (name "/XPB0{slash}ADC8") (class "Default")
      (node (ref "U1") (pin "26") (pinfunction "PB0_26") (pintype "bidirectional"))
      (node (ref "X1") (pin "36") (pinfunction "1_36") (pintype "passive"))
    )
    (net (code "217") (name "/XPB1") (class "Default")
      (node (ref "U1") (pin "27") (pinfunction "PB1_27") (pintype "bidirectional"))
      (node (ref "X1") (pin "38") (pinfunction "1_38") (pintype "passive"))
    )
    (net (code "218") (name "/XPB2") (class "Default")
      (node (ref "U1") (pin "28") (pinfunction "PB2_28") (pintype "bidirectional"))
      (node (ref "X1") (pin "39") (pinfunction "1_39") (pintype "passive"))
    )
    (net (code "219") (name "/XPC0") (class "Default")
      (node (ref "U1") (pin "8") (pinfunction "PC0_8") (pintype "bidirectional"))
      (node (ref "X1") (pin "25") (pinfunction "1_25") (pintype "passive"))
    )
    (net (code "220") (name "/XPC2") (class "Default")
      (node (ref "U1") (pin "10") (pinfunction "PC2_10") (pintype "bidirectional"))
      (node (ref "X1") (pin "26") (pinfunction "1_26") (pintype "passive"))
    )
    (net (code "221") (name "/XPC3") (class "Default")
      (node (ref "U1") (pin "11") (pinfunction "PC3_11") (pintype "bidirectional"))
      (node (ref "X1") (pin "27") (pinfunction "1_27") (pintype "passive"))
    )
    (net (code "222") (name "/XPC6") (class "Default")
      (node (ref "U1") (pin "37") (pinfunction "PC6_37") (pintype "bidirectional"))
      (node (ref "X1") (pin "24") (pinfunction "1_24") (pintype "passive"))
    )
    (net (code "223") (name "/XPC7") (class "Default")
      (node (ref "U1") (pin "38") (pinfunction "PC7_38") (pintype "bidirectional"))
      (node (ref "X1") (pin "23") (pinfunction "1_23") (pintype "passive"))
    )
    (net (code "224") (name "/XPC13") (class "Default")
      (node (ref "U1") (pin "2") (pinfunction "PC13-TAMPER-RTC_2") (pintype "bidirectional"))
      (node (ref "X1") (pin "14") (pinfunction "1_14") (pintype "passive"))
    )
    (net (code "225") (name "/XPC14") (class "Default")
      (node (ref "U1") (pin "3") (pinfunction "PC14-OSC32_IN_3") (pintype "bidirectional"))
      (node (ref "X1") (pin "15") (pinfunction "1_15") (pintype "passive"))
    )
    (net (code "226") (name "/XPC15") (class "Default")
      (node (ref "U1") (pin "4") (pinfunction "PC15-OSC32_OUT_4") (pintype "bidirectional"))
      (node (ref "X1") (pin "16") (pinfunction "1_16") (pintype "passive"))
    )
    (net (code "227") (name "/XSCL") (class "Default")
      (node (ref "R35") (pin "1") (pinfunction "1_1") (pintype "passive"))
      (node (ref "U$22") (pin "3") (pinfunction "3_3") (pintype "passive"))
      (node (ref "U1") (pin "61") (pinfunction "PB8_61") (pintype "bidirectional"))
      (node (ref "X1") (pin "6") (pinfunction "1_6") (pintype "passive"))
    )
    (net (code "228") (name "/XSDA") (class "Default")
      (node (ref "R37") (pin "1") (pinfunction "1_1") (pintype "passive"))
      (node (ref "U$22") (pin "4") (pinfunction "4_4") (pintype "passive"))
      (node (ref "U1") (pin "62") (pinfunction "PB9_62") (pintype "bidirectional"))
      (node (ref "X1") (pin "7") (pinfunction "1_7") (pintype "passive"))
    )
    (net (code "229") (name "/XSPI_MISO") (class "Default")
      (node (ref "R67") (pin "1") (pinfunction "1_1") (pintype "passive"))
      (node (ref "R70") (pin "1") (pinfunction "1_1") (pintype "passive"))
      (node (ref "U1") (pin "56") (pinfunction "PB4_56") (pintype "bidirectional"))
      (node (ref "X1") (pin "9") (pinfunction "1_9") (pintype "passive"))
    )
    (net (code "230") (name "/XSPI_MOSI") (class "Default")
      (node (ref "R68") (pin "1") (pinfunction "1_1") (pintype "passive"))
      (node (ref "R69") (pin "1") (pinfunction "1_1") (pintype "passive"))
      (node (ref "U1") (pin "57") (pinfunction "PB5_57") (pintype "bidirectional"))
      (node (ref "X1") (pin "10") (pinfunction "1_10") (pintype "passive"))
    )
    (net (code "231") (name "/XSPI_SCK") (class "Default")
      (node (ref "R66") (pin "1") (pinfunction "1_1") (pintype "passive"))
      (node (ref "U1") (pin "55") (pinfunction "PB3_55") (pintype "bidirectional"))
      (node (ref "X1") (pin "8") (pinfunction "1_8") (pintype "passive"))
    )
    (net (code "232") (name "/XSW") (class "Default")
      (node (ref "IC4") (pin "2") (pinfunction "SW_2") (pintype "power_in"))
      (node (ref "L13") (pin "P$1") (pinfunction "1_P$1") (pintype "passive"))
    )
    (net (code "233") (name "/XUSBDM") (class "Default")
      (node (ref "R12") (pin "2") (pinfunction "2_2") (pintype "passive"))
      (node (ref "U1") (pin "44") (pinfunction "PA11_44") (pintype "bidirectional"))
    )
    (net (code "234") (name "/XUSBDP") (class "Default")
      (node (ref "R14") (pin "2") (pinfunction "2_2") (pintype "passive"))
      (node (ref "U1") (pin "45") (pinfunction "PA12_45") (pintype "bidirectional"))
    )
    (net (code "235") (name "/XVDDA") (class "Default")
      (node (ref "C12") (pin "2") (pinfunction "2_2") (pintype "passive"))
      (node (ref "C7") (pin "1") (pinfunction "1_1") (pintype "passive"))
      (node (ref "L1") (pin "2") (pinfunction "2_2") (pintype "passive"))
      (node (ref "U1") (pin "13") (pinfunction "VDDA_13") (pintype "power_in"))
    )
    (net (code "236") (name "/XXNRST") (class "Default")
      (node (ref "R1") (pin "2") (pinfunction "2_2") (pintype "passive"))
      (node (ref "S1") (pin "P$2") (pinfunction "2_P$2") (pintype "passive"))
      (node (ref "U1") (pin "7") (pinfunction "NRST_7") (pintype "bidirectional"))
    )
    (net (code "237") (name "GND") (class "Default")
      (node (ref "C1") (pin "2") (pinfunction "2_2") (pintype "passive"))
      (node (ref "C10") (pin "1") (pinfunction "1_1") (pintype "passive"))
      (node (ref "C11") (pin "1") (pinfunction "1_1") (pintype "passive"))
      (node (ref "C12") (pin "1") (pinfunction "1_1") (pintype "passive"))
      (node (ref "C14") (pin "1") (pinfunction "1_1") (pintype "passive"))
      (node (ref "C15") (pin "1") (pinfunction "1_1") (pintype "passive"))
      (node (ref "C16") (pin "1") (pinfunction "1_1") (pintype "passive"))
      (node (ref "C17") (pin "1") (pinfunction "1_1") (pintype "passive"))
      (node (ref "C18") (pin "1") (pinfunction "1_1") (pintype "passive"))
      (node (ref "C19") (pin "1") (pinfunction "1_1") (pintype "passive"))
      (node (ref "C2") (pin "2") (pinfunction "2_2") (pintype "passive"))
      (node (ref "C20") (pin "1") (pinfunction "1_1") (pintype "passive"))
      (node (ref "C21") (pin "1") (pinfunction "1_1") (pintype "passive"))
      (node (ref "C22") (pin "2") (pinfunction "2_2") (pintype "passive"))
      (node (ref "C23") (pin "1") (pinfunction "1_1") (pintype "passive"))
      (node (ref "C24") (pin "2") (pinfunction "2_2") (pintype "passive"))
      (node (ref "C25") (pin "2") (pinfunction "2_2") (pintype "passive"))
      (node (ref "C26") (pin "2") (pinfunction "2_2") (pintype "passive"))
      (node (ref "C27") (pin "2") (pinfunction "2_2") (pintype "passive"))
      (node (ref "C28") (pin "1") (pinfunction "1_1") (pintype "passive"))
      (node (ref "C29") (pin "1") (pinfunction "1_1") (pintype "passive"))
      (node (ref "C3") (pin "2") (pinfunction "2_2") (pintype "passive"))
      (node (ref "C30") (pin "1") (pinfunction "1_1") (pintype "passive"))
      (node (ref "C31") (pin "1") (pinfunction "1_1") (pintype "passive"))
      (node (ref "C32") (pin "1") (pinfunction "1_1") (pintype "passive"))
      (node (ref "C33") (pin "1") (pinfunction "1_1") (pintype "passive"))
      (node (ref "C34") (pin "2") (pinfunction "2_2") (pintype "passive"))
      (node (ref "C35") (pin "2") (pinfunction "2_2") (pintype "passive"))
      (node (ref "C36") (pin "1") (pinfunction "1_1") (pintype "passive"))
      (node (ref "C37") (pin "1") (pinfunction "1_1") (pintype "passive"))
      (node (ref "C38") (pin "1") (pinfunction "1_1") (pintype "passive"))
      (node (ref "C39") (pin "1") (pinfunction "1_1") (pintype "passive"))
      (node (ref "C4") (pin "2") (pinfunction "2_2") (pintype "passive"))
      (node (ref "C40") (pin "1") (pinfunction "1_1") (pintype "passive"))
      (node (ref "C41") (pin "1") (pinfunction "1_1") (pintype "passive"))
      (node (ref "C42") (pin "1") (pinfunction "1_1") (pintype "passive"))
      (node (ref "C43") (pin "2") (pinfunction "2_2") (pintype "passive"))
      (node (ref "C44") (pin "1") (pinfunction "1_1") (pintype "passive"))
      (node (ref "C45") (pin "1") (pinfunction "1_1") (pintype "passive"))
      (node (ref "C46") (pin "1") (pinfunction "1_1") (pintype "passive"))
      (node (ref "C47") (pin "2") (pinfunction "2_2") (pintype "passive"))
      (node (ref "C48") (pin "1") (pinfunction "1_1") (pintype "passive"))
      (node (ref "C49") (pin "2") (pinfunction "2_2") (pintype "passive"))
      (node (ref "C5") (pin "1") (pinfunction "1_1") (pintype "passive"))
      (node (ref "C50") (pin "1") (pinfunction "1_1") (pintype "passive"))
      (node (ref "C51") (pin "1") (pinfunction "1_1") (pintype "passive"))
      (node (ref "C52") (pin "2") (pinfunction "2_2") (pintype "passive"))
      (node (ref "C53") (pin "2") (pinfunction "2_2") (pintype "passive"))
      (node (ref "C54") (pin "1") (pinfunction "1_1") (pintype "passive"))
      (node (ref "C55") (pin "1") (pinfunction "1_1") (pintype "passive"))
      (node (ref "C56") (pin "2") (pinfunction "2_2") (pintype "passive"))
      (node (ref "C57") (pin "2") (pinfunction "2_2") (pintype "passive"))
      (node (ref "C58") (pin "1") (pinfunction "1_1") (pintype "passive"))
      (node (ref "C59") (pin "1") (pinfunction "1_1") (pintype "passive"))
      (node (ref "C6") (pin "1") (pinfunction "1_1") (pintype "passive"))
      (node (ref "C60") (pin "2") (pinfunction "2_2") (pintype "passive"))
      (node (ref "C61") (pin "1") (pinfunction "1_1") (pintype "passive"))
      (node (ref "C62") (pin "1") (pinfunction "1_1") (pintype "passive"))
      (node (ref "C64") (pin "1") (pinfunction "1_1") (pintype "passive"))
      (node (ref "C65") (pin "1") (pinfunction "1_1") (pintype "passive"))
      (node (ref "C66") (pin "2") (pinfunction "2_2") (pintype "passive"))
      (node (ref "C67") (pin "1") (pinfunction "1_1") (pintype "passive"))
      (node (ref "C68") (pin "1") (pinfunction "1_1") (pintype "passive"))
      (node (ref "C69") (pin "1") (pinfunction "1_1") (pintype "passive"))
      (node (ref "C7") (pin "2") (pinfunction "2_2") (pintype "passive"))
      (node (ref "C70") (pin "2") (pinfunction "2_2") (pintype "passive"))
      (node (ref "C71") (pin "1") (pinfunction "1_1") (pintype "passive"))
      (node (ref "C72") (pin "1") (pinfunction "1_1") (pintype "passive"))
      (node (ref "C73") (pin "2") (pinfunction "2_2") (pintype "passive"))
      (node (ref "C74") (pin "1") (pinfunction "1_1") (pintype "passive"))
      (node (ref "C75") (pin "2") (pinfunction "2_2") (pintype "passive"))
      (node (ref "C76") (pin "1") (pinfunction "1_1") (pintype "passive"))
      (node (ref "C77") (pin "1") (pinfunction "1_1") (pintype "passive"))
      (node (ref "C78") (pin "1") (pinfunction "1_1") (pintype "passive"))
      (node (ref "C79") (pin "1") (pinfunction "1_1") (pintype "passive"))
      (node (ref "C8") (pin "1") (pinfunction "1_1") (pintype "passive"))
      (node (ref "C80") (pin "1") (pinfunction "1_1") (pintype "passive"))
      (node (ref "C81") (pin "1") (pinfunction "1_1") (pintype "passive"))
      (node (ref "C82") (pin "1") (pinfunction "1_1") (pintype "passive"))
      (node (ref "D4") (pin "K") (pinfunction "K_K") (pintype "passive"))
      (node (ref "IC1") (pin "P") (pinfunction "VSS_P") (pintype "bidirectional"))
      (node (ref "IC4") (pin "1") (pinfunction "PGND_1") (pintype "power_in"))
      (node (ref "IC4") (pin "3") (pinfunction "AGND_3") (pintype "power_in"))
      (node (ref "IC4") (pin "6") (pinfunction "MODE_6") (pintype "bidirectional"))
      (node (ref "IC4") (pin "EXP") (pinfunction "PGND_EXP") (pintype "power_in"))
      (node (ref "IC5") (pin "12") (pinfunction "12_12") (pintype "passive"))
      (node (ref "IC6") (pin "7") (pinfunction "VEE_7") (pintype "power_in"))
      (node (ref "IC6") (pin "8") (pinfunction "GND_8") (pintype "power_in"))
      (node (ref "IC7") (pin "7") (pinfunction "VEE_7") (pintype "power_in"))
      (node (ref "IC7") (pin "8") (pinfunction "GND_8") (pintype "power_in"))
      (node (ref "IC8") (pin "12") (pinfunction "GND_12") (pintype "power_in"))
      (node (ref "IC9") (pin "2") (pinfunction "GND_2") (pintype "power_in"))
      (node (ref "J1") (pin "2") (pinfunction "2_2") (pintype "passive"))
      (node (ref "J3") (pin "1") (pinfunction "1_1") (pintype "passive"))
      (node (ref "J4") (pin "2") (pinfunction "2_2") (pintype "passive"))
      (node (ref "J6") (pin "6") (pinfunction "6_6") (pintype "passive"))
      (node (ref "JP10") (pin "1") (pinfunction "1_1") (pintype "passive"))
      (node (ref "JP11") (pin "1") (pinfunction "1_1") (pintype "passive"))
      (node (ref "JP2") (pin "1") (pinfunction "1_1") (pintype "passive"))
      (node (ref "JP3") (pin "1") (pinfunction "1_1") (pintype "passive"))
      (node (ref "JP4") (pin "1") (pinfunction "1_1") (pintype "passive"))
      (node (ref "JP5") (pin "2") (pinfunction "2_2") (pintype "passive"))
      (node (ref "JP7") (pin "1") (pinfunction "1_1") (pintype "passive"))
      (node (ref "JP8") (pin "2") (pinfunction "2_2") (pintype "passive"))
      (node (ref "M1") (pin "1") (pinfunction "GND_1") (pintype "power_in"))
      (node (ref "M2") (pin "1") (pinfunction "GND_1") (pintype "power_in"))
      (node (ref "M3") (pin "1") (pinfunction "GND_1") (pintype "power_in"))
      (node (ref "P1") (pin "1") (pinfunction "1_1") (pintype "passive"))
      (node (ref "P2") (pin "3") (pinfunction "3_3") (pintype "passive"))
      (node (ref "Q8") (pin "2") (pinfunction "S_2") (pintype "passive"))
      (node (ref "R23") (pin "1") (pinfunction "1_1") (pintype "passive"))
      (node (ref "R24") (pin "1") (pinfunction "1_1") (pintype "passive"))
      (node (ref "R27") (pin "1") (pinfunction "1_1") (pintype "passive"))
      (node (ref "R29") (pin "1") (pinfunction "1_1") (pintype "passive"))
      (node (ref "R3") (pin "2") (pinfunction "2_2") (pintype "passive"))
      (node (ref "R30") (pin "1") (pinfunction "1_1") (pintype "passive"))
      (node (ref "R32") (pin "1") (pinfunction "1_1") (pintype "passive"))
      (node (ref "R34") (pin "1") (pinfunction "1_1") (pintype "passive"))
      (node (ref "R43") (pin "1") (pinfunction "1_1") (pintype "passive"))
      (node (ref "R72") (pin "1") (pinfunction "1_1") (pintype "passive"))
      (node (ref "R74") (pin "1") (pinfunction "1_1") (pintype "passive"))
      (node (ref "R76") (pin "1") (pinfunction "1_1") (pintype "passive"))
      (node (ref "R82") (pin "1") (pinfunction "1_1") (pintype "passive"))
      (node (ref "S1") (pin "P$1") (pinfunction "1_P$1") (pintype "passive"))
      (node (ref "S2") (pin "P$2") (pinfunction "2_P$2") (pintype "passive"))
      (node (ref "S3") (pin "P$2") (pinfunction "2_P$2") (pintype "passive"))
      (node (ref "TP11") (pin "TP") (pinfunction "TP_TP") (pintype "input"))
      (node (ref "TP12") (pin "TP") (pinfunction "TP_TP") (pintype "input"))
      (node (ref "TP13") (pin "TP") (pinfunction "TP_TP") (pintype "input"))
      (node (ref "U$1") (pin "4") (pinfunction "4_4") (pintype "passive"))
      (node (ref "U$10") (pin "1") (pinfunction "1_1") (pintype "passive"))
      (node (ref "U$12") (pin "3") (pinfunction "3_3") (pintype "passive"))
      (node (ref "U$12") (pin "4") (pinfunction "4_4") (pintype "passive"))
      (node (ref "U$13") (pin "2") (pinfunction "GND_2") (pintype "power_in"))
      (node (ref "U$14") (pin "2") (pinfunction "GND_2") (pintype "power_in"))
      (node (ref "U$15") (pin "2") (pinfunction "GND_2") (pintype "power_in"))
      (node (ref "U$18") (pin "1") (pinfunction "1_1") (pintype "passive"))
      (node (ref "U$19") (pin "15") (pinfunction "VSS_15") (pintype "power_in"))
      (node (ref "U$2") (pin "23") (pinfunction "VSS_23") (pintype "power_in"))
      (node (ref "U$2") (pin "35") (pinfunction "VSS_35") (pintype "power_in"))
      (node (ref "U$2") (pin "47") (pinfunction "VSS_47") (pintype "power_in"))
      (node (ref "U$2") (pin "8") (pinfunction "VSSA_8") (pintype "power_in"))
      (node (ref "U$20") (pin "12") (pinfunction "GND_12") (pintype "power_in"))
      (node (ref "U$22") (pin "1") (pinfunction "1_1") (pintype "passive"))
      (node (ref "U$23") (pin "8") (pinfunction "8_8") (pintype "passive"))
      (node (ref "U$25") (pin "GND") (pinfunction "GND_GND") (pintype "power_in"))
      (node (ref "U$25") (pin "GND1") (pinfunction "GND_GND1") (pintype "power_in"))
      (node (ref "U$26") (pin "1") (pinfunction "1_1") (pintype "passive"))
      (node (ref "U$27") (pin "1") (pinfunction "1_1") (pintype "passive"))
      (node (ref "U$28") (pin "2") (pinfunction "GND_2") (pintype "power_in"))
      (node (ref "U$29") (pin "15") (pinfunction "VSS_15") (pintype "power_in"))
      (node (ref "U$30") (pin "4") (pinfunction "4_4") (pintype "passive"))
      (node (ref "U$4") (pin "7") (pinfunction "VSS_7") (pintype "power_in"))
      (node (ref "U$5") (pin "4") (pinfunction "GND_4") (pintype "power_in"))
      (node (ref "U$7") (pin "12") (pinfunction "GND_12") (pintype "power_in"))
      (node (ref "U$8") (pin "4") (pinfunction "4_4") (pintype "passive"))
      (node (ref "U1") (pin "12") (pinfunction "VSSA_12") (pintype "power_in"))
      (node (ref "U1") (pin "18") (pinfunction "VSS_4_18") (pintype "power_in"))
      (node (ref "U1") (pin "31") (pinfunction "VSS_1_31") (pintype "power_in"))
      (node (ref "U1") (pin "47") (pinfunction "VSS_2_47") (pintype "power_in"))
      (node (ref "U1") (pin "63") (pinfunction "VSS_3_63") (pintype "power_in"))
      (node (ref "U2") (pin "1") (pinfunction "GND_1") (pintype "bidirectional"))
      (node (ref "U2") (pin "15") (pinfunction "GND_15") (pintype "bidirectional"))
      (node (ref "U2") (pin "38") (pinfunction "GND_38") (pintype "bidirectional"))
      (node (ref "U2") (pin "GND") (pinfunction "GND_GND") (pintype "bidirectional"))
      (node (ref "U3") (pin "2") (pinfunction "GND_2") (pintype "power_in"))
      (node (ref "U4") (pin "14") (pinfunction "GND_14") (pintype "power_in"))
      (node (ref "USB1") (pin "P5") (pinfunction "GND_P5") (pintype "bidirectional"))
      (node (ref "USB2") (pin "P5") (pinfunction "GND_P5") (pintype "bidirectional"))
      (node (ref "USB3") (pin "P5") (pinfunction "GND_P5") (pintype "bidirectional"))
      (node (ref "X1") (pin "11") (pinfunction "1_11") (pintype "passive"))
      (node (ref "X1") (pin "29") (pinfunction "1_29") (pintype "passive"))
      (node (ref "X1") (pin "31") (pinfunction "1_31") (pintype "passive"))
      (node (ref "X1") (pin "33") (pinfunction "1_33") (pintype "passive"))
      (node (ref "X1") (pin "35") (pinfunction "1_35") (pintype "passive"))
      (node (ref "X1") (pin "37") (pinfunction "1_37") (pintype "passive"))
      (node (ref "X1") (pin "4") (pinfunction "1_4") (pintype "passive"))
      (node (ref "X1") (pin "40") (pinfunction "1_40") (pintype "passive"))
      (node (ref "X1") (pin "5") (pinfunction "1_5") (pintype "passive"))
      (node (ref "X2") (pin "11") (pinfunction "1_11") (pintype "passive"))
      (node (ref "X2") (pin "29") (pinfunction "1_29") (pintype "passive"))
      (node (ref "X2") (pin "31") (pinfunction "1_31") (pintype "passive"))
      (node (ref "X2") (pin "33") (pinfunction "1_33") (pintype "passive"))
      (node (ref "X2") (pin "35") (pinfunction "1_35") (pintype "passive"))
      (node (ref "X2") (pin "37") (pinfunction "1_37") (pintype "passive"))
      (node (ref "X2") (pin "4") (pinfunction "1_4") (pintype "passive"))
      (node (ref "X2") (pin "40") (pinfunction "1_40") (pintype "passive"))
      (node (ref "X2") (pin "5") (pinfunction "1_5") (pintype "passive"))
    )
    (net (code "238") (name "Net-(C5-Pad2)") (class "Default")
      (node (ref "C5") (pin "2") (pinfunction "2_2") (pintype "passive"))
      (node (ref "J2") (pin "1") (pinfunction "1_1") (pintype "passive"))
      (node (ref "JP3") (pin "2") (pinfunction "2_2") (pintype "passive"))
      (node (ref "L2") (pin "1") (pinfunction "1_1") (pintype "passive"))
    )
    (net (code "239") (name "Net-(C6-Pad2)") (class "Default")
      (node (ref "C6") (pin "2") (pinfunction "2_2") (pintype "passive"))
      (node (ref "J1") (pin "1") (pinfunction "1_1") (pintype "passive"))
      (node (ref "L3") (pin "1") (pinfunction "1_1") (pintype "passive"))
    )
    (net (code "240") (name "Net-(C28-Pad2)") (class "Default")
      (node (ref "C28") (pin "2") (pinfunction "2_2") (pintype "passive"))
      (node (ref "L5") (pin "2") (pinfunction "2_2") (pintype "passive"))
      (node (ref "R39") (pin "2") (pinfunction "2_2") (pintype "passive"))
      (node (ref "R41") (pin "2") (pinfunction "2_2") (pintype "passive"))
      (node (ref "R44") (pin "2") (pinfunction "2_2") (pintype "passive"))
      (node (ref "R46") (pin "2") (pinfunction "2_2") (pintype "passive"))
    )
    (net (code "241") (name "Net-(C34-Pad1)") (class "Default")
      (node (ref "C34") (pin "1") (pinfunction "1_1") (pintype "passive"))
      (node (ref "T1") (pin "4") (pinfunction "4_4") (pintype "bidirectional"))
    )
    (net (code "242") (name "Net-(C35-Pad1)") (class "Default")
      (node (ref "C35") (pin "1") (pinfunction "1_1") (pintype "passive"))
      (node (ref "T1") (pin "5") (pinfunction "5_5") (pintype "bidirectional"))
    )
    (net (code "243") (name "Net-(C36-Pad2)") (class "Default")
      (node (ref "C36") (pin "2") (pinfunction "2_2") (pintype "passive"))
      (node (ref "JP6") (pin "1") (pinfunction "1_1") (pintype "passive"))
      (node (ref "L6") (pin "2") (pinfunction "2_2") (pintype "passive"))
    )
    (net (code "244") (name "Net-(C37-Pad2)") (class "Default")
      (node (ref "C37") (pin "2") (pinfunction "2_2") (pintype "passive"))
      (node (ref "JP6") (pin "2") (pinfunction "2_2") (pintype "passive"))
    )
    (net (code "245") (name "Net-(C41-Pad2)") (class "Default")
      (node (ref "C41") (pin "2") (pinfunction "2_2") (pintype "passive"))
      (node (ref "J4") (pin "1") (pinfunction "1_1") (pintype "passive"))
      (node (ref "J5") (pin "1") (pinfunction "1_1") (pintype "passive"))
      (node (ref "L8") (pin "1") (pinfunction "1_1") (pintype "passive"))
    )
    (net (code "246") (name "Net-(C63-Pad2)") (class "Default")
      (node (ref "C63") (pin "2") (pinfunction "2_2") (pintype "passive"))
      (node (ref "D3") (pin "K") (pinfunction "K_K") (pintype "passive"))
      (node (ref "D4") (pin "A") (pinfunction "A_A") (pintype "passive"))
    )
    (net (code "247") (name "Net-(D1-A)") (class "Default")
      (node (ref "D1") (pin "2") (pinfunction "A_2") (pintype "passive"))
      (node (ref "L4") (pin "2") (pinfunction "2_2") (pintype "passive"))
    )
    (net (code "248") (name "Net-(IC1-RBIAS)") (class "Default")
      (node (ref "IC1") (pin "24") (pinfunction "RBIAS_24") (pintype "bidirectional"))
      (node (ref "R30") (pin "2") (pinfunction "2_2") (pintype "passive"))
    )
    (net (code "249") (name "Net-(IC1-VDDCR)") (class "Default")
      (node (ref "C21") (pin "2") (pinfunction "2_2") (pintype "passive"))
      (node (ref "C23") (pin "2") (pinfunction "2_2") (pintype "passive"))
      (node (ref "IC1") (pin "6") (pinfunction "VDDCR_6") (pintype "bidirectional"))
    )
    (net (code "250") (name "Net-(IC2A--IN)") (class "Default")
      (node (ref "IC2") (pin "2") (pinfunction "-IN_2") (pintype "input"))
      (node (ref "R26") (pin "2") (pinfunction "2_2") (pintype "passive"))
      (node (ref "R27") (pin "2") (pinfunction "2_2") (pintype "passive"))
    )
    (net (code "251") (name "Net-(IC2B--IN)") (class "Default")
      (node (ref "IC2") (pin "6") (pinfunction "-IN_6") (pintype "input"))
      (node (ref "R28") (pin "2") (pinfunction "2_2") (pintype "passive"))
      (node (ref "R29") (pin "2") (pinfunction "2_2") (pintype "passive"))
    )
    (net (code "252") (name "Net-(IC3-Pad1)") (class "Default")
      (node (ref "IC3") (pin "1") (pinfunction "1_1") (pintype "bidirectional"))
      (node (ref "U$6") (pin "8") (pinfunction "8_8") (pintype "passive"))
      (node (ref "U$9") (pin "8") (pinfunction "8_8") (pintype "passive"))
    )
    (net (code "253") (name "Net-(IC3-Pad2)") (class "Default")
      (node (ref "IC3") (pin "2") (pinfunction "2_2") (pintype "bidirectional"))
      (node (ref "U$6") (pin "7") (pinfunction "7_7") (pintype "passive"))
      (node (ref "U$9") (pin "7") (pinfunction "7_7") (pintype "passive"))
    )
    (net (code "254") (name "Net-(IC3-Pad3)") (class "Default")
      (node (ref "IC3") (pin "3") (pinfunction "3_3") (pintype "bidirectional"))
      (node (ref "U$6") (pin "6") (pinfunction "6_6") (pintype "passive"))
      (node (ref "U$9") (pin "6") (pinfunction "6_6") (pintype "passive"))
    )
    (net (code "255") (name "Net-(IC3-Pad4)") (class "Default")
      (node (ref "IC3") (pin "4") (pinfunction "4_4") (pintype "bidirectional"))
      (node (ref "U$6") (pin "5") (pinfunction "5_5") (pintype "passive"))
      (node (ref "U$9") (pin "5") (pinfunction "5_5") (pintype "passive"))
    )
    (net (code "256") (name "Net-(IC3-Pad5)") (class "Default")
      (node (ref "IC3") (pin "5") (pinfunction "5_5") (pintype "bidirectional"))
      (node (ref "U$6") (pin "4") (pinfunction "4_4") (pintype "passive"))
      (node (ref "U$9") (pin "4") (pinfunction "4_4") (pintype "passive"))
    )
    (net (code "257") (name "Net-(IC3-Pad6)") (class "Default")
      (node (ref "IC3") (pin "6") (pinfunction "6_6") (pintype "bidirectional"))
      (node (ref "U$6") (pin "3") (pinfunction "3_3") (pintype "passive"))
      (node (ref "U$9") (pin "3") (pinfunction "3_3") (pintype "passive"))
    )
    (net (code "258") (name "Net-(IC3-Pad7)") (class "Default")
      (node (ref "IC3") (pin "7") (pinfunction "7_7") (pintype "bidirectional"))
      (node (ref "U$6") (pin "2") (pinfunction "2_2") (pintype "passive"))
      (node (ref "U$9") (pin "2") (pinfunction "2_2") (pintype "passive"))
    )
    (net (code "259") (name "Net-(IC3-Pad8)") (class "Default")
      (node (ref "IC3") (pin "8") (pinfunction "8_8") (pintype "bidirectional"))
      (node (ref "U$6") (pin "1") (pinfunction "1_1") (pintype "passive"))
      (node (ref "U$9") (pin "1") (pinfunction "1_1") (pintype "passive"))
    )
    (net (code "260") (name "Net-(IC3-Pad9)") (class "Default")
      (node (ref "IC3") (pin "9") (pinfunction "9_9") (pintype "bidirectional"))
      (node (ref "U$11") (pin "1") (pinfunction "1_1") (pintype "passive"))
      (node (ref "U$9") (pin "16") (pinfunction "16_16") (pintype "passive"))
    )
    (net (code "261") (name "Net-(IC3-Pad10)") (class "Default")
      (node (ref "IC3") (pin "10") (pinfunction "10_10") (pintype "bidirectional"))
      (node (ref "U$11") (pin "2") (pinfunction "2_2") (pintype "passive"))
      (node (ref "U$9") (pin "15") (pinfunction "15_15") (pintype "passive"))
    )
    (net (code "262") (name "Net-(IC3-Pad11)") (class "Default")
      (node (ref "IC3") (pin "11") (pinfunction "11_11") (pintype "bidirectional"))
      (node (ref "U$11") (pin "3") (pinfunction "3_3") (pintype "passive"))
      (node (ref "U$9") (pin "14") (pinfunction "14_14") (pintype "passive"))
    )
    (net (code "263") (name "Net-(IC3-Pad12)") (class "Default")
      (node (ref "IC3") (pin "12") (pinfunction "12_12") (pintype "bidirectional"))
      (node (ref "U$11") (pin "4") (pinfunction "4_4") (pintype "passive"))
      (node (ref "U$9") (pin "13") (pinfunction "13_13") (pintype "passive"))
    )
    (net (code "264") (name "Net-(IC3-Pad13)") (class "Default")
      (node (ref "IC3") (pin "13") (pinfunction "13_13") (pintype "bidirectional"))
      (node (ref "U$11") (pin "5") (pinfunction "5_5") (pintype "passive"))
      (node (ref "U$9") (pin "12") (pinfunction "12_12") (pintype "passive"))
    )
    (net (code "265") (name "Net-(IC3-Pad14)") (class "Default")
      (node (ref "IC3") (pin "14") (pinfunction "14_14") (pintype "bidirectional"))
      (node (ref "U$11") (pin "6") (pinfunction "6_6") (pintype "passive"))
      (node (ref "U$9") (pin "11") (pinfunction "11_11") (pintype "passive"))
    )
    (net (code "266") (name "Net-(IC3-Pad15)") (class "Default")
      (node (ref "IC3") (pin "15") (pinfunction "15_15") (pintype "bidirectional"))
      (node (ref "U$11") (pin "7") (pinfunction "7_7") (pintype "passive"))
      (node (ref "U$9") (pin "10") (pinfunction "10_10") (pintype "passive"))
    )
    (net (code "267") (name "Net-(IC3-Pad16)") (class "Default")
      (node (ref "IC3") (pin "16") (pinfunction "16_16") (pintype "bidirectional"))
      (node (ref "U$11") (pin "8") (pinfunction "8_8") (pintype "passive"))
      (node (ref "U$9") (pin "9") (pinfunction "9_9") (pintype "passive"))
    )
    (net (code "268") (name "Net-(IC5-Pad1)") (class "Default")
      (node (ref "IC5") (pin "1") (pinfunction "1_1") (pintype "passive"))
      (node (ref "TP24") (pin "TP") (pinfunction "TP_TP") (pintype "input"))
    )
    (net (code "269") (name "Net-(IC5-Pad2)") (class "Default")
      (node (ref "IC5") (pin "2") (pinfunction "2_2") (pintype "passive"))
      (node (ref "TP25") (pin "TP") (pinfunction "TP_TP") (pintype "input"))
    )
    (net (code "270") (name "Net-(IC5-Pad3)") (class "Default")
      (node (ref "IC5") (pin "3") (pinfunction "3_3") (pintype "passive"))
      (node (ref "TP26") (pin "TP") (pinfunction "TP_TP") (pintype "input"))
    )
    (net (code "271") (name "Net-(IC5-Pad4)") (class "Default")
      (node (ref "IC5") (pin "4") (pinfunction "4_4") (pintype "passive"))
      (node (ref "TP27") (pin "TP") (pinfunction "TP_TP") (pintype "input"))
    )
    (net (code "272") (name "Net-(IC5-Pad13)") (class "Default")
      (node (ref "IC5") (pin "13") (pinfunction "13_13") (pintype "passive"))
      (node (ref "TP20") (pin "TP") (pinfunction "TP_TP") (pintype "input"))
    )
    (net (code "273") (name "Net-(IC5-Pad14)") (class "Default")
      (node (ref "IC5") (pin "14") (pinfunction "14_14") (pintype "passive"))
      (node (ref "TP21") (pin "TP") (pinfunction "TP_TP") (pintype "input"))
    )
    (net (code "274") (name "Net-(IC5-Pad15)") (class "Default")
      (node (ref "IC5") (pin "15") (pinfunction "15_15") (pintype "passive"))
      (node (ref "TP22") (pin "TP") (pinfunction "TP_TP") (pintype "input"))
    )
    (net (code "275") (name "Net-(IC5-Pad16)") (class "Default")
      (node (ref "IC5") (pin "16") (pinfunction "16_16") (pintype "passive"))
      (node (ref "TP23") (pin "TP") (pinfunction "TP_TP") (pintype "input"))
    )
    (net (code "276") (name "Net-(IC6A-X)") (class "Default")
      (node (ref "IC6") (pin "3") (pinfunction "X_3") (pintype "bidirectional"))
      (node (ref "IC7") (pin "3") (pinfunction "X_3") (pintype "bidirectional"))
    )
    (net (code "277") (name "Net-(IC6A-X0)") (class "Default")
      (node (ref "IC6") (pin "13") (pinfunction "X0_13") (pintype "bidirectional"))
      (node (ref "JP12") (pin "8") (pinfunction "8_8") (pintype "passive"))
    )
    (net (code "278") (name "Net-(IC6A-X1)") (class "Default")
      (node (ref "IC6") (pin "14") (pinfunction "X1_14") (pintype "bidirectional"))
      (node (ref "JP12") (pin "7") (pinfunction "7_7") (pintype "passive"))
    )
    (net (code "279") (name "Net-(IC6A-X2)") (class "Default")
      (node (ref "IC6") (pin "15") (pinfunction "X2_15") (pintype "bidirectional"))
      (node (ref "JP12") (pin "6") (pinfunction "6_6") (pintype "passive"))
    )
    (net (code "280") (name "Net-(IC6A-X3)") (class "Default")
      (node (ref "IC6") (pin "12") (pinfunction "X3_12") (pintype "bidirectional"))
      (node (ref "JP12") (pin "5") (pinfunction "5_5") (pintype "passive"))
    )
    (net (code "281") (name "Net-(IC6A-X4)") (class "Default")
      (node (ref "IC6") (pin "1") (pinfunction "X4_1") (pintype "bidirectional"))
      (node (ref "JP12") (pin "4") (pinfunction "4_4") (pintype "passive"))
    )
    (net (code "282") (name "Net-(IC6A-X5)") (class "Default")
      (node (ref "IC6") (pin "5") (pinfunction "X5_5") (pintype "bidirectional"))
      (node (ref "JP12") (pin "3") (pinfunction "3_3") (pintype "passive"))
    )
    (net (code "283") (name "Net-(IC6A-X6)") (class "Default")
      (node (ref "IC6") (pin "2") (pinfunction "X6_2") (pintype "bidirectional"))
      (node (ref "JP12") (pin "2") (pinfunction "2_2") (pintype "passive"))
    )
    (net (code "284") (name "Net-(IC6A-X7)") (class "Default")
      (node (ref "IC6") (pin "4") (pinfunction "X7_4") (pintype "bidirectional"))
      (node (ref "JP12") (pin "1") (pinfunction "1_1") (pintype "passive"))
    )
    (net (code "285") (name "Net-(IC7A-X0)") (class "Default")
      (node (ref "IC7") (pin "13") (pinfunction "X0_13") (pintype "bidirectional"))
      (node (ref "JP13") (pin "8") (pinfunction "8_8") (pintype "passive"))
    )
    (net (code "286") (name "Net-(IC7A-X1)") (class "Default")
      (node (ref "IC7") (pin "14") (pinfunction "X1_14") (pintype "bidirectional"))
      (node (ref "JP13") (pin "7") (pinfunction "7_7") (pintype "passive"))
    )
    (net (code "287") (name "Net-(IC7A-X2)") (class "Default")
      (node (ref "IC7") (pin "15") (pinfunction "X2_15") (pintype "bidirectional"))
      (node (ref "JP13") (pin "6") (pinfunction "6_6") (pintype "passive"))
    )
    (net (code "288") (name "Net-(IC7A-X3)") (class "Default")
      (node (ref "IC7") (pin "12") (pinfunction "X3_12") (pintype "bidirectional"))
      (node (ref "JP13") (pin "5") (pinfunction "5_5") (pintype "passive"))
    )
    (net (code "289") (name "Net-(IC7A-X4)") (class "Default")
      (node (ref "IC7") (pin "1") (pinfunction "X4_1") (pintype "bidirectional"))
      (node (ref "JP13") (pin "4") (pinfunction "4_4") (pintype "passive"))
    )
    (net (code "290") (name "Net-(IC7A-X5)") (class "Default")
      (node (ref "IC7") (pin "5") (pinfunction "X5_5") (pintype "bidirectional"))
      (node (ref "JP13") (pin "3") (pinfunction "3_3") (pintype "passive"))
    )
    (net (code "291") (name "Net-(IC7A-X6)") (class "Default")
      (node (ref "IC7") (pin "2") (pinfunction "X6_2") (pintype "bidirectional"))
      (node (ref "JP13") (pin "2") (pinfunction "2_2") (pintype "passive"))
    )
    (net (code "292") (name "Net-(IC7A-X7)") (class "Default")
      (node (ref "IC7") (pin "4") (pinfunction "X7_4") (pintype "bidirectional"))
      (node (ref "JP13") (pin "1") (pinfunction "1_1") (pintype "passive"))
    )
    (net (code "293") (name "Net-(J6-Pad2)") (class "Default")
      (node (ref "J6") (pin "2") (pinfunction "2_2") (pintype "passive"))
      (node (ref "SJ1") (pin "2") (pinfunction "2_2") (pintype "passive"))
    )
    (net (code "294") (name "Net-(LED1-PadC)") (class "Default")
      (node (ref "LED1") (pin "C") (pinfunction "C_C") (pintype "passive"))
      (node (ref "R2") (pin "1") (pinfunction "1_1") (pintype "passive"))
    )
    (net (code "295") (name "Net-(LED2-PadC)") (class "Default")
      (node (ref "LED2") (pin "C") (pinfunction "C_C") (pintype "passive"))
      (node (ref "R5") (pin "1") (pinfunction "1_1") (pintype "passive"))
    )
    (net (code "296") (name "Net-(LED3-PadC)") (class "Default")
      (node (ref "LED3") (pin "C") (pinfunction "C_C") (pintype "passive"))
      (node (ref "R9") (pin "1") (pinfunction "1_1") (pintype "passive"))
    )
    (net (code "297") (name "Net-(LED4-PadC)") (class "Default")
      (node (ref "LED4") (pin "C") (pinfunction "C_C") (pintype "passive"))
      (node (ref "R38") (pin "1") (pinfunction "1_1") (pintype "passive"))
    )
    (net (code "298") (name "Net-(LED5-PadC)") (class "Default")
      (node (ref "LED5") (pin "C") (pinfunction "C_C") (pintype "passive"))
      (node (ref "R42") (pin "1") (pinfunction "1_1") (pintype "passive"))
    )
    (net (code "299") (name "Net-(LED6-PadC)") (class "Default")
      (node (ref "LED6") (pin "C") (pinfunction "C_C") (pintype "passive"))
      (node (ref "R45") (pin "1") (pinfunction "1_1") (pintype "passive"))
    )
    (net (code "300") (name "Net-(M1-SW)") (class "Default")
      (node (ref "L2") (pin "2") (pinfunction "2_2") (pintype "passive"))
      (node (ref "M1") (pin "2") (pinfunction "SW_2") (pintype "passive"))
    )
    (net (code "301") (name "Net-(M2-SW)") (class "Default")
      (node (ref "L3") (pin "2") (pinfunction "2_2") (pintype "passive"))
      (node (ref "M2") (pin "2") (pinfunction "SW_2") (pintype "passive"))
    )
    (net (code "302") (name "Net-(M3-SW)") (class "Default")
      (node (ref "L8") (pin "2") (pinfunction "2_2") (pintype "passive"))
      (node (ref "M3") (pin "2") (pinfunction "SW_2") (pintype "passive"))
    )
    (net (code "303") (name "Net-(Q1-D)") (class "Default")
      (node (ref "Q1") (pin "3") (pinfunction "D_3") (pintype "passive"))
      (node (ref "U$3") (pin "12") (pinfunction "CA0_12") (pintype "passive"))
    )
    (net (code "304") (name "Net-(Q2-D)") (class "Default")
      (node (ref "Q2") (pin "3") (pinfunction "D_3") (pintype "passive"))
      (node (ref "U$3") (pin "9") (pinfunction "CA1_9") (pintype "passive"))
    )
    (net (code "305") (name "Net-(Q3-D)") (class "Default")
      (node (ref "Q3") (pin "3") (pinfunction "D_3") (pintype "passive"))
      (node (ref "U$3") (pin "8") (pinfunction "CA2_8") (pintype "passive"))
    )
    (net (code "306") (name "Net-(Q5-D)") (class "Default")
      (node (ref "Q5") (pin "3") (pinfunction "D_3") (pintype "passive"))
      (node (ref "U$3") (pin "6") (pinfunction "CA3_6") (pintype "passive"))
    )
    (net (code "307") (name "Net-(Q7-D)") (class "Default")
      (node (ref "L6") (pin "1") (pinfunction "1_1") (pintype "passive"))
      (node (ref "Q7") (pin "3") (pinfunction "D_3") (pintype "passive"))
      (node (ref "Q8") (pin "3") (pinfunction "D_3") (pintype "passive"))
    )
    (net (code "308") (name "Net-(Q7-G)") (class "Default")
      (node (ref "Q7") (pin "1") (pinfunction "G_1") (pintype "passive"))
      (node (ref "R49") (pin "1") (pinfunction "1_1") (pintype "passive"))
      (node (ref "R50") (pin "1") (pinfunction "1_1") (pintype "passive"))
    )
    (net (code "309") (name "Net-(Q8-G)") (class "Default")
      (node (ref "Q8") (pin "1") (pinfunction "G_1") (pintype "passive"))
      (node (ref "R51") (pin "1") (pinfunction "1_1") (pintype "passive"))
    )
    (net (code "310") (name "Net-(T1C-A)") (class "Default")
      (node (ref "R55") (pin "1") (pinfunction "1_1") (pintype "passive"))
      (node (ref "T1") (pin "9") (pinfunction "A_9") (pintype "passive"))
    )
    (net (code "311") (name "Net-(T1D-A)") (class "Default")
      (node (ref "R54") (pin "1") (pinfunction "1_1") (pintype "passive"))
      (node (ref "T1") (pin "12") (pinfunction "A_12") (pintype "passive"))
    )
    (net (code "312") (name "Net-(U$4-PA1{slash}OSCIN)") (class "Default")
      (node (ref "TP17") (pin "TP") (pinfunction "TP_TP") (pintype "input"))
      (node (ref "U$4") (pin "5") (pinfunction "PA1/OSCIN_5") (pintype "bidirectional"))
    )
    (net (code "313") (name "Net-(U$4-PA2{slash}OSCOUT)") (class "Default")
      (node (ref "TP18") (pin "TP") (pinfunction "TP_TP") (pintype "input"))
      (node (ref "U$4") (pin "6") (pinfunction "PA2/OSCOUT_6") (pintype "bidirectional"))
    )
    (net (code "314") (name "Net-(U$4-VCAP)") (class "Default")
      (node (ref "C14") (pin "2") (pinfunction "2_2") (pintype "passive"))
      (node (ref "U$4") (pin "8") (pinfunction "VCAP_8") (pintype "passive"))
    )
    (net (code "315") (name "Net-(U$12-Pad1)") (class "Default")
      (node (ref "U$12") (pin "1") (pinfunction "1_1") (pintype "passive"))
      (node (ref "X2") (pin "1") (pinfunction "1_1") (pintype "passive"))
    )
    (net (code "316") (name "Net-(U$14-SW)") (class "Default")
      (node (ref "L9") (pin "2") (pinfunction "2_2") (pintype "passive"))
      (node (ref "U$14") (pin "1") (pinfunction "SW_1") (pintype "passive"))
    )
    (net (code "317") (name "Net-(U$15-FB)") (class "Default")
      (node (ref "R73") (pin "1") (pinfunction "1_1") (pintype "passive"))
      (node (ref "R74") (pin "2") (pinfunction "2_2") (pintype "passive"))
      (node (ref "U$15") (pin "3") (pinfunction "FB_3") (pintype "passive"))
    )
    (net (code "318") (name "Net-(U$19-BOOT0)") (class "Default")
      (node (ref "JP9") (pin "2") (pinfunction "2_2") (pintype "passive"))
      (node (ref "R76") (pin "2") (pinfunction "2_2") (pintype "passive"))
      (node (ref "U$19") (pin "1") (pinfunction "BOOT0_1") (pintype "input"))
    )
    (net (code "319") (name "Net-(U$19-VDDA)") (class "Default")
      (node (ref "C45") (pin "2") (pinfunction "2_2") (pintype "passive"))
      (node (ref "C46") (pin "2") (pinfunction "2_2") (pintype "passive"))
      (node (ref "L11") (pin "1") (pinfunction "1_1") (pintype "passive"))
      (node (ref "U$19") (pin "5") (pinfunction "VDDA_5") (pintype "power_in"))
    )
    (net (code "320") (name "Net-(U$28-EN)") (class "Default")
      (node (ref "C78") (pin "2") (pinfunction "2_2") (pintype "passive"))
      (node (ref "L14") (pin "2") (pinfunction "2_2") (pintype "passive"))
      (node (ref "U$28") (pin "1") (pinfunction "VIN_1") (pintype "power_in"))
      (node (ref "U$28") (pin "3") (pinfunction "EN_3") (pintype "input"))
    )
    (net (code "321") (name "Net-(U2-IO5)") (class "Default")
      (node (ref "R65") (pin "2") (pinfunction "2_2") (pintype "passive"))
      (node (ref "U2") (pin "29") (pinfunction "IO5_29") (pintype "bidirectional"))
    )
    (net (code "322") (name "Net-(USB1B-D+)") (class "Default")
      (node (ref "R14") (pin "1") (pinfunction "1_1") (pintype "passive"))
      (node (ref "USB1") (pin "P3") (pinfunction "D+_P3") (pintype "bidirectional"))
    )
    (net (code "323") (name "Net-(USB1B-D-)") (class "Default")
      (node (ref "R12") (pin "1") (pinfunction "1_1") (pintype "passive"))
      (node (ref "USB1") (pin "P2") (pinfunction "D-_P2") (pintype "bidirectional"))
    )
    (net (code "324") (name "Net-(USB1B-VUSB)") (class "Default")
      (node (ref "L4") (pin "1") (pinfunction "1_1") (pintype "passive"))
      (node (ref "USB1") (pin "P1") (pinfunction "VUSB_P1") (pintype "bidirectional"))
    )
    (net (code "325") (name "Net-(USB2B-D+)") (class "Default")
      (node (ref "R48") (pin "1") (pinfunction "1_1") (pintype "passive"))
      (node (ref "USB2") (pin "P3") (pinfunction "D+_P3") (pintype "bidirectional"))
    )
    (net (code "326") (name "Net-(USB2B-D-)") (class "Default")
      (node (ref "R47") (pin "1") (pinfunction "1_1") (pintype "passive"))
      (node (ref "USB2") (pin "P2") (pinfunction "D-_P2") (pintype "bidirectional"))
    )
    (net (code "327") (name "Net-(USB3B-D+)") (class "Default")
      (node (ref "R79") (pin "1") (pinfunction "1_1") (pintype "passive"))
      (node (ref "USB3") (pin "P3") (pinfunction "D+_P3") (pintype "bidirectional"))
    )
    (net (code "328") (name "Net-(USB3B-D-)") (class "Default")
      (node (ref "R78") (pin "1") (pinfunction "1_1") (pintype "passive"))
      (node (ref "USB3") (pin "P2") (pinfunction "D-_P2") (pintype "bidirectional"))
    )
    (net (code "329") (name "Net-(USB3B-VUSB)") (class "Default")
      (node (ref "L14") (pin "1") (pinfunction "1_1") (pintype "passive"))
      (node (ref "USB3") (pin "P1") (pinfunction "VUSB_P1") (pintype "bidirectional"))
    )
    (net (code "330") (name "Net-(X2L-1)") (class "Default")
      (node (ref "U$12") (pin "2") (pinfunction "2_2") (pintype "passive"))
      (node (ref "U$17") (pin "1") (pinfunction "1_1") (pintype "passive"))
      (node (ref "X2") (pin "2") (pinfunction "1_2") (pintype "passive"))
      (node (ref "X2") (pin "3") (pinfunction "1_3") (pintype "passive"))
    )
    (net (code "331") (name "VEE") (class "Default")
      (node (ref "C13") (pin "2") (pinfunction "2_2") (pintype "passive"))
      (node (ref "C66") (pin "1") (pinfunction "1_1") (pintype "passive"))
      (node (ref "C9") (pin "2") (pinfunction "2_2") (pintype "passive"))
      (node (ref "D3") (pin "A") (pinfunction "A_A") (pintype "passive"))
      (node (ref "IC2") (pin "4") (pinfunction "V-_4") (pintype "power_in"))
    )
    (net (code "332") (name "V_BATT") (class "Default")
      (node (ref "C70") (pin "1") (pinfunction "1_1") (pintype "passive"))
      (node (ref "C72") (pin "2") (pinfunction "2_2") (pintype "passive"))
      (node (ref "C73") (pin "1") (pinfunction "1_1") (pintype "passive"))
      (node (ref "C75") (pin "1") (pinfunction "1_1") (pintype "passive"))
      (node (ref "IC6") (pin "16") (pinfunction "VCC_16") (pintype "power_in"))
      (node (ref "IC7") (pin "16") (pinfunction "VCC_16") (pintype "power_in"))
      (node (ref "JP10") (pin "2") (pinfunction "2_2") (pintype "passive"))
      (node (ref "R81") (pin "2") (pinfunction "2_2") (pintype "passive"))
      (node (ref "SJ1") (pin "1") (pinfunction "1_1") (pintype "passive"))
      (node (ref "U4") (pin "1") (pinfunction "VCC_1") (pintype "power_in"))
    )
    (net (code "333") (name "unconnected-(H1-MOUNT-PadB3,2)") (class "Default")
      (node (ref "H1") (pin "B3,2") (pinfunction "MOUNT_B3,2") (pintype "passive"))
    )
    (net (code "334") (name "unconnected-(H2-MOUNT-PadB3,2)") (class "Default")
      (node (ref "H2") (pin "B3,2") (pinfunction "MOUNT_B3,2") (pintype "passive"))
    )
    (net (code "335") (name "unconnected-(H3-MOUNT-PadB3,2)") (class "Default")
      (node (ref "H3") (pin "B3,2") (pinfunction "MOUNT_B3,2") (pintype "passive"))
    )
    (net (code "336") (name "unconnected-(H4-MOUNT-PadB3,2)") (class "Default")
      (node (ref "H4") (pin "B3,2") (pinfunction "MOUNT_B3,2") (pintype "passive"))
    )
    (net (code "337") (name "unconnected-(H5-MOUNT-PadB3,2)") (class "Default")
      (node (ref "H5") (pin "B3,2") (pinfunction "MOUNT_B3,2") (pintype "passive"))
    )
    (net (code "338") (name "unconnected-(H6-MOUNT-PadB3,2)") (class "Default")
      (node (ref "H6") (pin "B3,2") (pinfunction "MOUNT_B3,2") (pintype "passive"))
    )
    (net (code "339") (name "unconnected-(H7-MOUNT-PadB3,2)") (class "Default")
      (node (ref "H7") (pin "B3,2") (pinfunction "MOUNT_B3,2") (pintype "passive"))
    )
    (net (code "340") (name "unconnected-(IC1-RXERR{slash}PHYAD0-Pad10)") (class "Default")
      (node (ref "IC1") (pin "10") (pinfunction "RXERR/PHYAD0_10") (pintype "bidirectional"))
    )
    (net (code "341") (name "unconnected-(IC1-XTAL2-Pad4)") (class "Default")
      (node (ref "IC1") (pin "4") (pinfunction "XTAL2_4") (pintype "bidirectional"))
    )
    (net (code "342") (name "unconnected-(J3-Pad2)") (class "Default")
      (node (ref "J3") (pin "2") (pinfunction "2_2") (pintype "passive"))
    )
    (net (code "343") (name "unconnected-(U$2-PA0-Pad10)") (class "Default")
      (node (ref "U$2") (pin "10") (pinfunction "PA0_10") (pintype "bidirectional"))
    )
    (net (code "344") (name "unconnected-(U$2-PA1-Pad11)") (class "Default")
      (node (ref "U$2") (pin "11") (pinfunction "PA1_11") (pintype "bidirectional"))
    )
    (net (code "345") (name "unconnected-(U$2-PA2-Pad12)") (class "Default")
      (node (ref "U$2") (pin "12") (pinfunction "PA2_12") (pintype "bidirectional"))
    )
    (net (code "346") (name "unconnected-(U$2-PA6-Pad16)") (class "Default")
      (node (ref "U$2") (pin "16") (pinfunction "PA6_16") (pintype "bidirectional"))
    )
    (net (code "347") (name "unconnected-(U$2-PA7-Pad17)") (class "Default")
      (node (ref "U$2") (pin "17") (pinfunction "PA7_17") (pintype "bidirectional"))
    )
    (net (code "348") (name "unconnected-(U$2-PA8-Pad29)") (class "Default")
      (node (ref "U$2") (pin "29") (pinfunction "PA8_29") (pintype "bidirectional"))
    )
    (net (code "349") (name "unconnected-(U$2-PB2-Pad20)") (class "Default")
      (node (ref "U$2") (pin "20") (pinfunction "PB2_20") (pintype "bidirectional"))
    )
    (net (code "350") (name "unconnected-(U$2-PB8-Pad45)") (class "Default")
      (node (ref "U$2") (pin "45") (pinfunction "PB8_45") (pintype "bidirectional"))
    )
    (net (code "351") (name "unconnected-(U$2-PB9-Pad46)") (class "Default")
      (node (ref "U$2") (pin "46") (pinfunction "PB9_46") (pintype "bidirectional"))
    )
    (net (code "352") (name "unconnected-(U$2-PB10-Pad21)") (class "Default")
      (node (ref "U$2") (pin "21") (pinfunction "PB10_21") (pintype "bidirectional"))
    )
    (net (code "353") (name "unconnected-(U$2-PB11-Pad22)") (class "Default")
      (node (ref "U$2") (pin "22") (pinfunction "PB11_22") (pintype "bidirectional"))
    )
    (net (code "354") (name "unconnected-(U$2-PB12-Pad25)") (class "Default")
      (node (ref "U$2") (pin "25") (pinfunction "PB12_25") (pintype "bidirectional"))
    )
    (net (code "355") (name "unconnected-(U$2-PB13-Pad26)") (class "Default")
      (node (ref "U$2") (pin "26") (pinfunction "PB13_26") (pintype "bidirectional"))
    )
    (net (code "356") (name "unconnected-(U$2-PB15-Pad28)") (class "Default")
      (node (ref "U$2") (pin "28") (pinfunction "PB15_28") (pintype "bidirectional"))
    )
    (net (code "357") (name "unconnected-(U$20-PB0-Pad13)") (class "Default")
      (node (ref "U$20") (pin "13") (pinfunction "PB0_13") (pintype "passive"))
    )
    (net (code "358") (name "unconnected-(U$20-PB1-Pad14)") (class "Default")
      (node (ref "U$20") (pin "14") (pinfunction "PB1_14") (pintype "passive"))
    )
    (net (code "359") (name "unconnected-(U$20-PB2-Pad15)") (class "Default")
      (node (ref "U$20") (pin "15") (pinfunction "PB2_15") (pintype "passive"))
    )
    (net (code "360") (name "unconnected-(U$20-PB3-Pad16)") (class "Default")
      (node (ref "U$20") (pin "16") (pinfunction "PB3_16") (pintype "passive"))
    )
    (net (code "361") (name "unconnected-(U$20-PB4-Pad1)") (class "Default")
      (node (ref "U$20") (pin "1") (pinfunction "PB4_1") (pintype "passive"))
    )
    (net (code "362") (name "unconnected-(U$20-PB5-Pad2)") (class "Default")
      (node (ref "U$20") (pin "2") (pinfunction "PB5_2") (pintype "passive"))
    )
    (net (code "363") (name "unconnected-(U$20-PB6-Pad3)") (class "Default")
      (node (ref "U$20") (pin "3") (pinfunction "PB6_3") (pintype "passive"))
    )
    (net (code "364") (name "unconnected-(U$20-PB7-Pad4)") (class "Default")
      (node (ref "U$20") (pin "4") (pinfunction "PB7_4") (pintype "passive"))
    )
    (net (code "365") (name "unconnected-(U$29-PB1-Pad14)") (class "Default")
      (node (ref "U$29") (pin "14") (pinfunction "PB1_14") (pintype "bidirectional"))
    )
    (net (code "366") (name "unconnected-(U2-CLK-Pad20)") (class "Default")
      (node (ref "U2") (pin "20") (pinfunction "CLK_20") (pintype "bidirectional"))
    )
    (net (code "367") (name "unconnected-(U2-CMD-Pad19)") (class "Default")
      (node (ref "U2") (pin "19") (pinfunction "CMD_19") (pintype "bidirectional"))
    )
    (net (code "368") (name "unconnected-(U2-IO2-Pad24)") (class "Default")
      (node (ref "U2") (pin "24") (pinfunction "IO2_24") (pintype "bidirectional"))
    )
    (net (code "369") (name "unconnected-(U2-IO4-Pad26)") (class "Default")
      (node (ref "U2") (pin "26") (pinfunction "IO4_26") (pintype "bidirectional"))
    )
    (net (code "370") (name "unconnected-(U2-IO12-Pad14)") (class "Default")
      (node (ref "U2") (pin "14") (pinfunction "IO12_14") (pintype "bidirectional"))
    )
    (net (code "371") (name "unconnected-(U2-IO13-Pad16)") (class "Default")
      (node (ref "U2") (pin "16") (pinfunction "IO13_16") (pintype "bidirectional"))
    )
    (net (code "372") (name "unconnected-(U2-IO14-Pad13)") (class "Default")
      (node (ref "U2") (pin "13") (pinfunction "IO14_13") (pintype "bidirectional"))
    )
    (net (code "373") (name "unconnected-(U2-IO15-Pad23)") (class "Default")
      (node (ref "U2") (pin "23") (pinfunction "IO15_23") (pintype "bidirectional"))
    )
    (net (code "374") (name "unconnected-(U2-IO16-Pad27)") (class "Default")
      (node (ref "U2") (pin "27") (pinfunction "IO16_27") (pintype "bidirectional"))
    )
    (net (code "375") (name "unconnected-(U2-IO17-Pad28)") (class "Default")
      (node (ref "U2") (pin "28") (pinfunction "IO17_28") (pintype "bidirectional"))
    )
    (net (code "376") (name "unconnected-(U2-IO21-Pad33)") (class "Default")
      (node (ref "U2") (pin "33") (pinfunction "IO21_33") (pintype "bidirectional"))
    )
    (net (code "377") (name "unconnected-(U2-IO22-Pad36)") (class "Default")
      (node (ref "U2") (pin "36") (pinfunction "IO22_36") (pintype "bidirectional"))
    )
    (net (code "378") (name "unconnected-(U2-IO25-Pad10)") (class "Default")
      (node (ref "U2") (pin "10") (pinfunction "IO25_10") (pintype "bidirectional"))
    )
    (net (code "379") (name "unconnected-(U2-IO26-Pad11)") (class "Default")
      (node (ref "U2") (pin "11") (pinfunction "IO26_11") (pintype "bidirectional"))
    )
    (net (code "380") (name "unconnected-(U2-IO27-Pad12)") (class "Default")
      (node (ref "U2") (pin "12") (pinfunction "IO27_12") (pintype "bidirectional"))
    )
    (net (code "381") (name "unconnected-(U2-IO32-Pad8)") (class "Default")
      (node (ref "U2") (pin "8") (pinfunction "IO32_8") (pintype "bidirectional"))
    )
    (net (code "382") (name "unconnected-(U2-IO33-Pad9)") (class "Default")
      (node (ref "U2") (pin "9") (pinfunction "IO33_9") (pintype "bidirectional"))
    )
    (net (code "383") (name "unconnected-(U2-IO34-Pad6)") (class "Default")
      (node (ref "U2") (pin "6") (pinfunction "IO34_6") (pintype "input"))
    )
    (net (code "384") (name "unconnected-(U2-IO35-Pad7)") (class "Default")
      (node (ref "U2") (pin "7") (pinfunction "IO35_7") (pintype "input"))
    )
    (net (code "385") (name "unconnected-(U2-NC-Pad32)") (class "Default")
      (node (ref "U2") (pin "32") (pinfunction "NC_32") (pintype "bidirectional"))
    )
    (net (code "386") (name "unconnected-(U2-SD1-Pad22)") (class "Default")
      (node (ref "U2") (pin "22") (pinfunction "SD1_22") (pintype "bidirectional"))
    )
    (net (code "387") (name "unconnected-(U2-SD2-Pad17)") (class "Default")
      (node (ref "U2") (pin "17") (pinfunction "SD2_17") (pintype "bidirectional"))
    )
    (net (code "388") (name "unconnected-(U2-SD3-Pad18)") (class "Default")
      (node (ref "U2") (pin "18") (pinfunction "SD3_18") (pintype "bidirectional"))
    )
    (net (code "389") (name "unconnected-(U2-SDO-Pad21)") (class "Default")
      (node (ref "U2") (pin "21") (pinfunction "SDO_21") (pintype "bidirectional"))
    )
    (net (code "390") (name "unconnected-(U2-SENSOR_VN-Pad5)") (class "Default")
      (node (ref "U2") (pin "5") (pinfunction "SENSOR_VN_5") (pintype "input"))
    )
    (net (code "391") (name "unconnected-(U2-SENSOR_VP-Pad4)") (class "Default")
      (node (ref "U2") (pin "4") (pinfunction "SENSOR_VP_4") (pintype "input"))
    )
    (net (code "392") (name "unconnected-(USB1A-BODY-PadBODY@1)") (class "Default")
      (node (ref "USB1") (pin "BODY@1") (pinfunction "BODY_BODY@1") (pintype "tri_state"))
    )
    (net (code "393") (name "unconnected-(USB1A-BODY-PadBODY@2)") (class "Default")
      (node (ref "USB1") (pin "BODY@2") (pinfunction "BODY_BODY@2") (pintype "tri_state"))
    )
    (net (code "394") (name "unconnected-(USB1A-BODY-PadBODY@3)") (class "Default")
      (node (ref "USB1") (pin "BODY@3") (pinfunction "BODY_BODY@3") (pintype "tri_state"))
    )
    (net (code "395") (name "unconnected-(USB1A-BODY-PadBODY@4)") (class "Default")
      (node (ref "USB1") (pin "BODY@4") (pinfunction "BODY_BODY@4") (pintype "tri_state"))
    )
    (net (code "396") (name "unconnected-(USB1B-USBID-PadP4)") (class "Default")
      (node (ref "USB1") (pin "P4") (pinfunction "USBID_P4") (pintype "bidirectional"))
    )
    (net (code "397") (name "unconnected-(USB2B-USBID-PadP4)") (class "Default")
      (node (ref "USB2") (pin "P4") (pinfunction "USBID_P4") (pintype "bidirectional"))
    )
    (net (code "398") (name "unconnected-(USB3B-USBID-PadP4)") (class "Default")
      (node (ref "USB3") (pin "P4") (pinfunction "USBID_P4") (pintype "bidirectional"))
    )
  )
)
